# Full.net
KiCad netlist of a schematic drawn in EAGLE
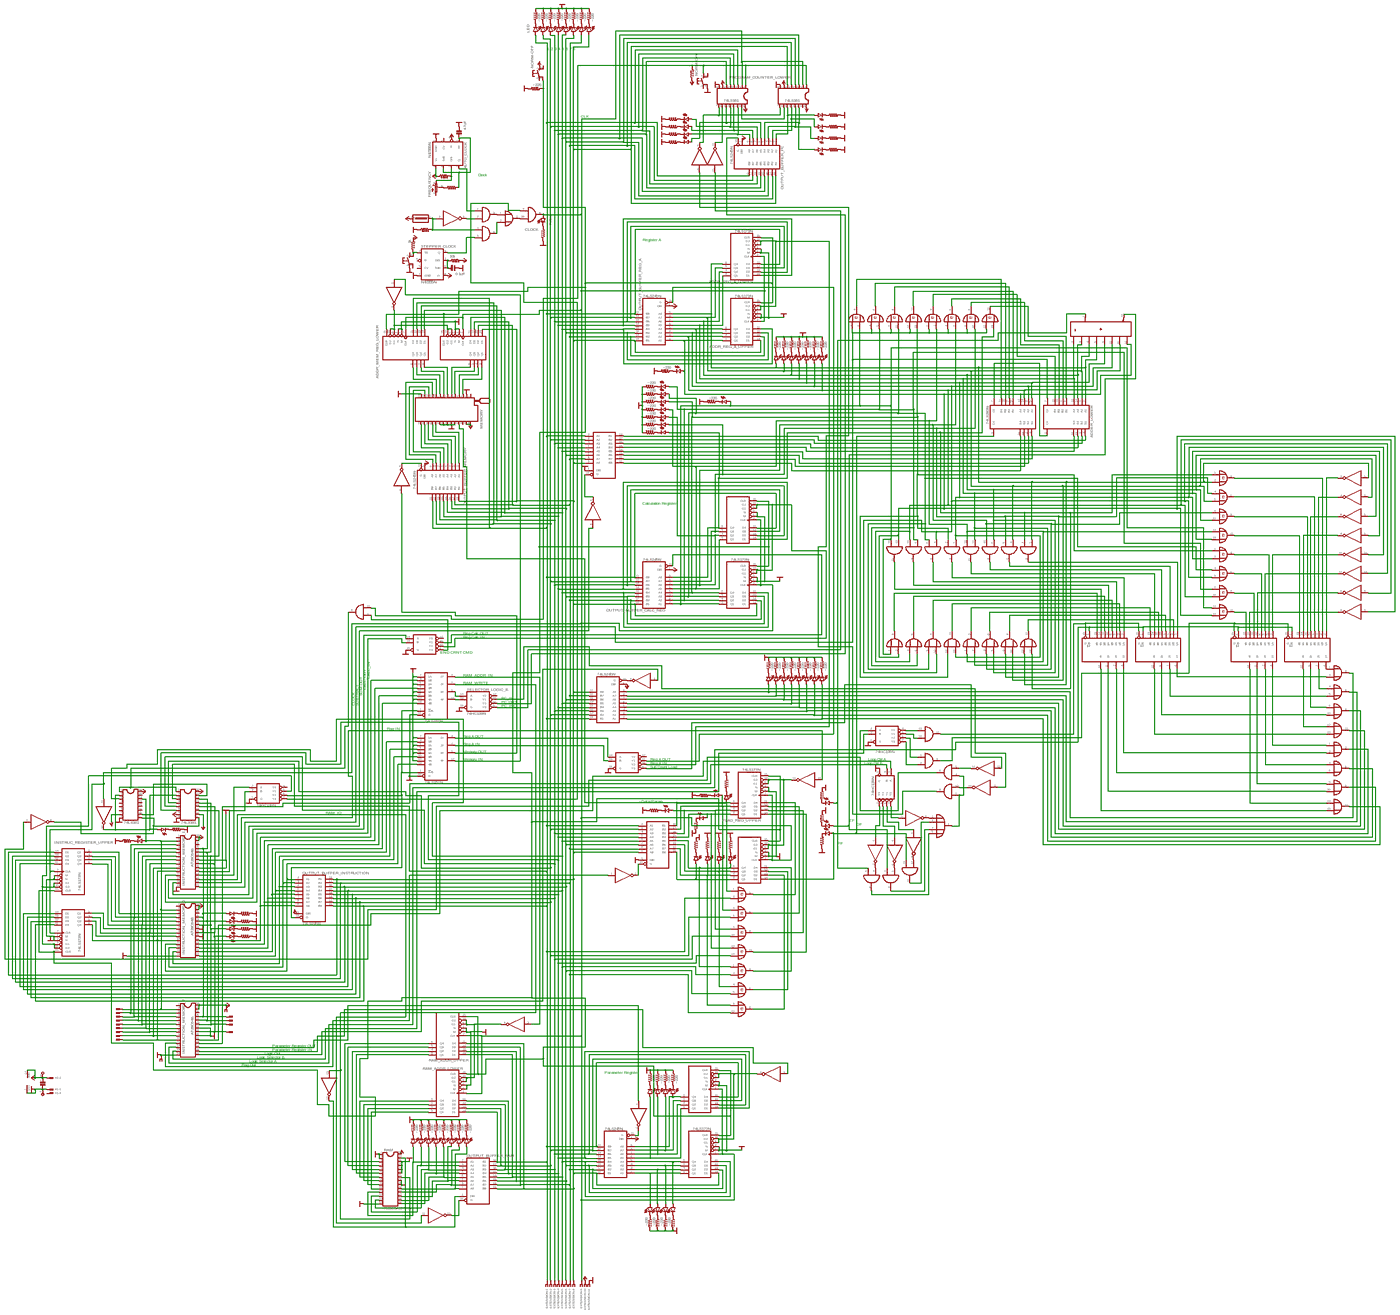
[diagram p0: schematic, sheet 1, overview]
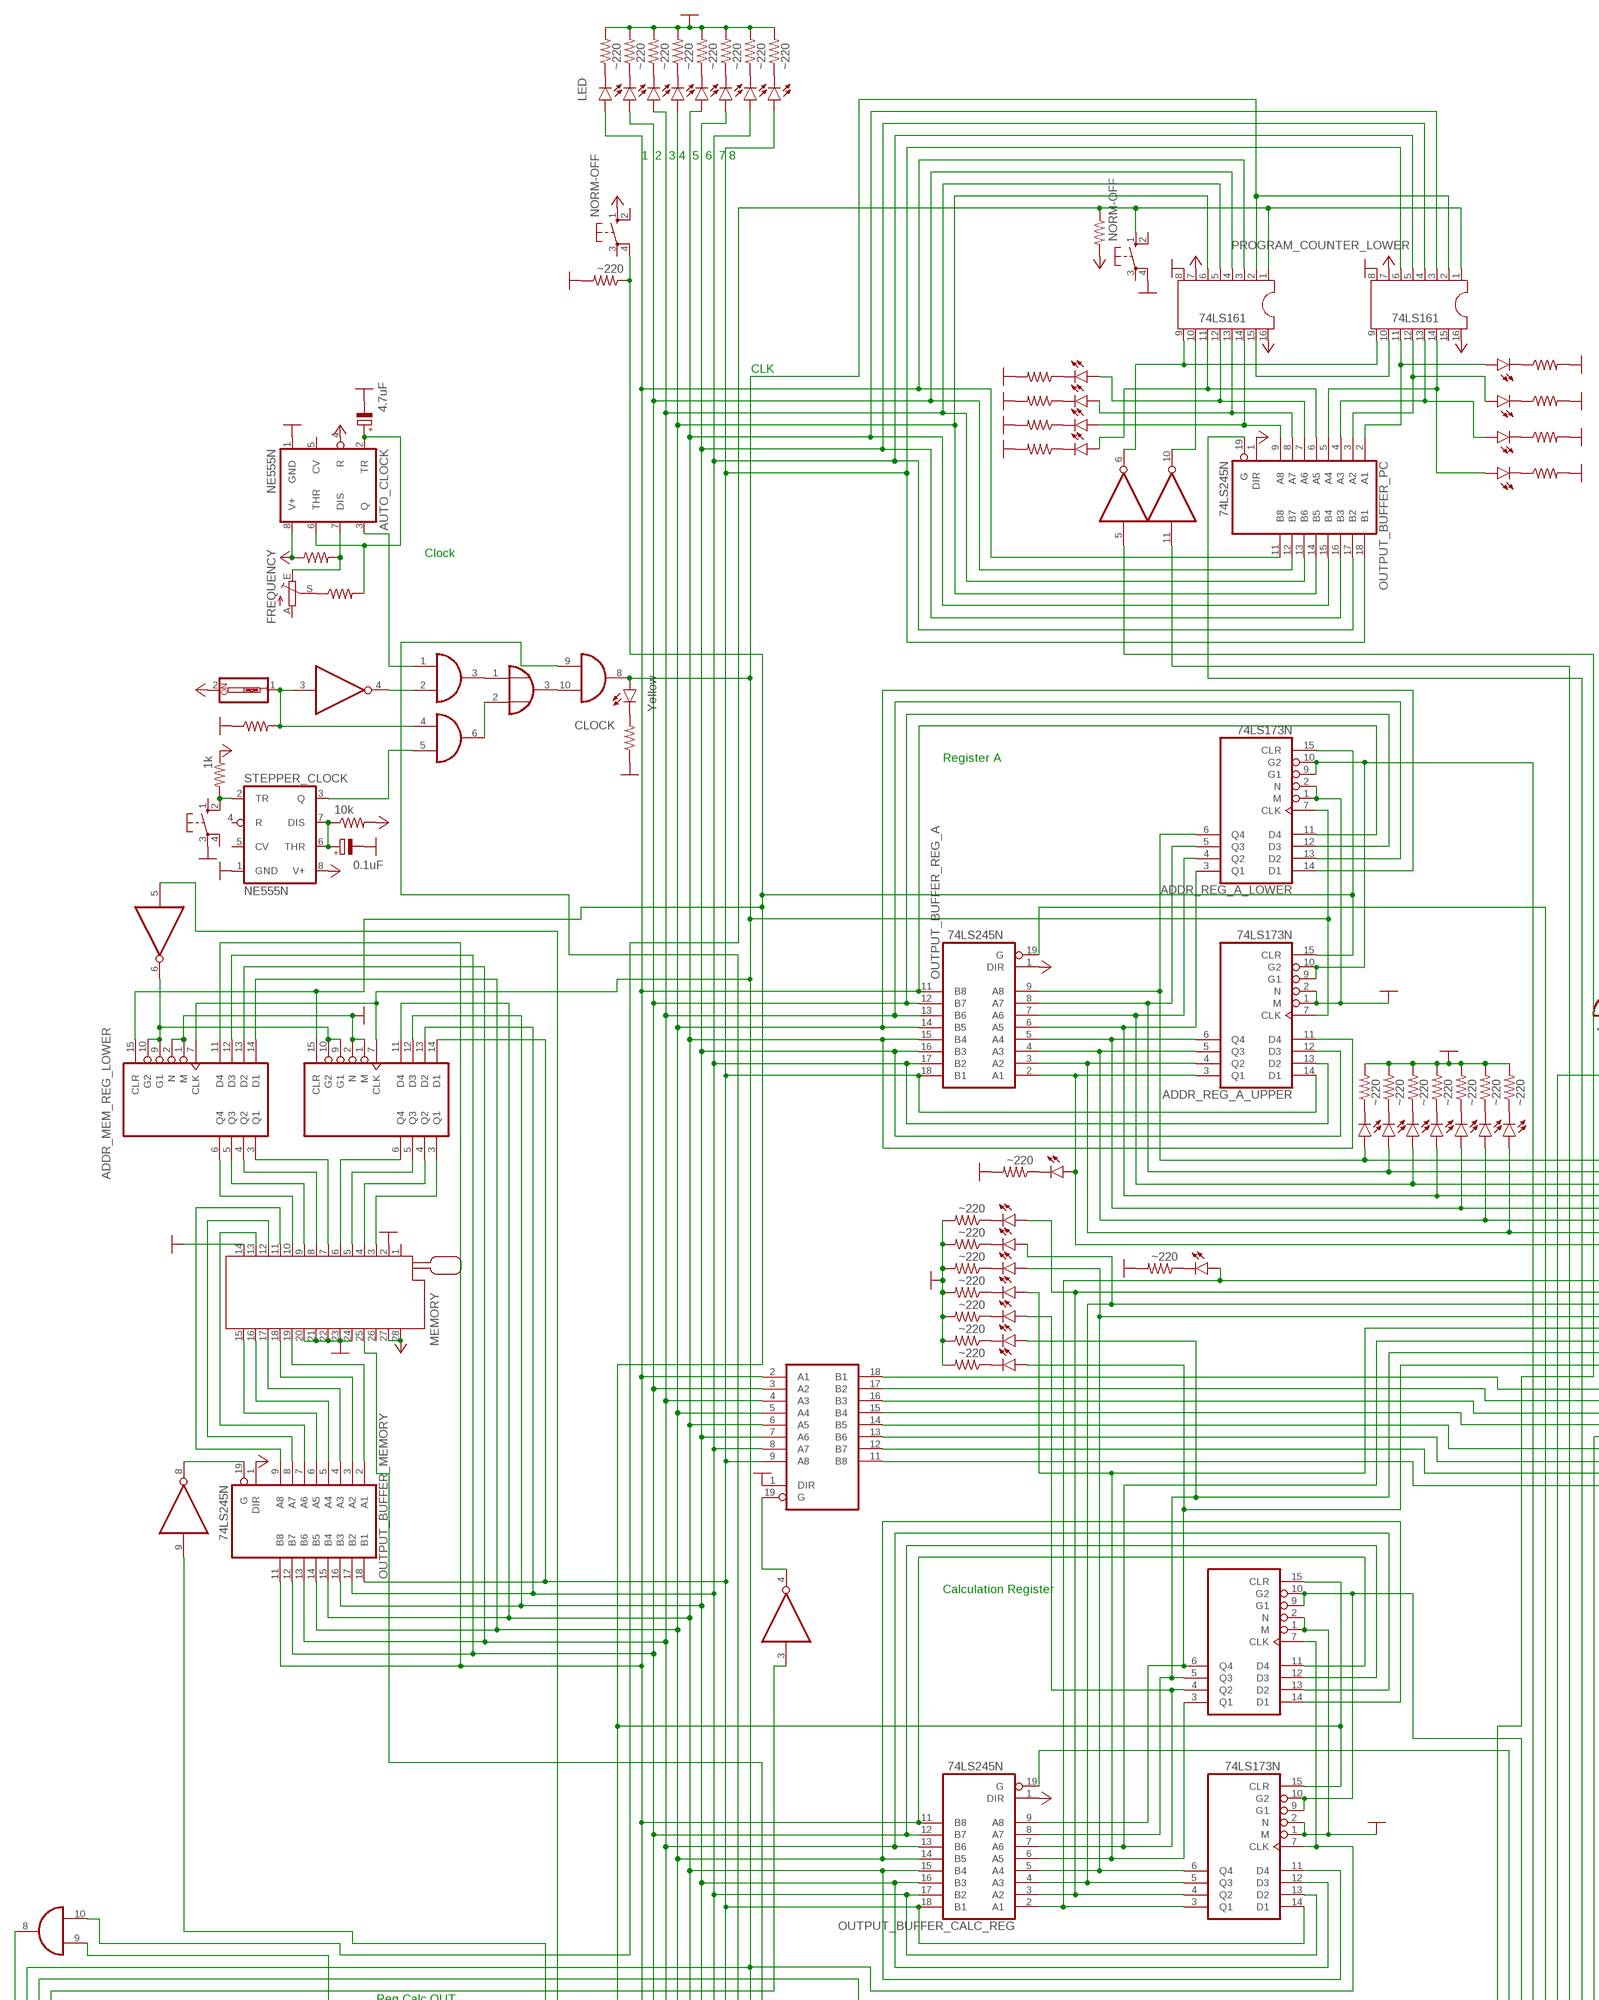
[diagram p1: schematic, sheet 1, part 1 of 4]
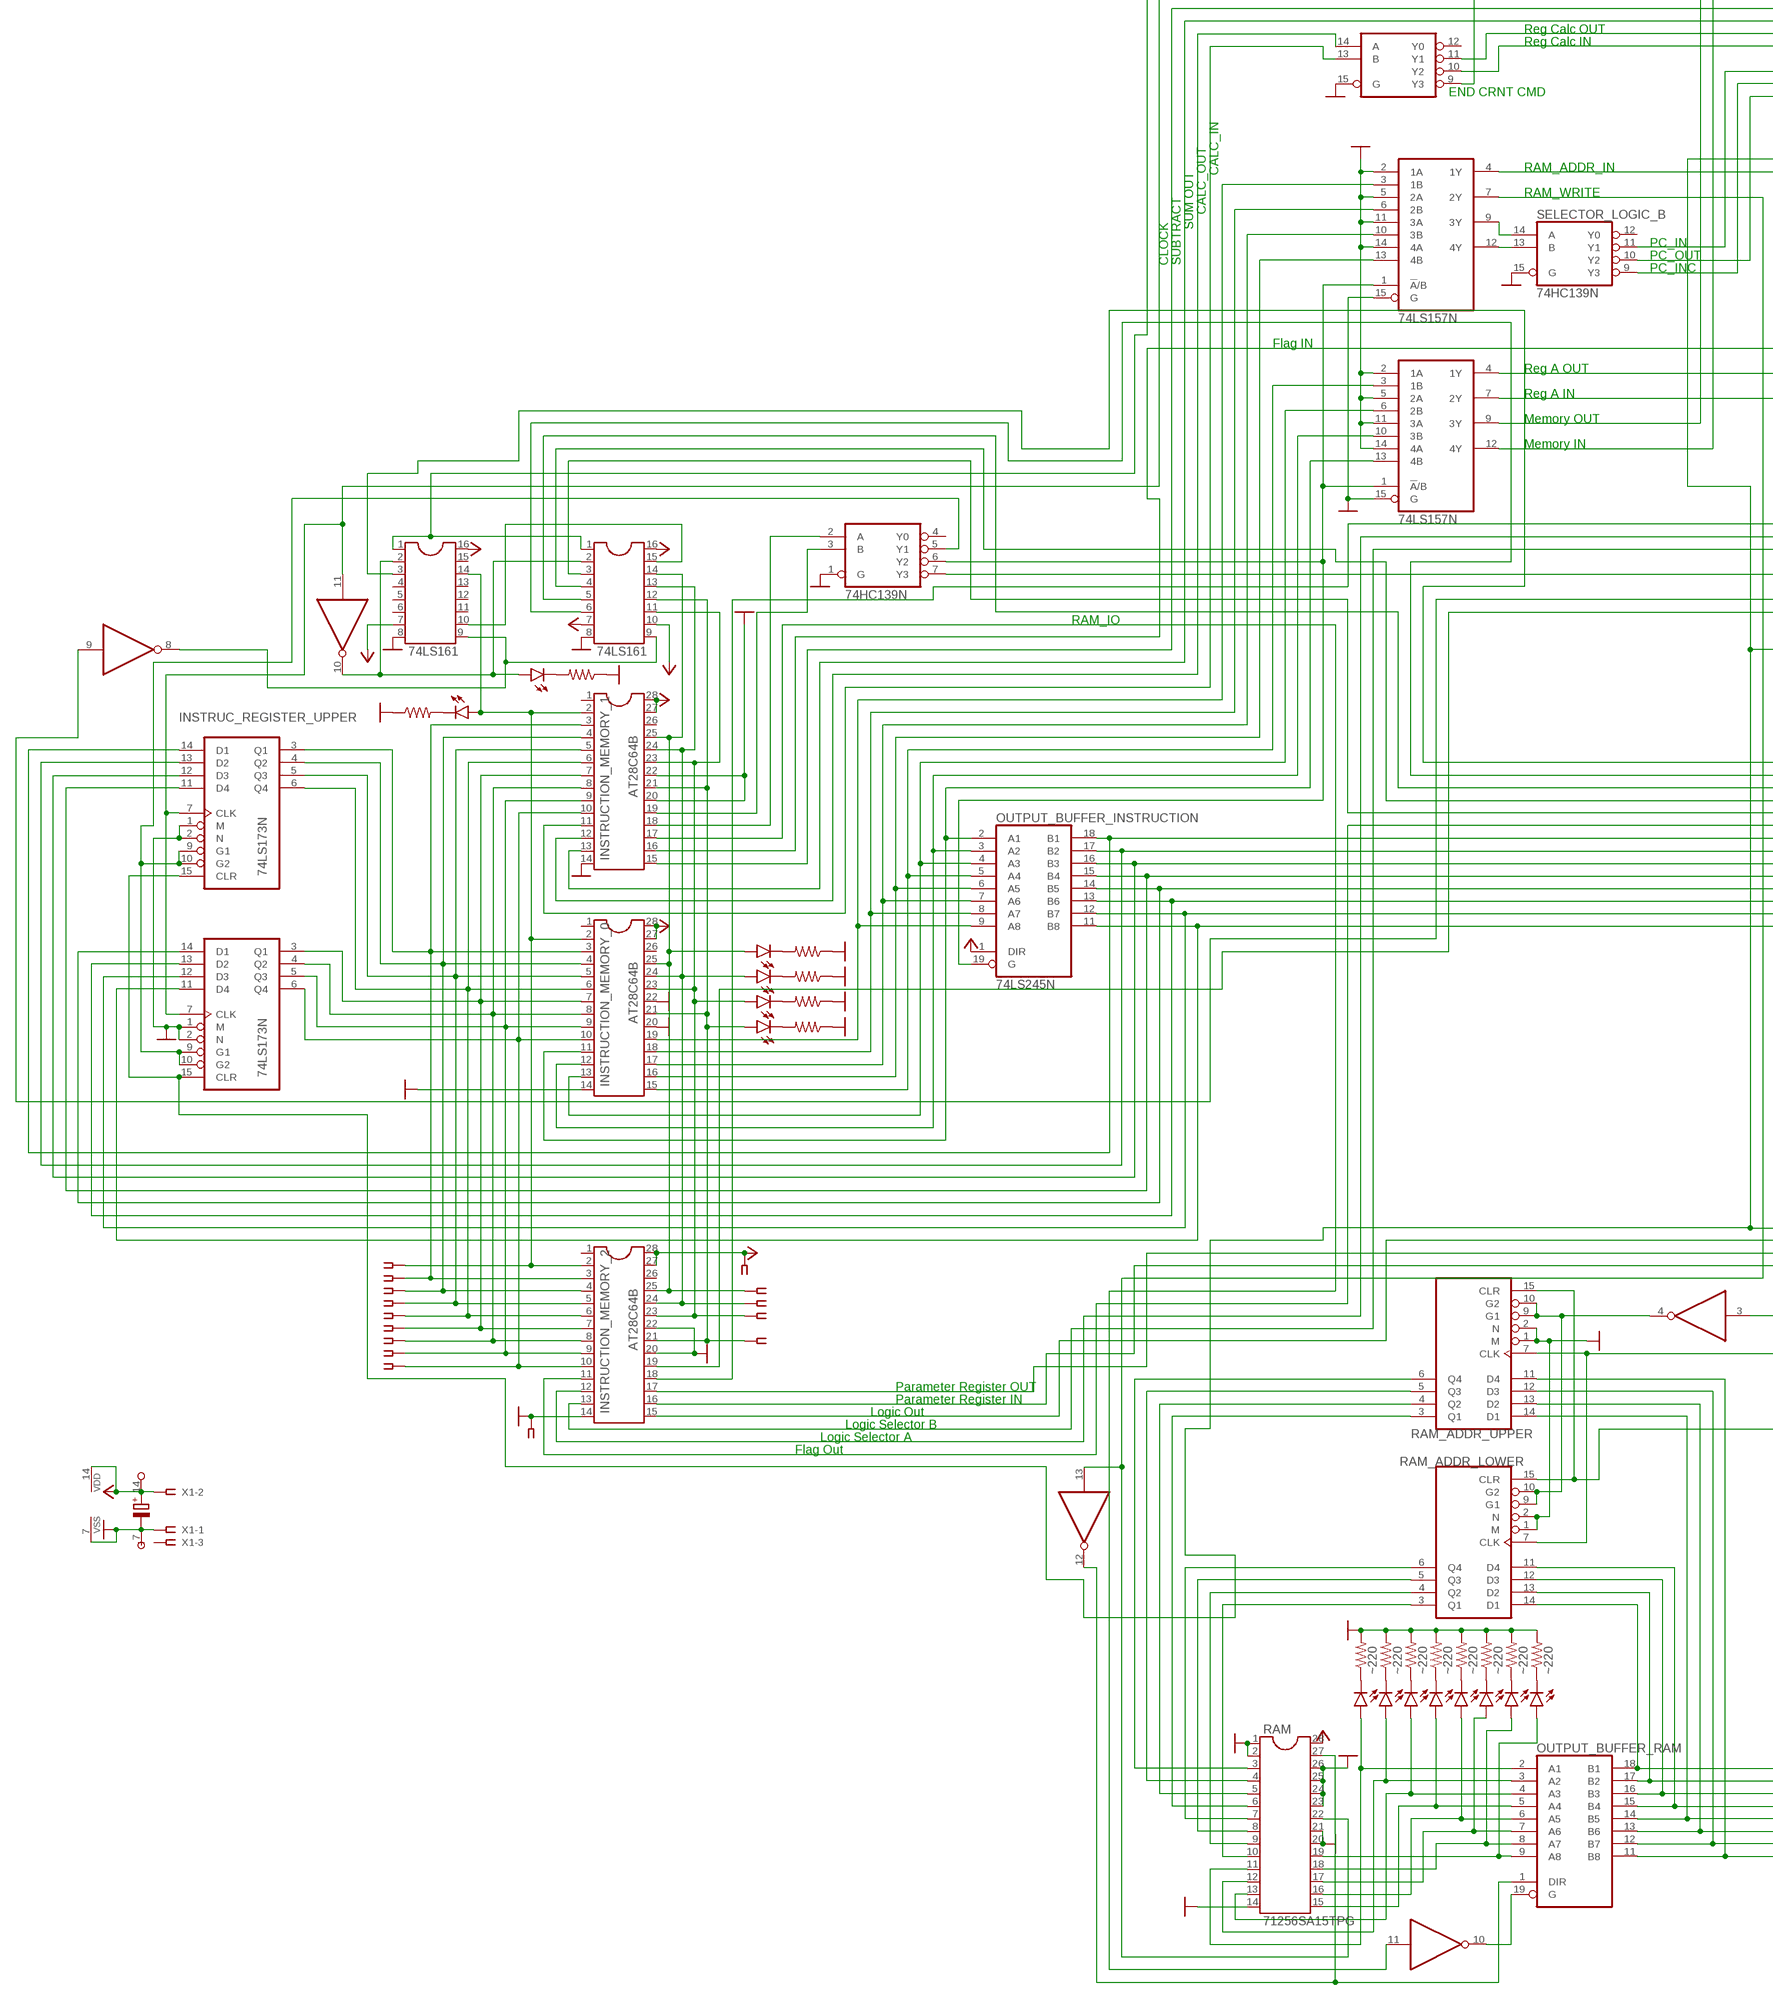
[diagram p2: schematic, sheet 1, part 2 of 4]
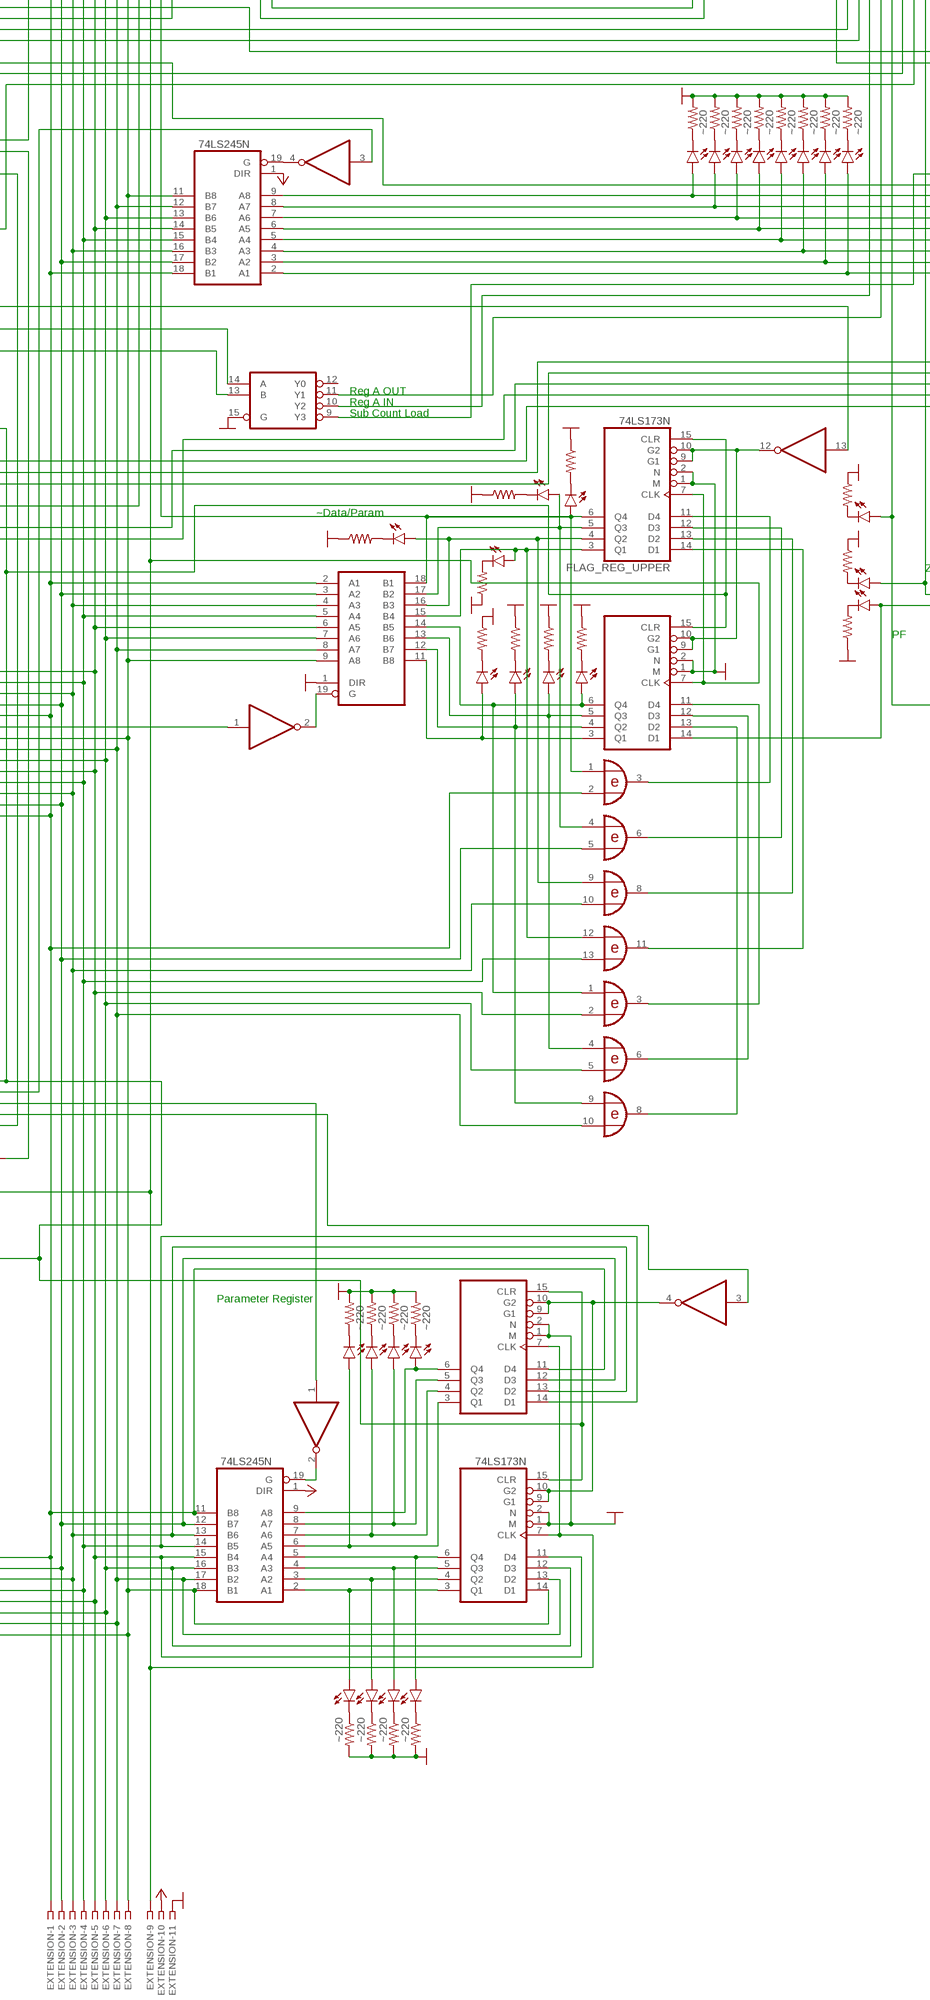
[diagram p3: schematic, sheet 1, part 3 of 4]
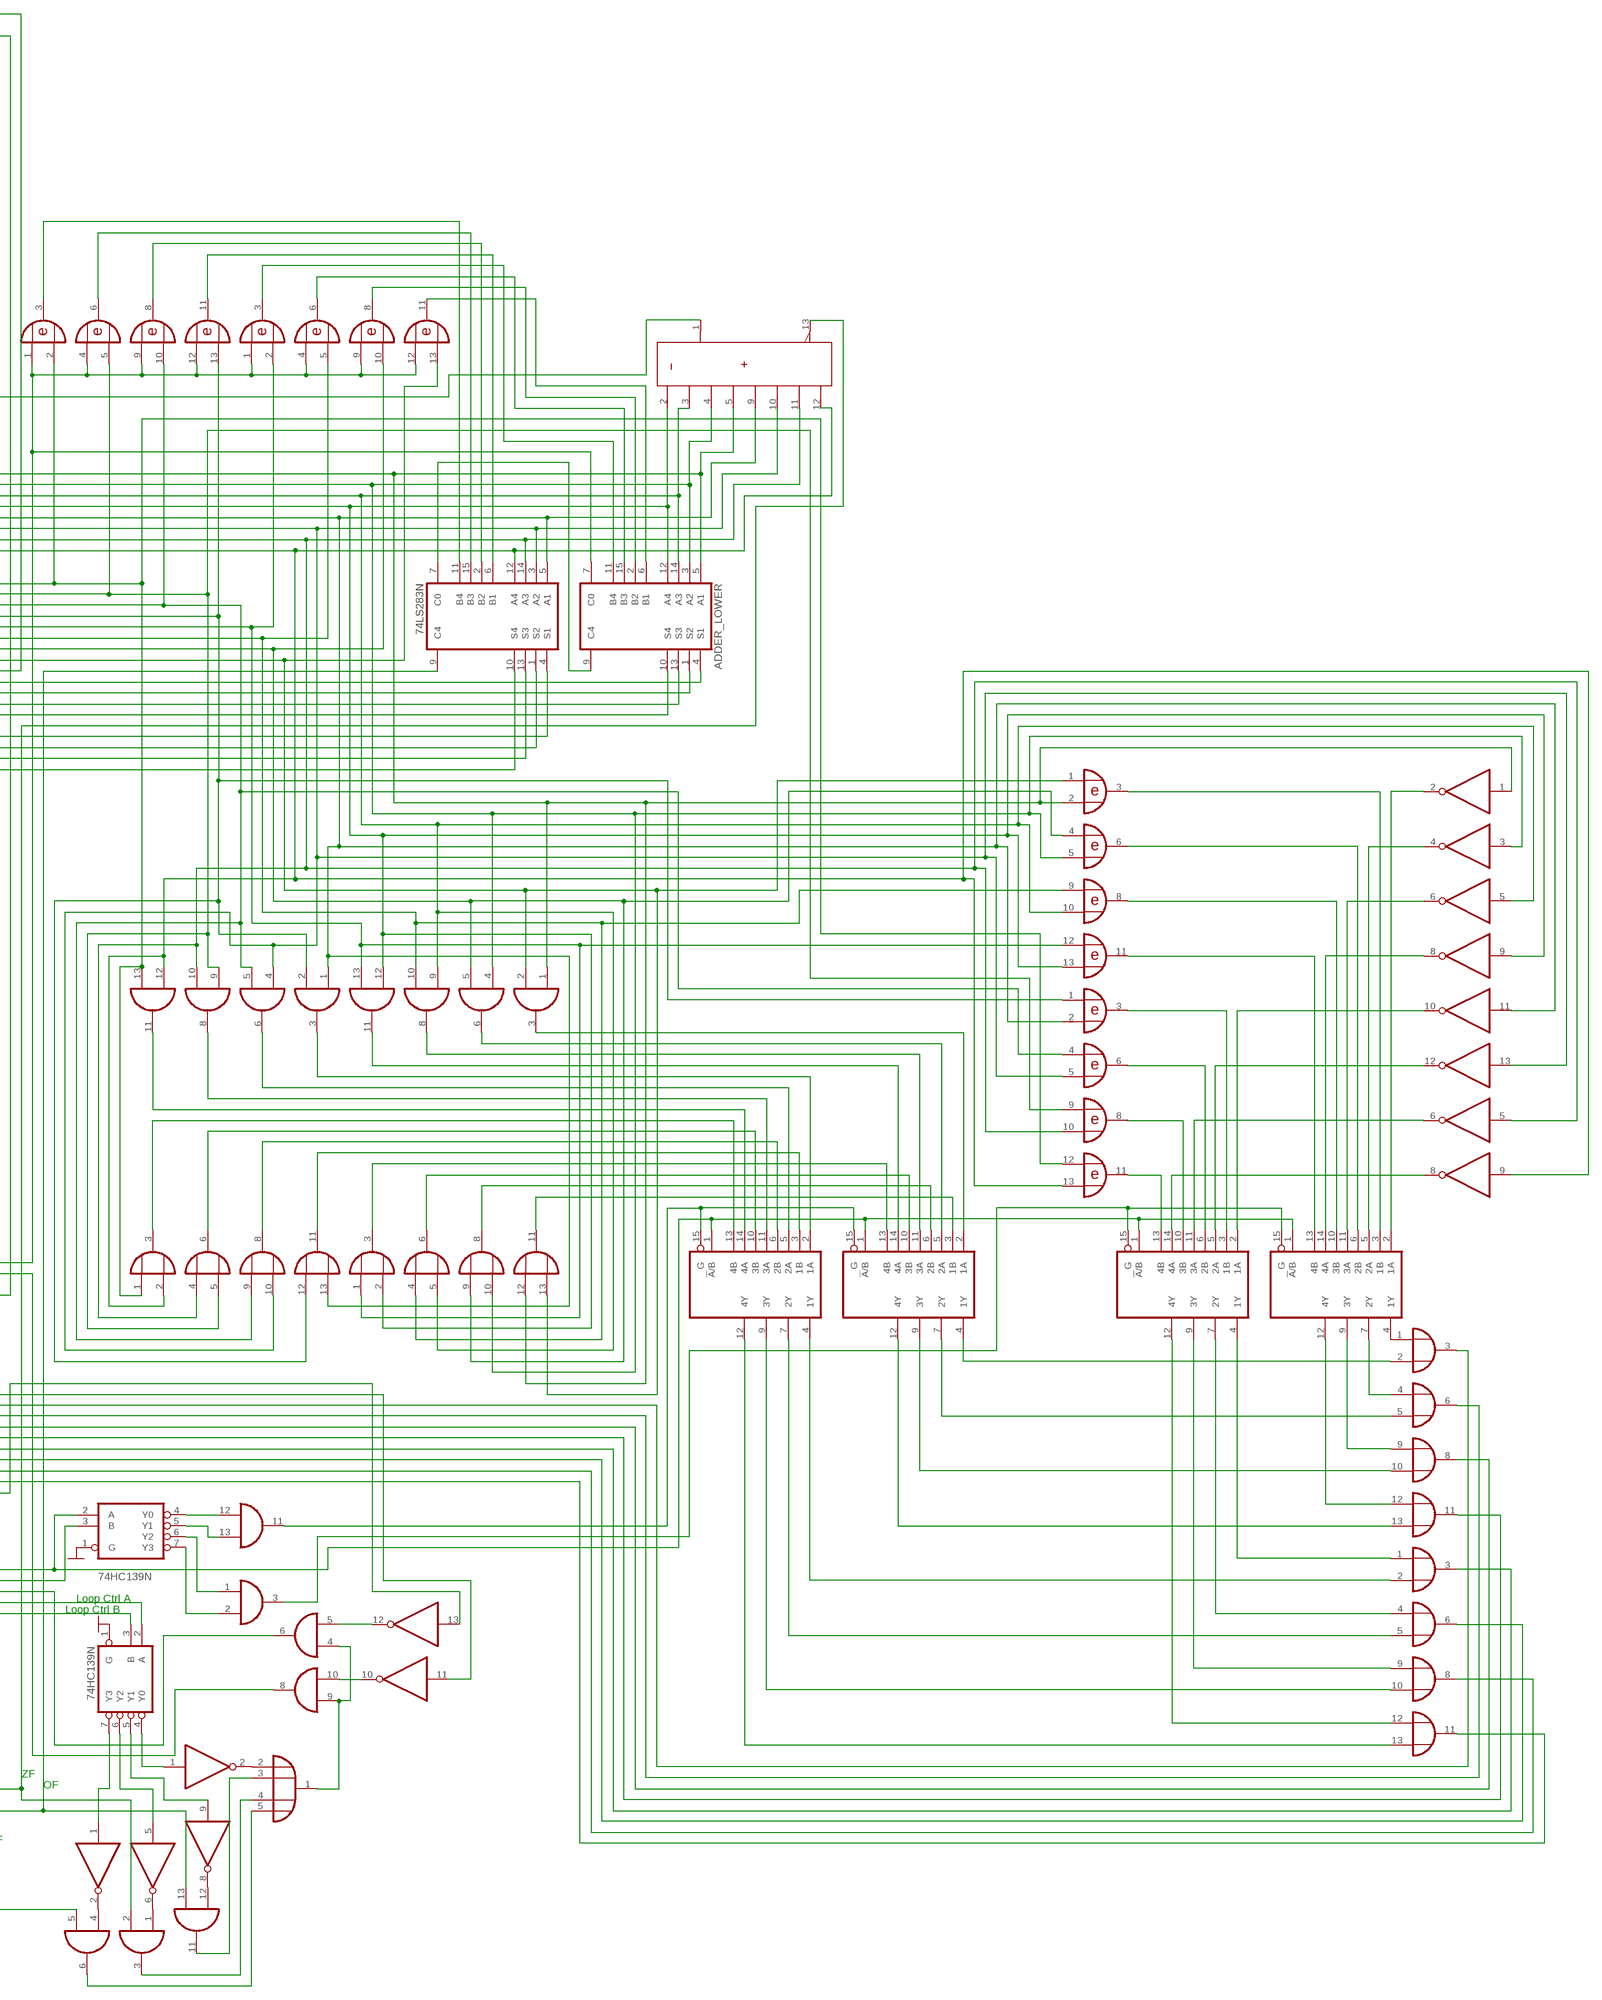
[diagram p4: schematic, sheet 1, part 4 of 4]

(export (version "E")
  (design (tool "Eeschema 10.0.6"))
  (components
    (comp (ref "4_INP_OR_GATE")
      (value "4072N")
      (footprint "eagle-import:DIL14")
      (libsource (lib "eagle-import") (part "4072N"))
    )
    (comp (ref "ADDER_LOWER")
      (value "74LS283N")
      (footprint "eagle-import:DIL16")
      (libsource (lib "eagle-import") (part "74283NLS"))
    )
    (comp (ref "ADDER_UPPER")
      (value "74LS283N")
      (footprint "eagle-import:DIL16")
      (libsource (lib "eagle-import") (part "74283NLS"))
    )
    (comp (ref "ADDR_MEM_REG_LOWER")
      (value "74LS173N")
      (footprint "eagle-import:DIL16")
      (libsource (lib "eagle-import") (part "74173NLS"))
    )
    (comp (ref "ADDR_MEM_REG_UPPER")
      (value "74LS173N")
      (footprint "eagle-import:DIL16")
      (libsource (lib "eagle-import") (part "74173NLS"))
    )
    (comp (ref "ADDR_REG_A_LOWER")
      (value "74LS173N")
      (footprint "eagle-import:DIL16")
      (libsource (lib "eagle-import") (part "74173NLS"))
    )
    (comp (ref "ADDR_REG_A_UPPER")
      (value "74LS173N")
      (footprint "eagle-import:DIL16")
      (libsource (lib "eagle-import") (part "74173NLS"))
    )
    (comp (ref "ADDR_REG_CALC_LOWER")
      (value "74LS173N")
      (footprint "eagle-import:DIL16")
      (libsource (lib "eagle-import") (part "74173NLS"))
    )
    (comp (ref "ADDR_REG_CALC_UPPER")
      (value "74LS173N")
      (footprint "eagle-import:DIL16")
      (libsource (lib "eagle-import") (part "74173NLS"))
    )
    (comp (ref "ADDR_REG_PARAM_LOWER")
      (value "74LS173N")
      (footprint "eagle-import:DIL16")
      (libsource (lib "eagle-import") (part "74173NLS"))
    )
    (comp (ref "ADDR_REG_PARAM_UPPER")
      (value "74LS173N")
      (footprint "eagle-import:DIL16")
      (libsource (lib "eagle-import") (part "74173NLS"))
    )
    (comp (ref "AND_GATE1_")
      (value "74LS08N")
      (footprint "eagle-import:DIL14")
      (libsource (lib "eagle-import") (part "7408NLS"))
    )
    (comp (ref "AND_GATE2_")
      (value "74LS08N")
      (footprint "eagle-import:DIL14")
      (libsource (lib "eagle-import") (part "7408NLS"))
    )
    (comp (ref "AND_GATE3_")
      (value "74LS08N")
      (footprint "eagle-import:DIL14")
      (libsource (lib "eagle-import") (part "7408NLS"))
    )
    (comp (ref "AND_GATE4_")
      (value "74LS08N")
      (footprint "eagle-import:DIL14")
      (libsource (lib "eagle-import") (part "7408NLS"))
    )
    (comp (ref "AND_GATE_")
      (value "74LS08N")
      (footprint "eagle-import:DIL14")
      (libsource (lib "eagle-import") (part "7408NLS"))
    )
    (comp (ref "AUTO_CLOCK")
      (value "NE555N")
      (footprint "eagle-import:DIL08")
      (libsource (lib "eagle-import") (part "555NNE"))
    )
    (comp (ref "BRANCH_SELECTOR")
      (value "74HC139N")
      (footprint "eagle-import:DIL16")
      (libsource (lib "eagle-import") (part "74139NHC"))
    )
    (comp (ref "C1")
      (value "4.7uF")
      (footprint "eagle-import:E2-5")
      (libsource (lib "eagle-import") (part "CPOL-EUE2-5"))
    )
    (comp (ref "C2")
      (value "0.1uF")
      (footprint "eagle-import:E2-5")
      (libsource (lib "eagle-import") (part "CPOL-EUE2-5"))
    )
    (comp (ref "C3")
      (value "0.1uF")
      (footprint "eagle-import:E2-5")
      (libsource (lib "eagle-import") (part "CPOL-EUE2-5"))
    )
    (comp (ref "CLK_MODE")
      (value "SW_DIP-1")
      (footprint "eagle-import:EDG-01")
      (libsource (lib "eagle-import") (part "SW_DIP-1"))
    )
    (comp (ref "CLK_TRIGGER")
      (value "10-XX")
      (footprint "eagle-import:B3F-10XX")
      (fields (field (name "MPN") "B3F-1000"))
      (libsource (lib "eagle-import") (part "10-XX"))
    )
    (comp (ref "CLOCK")
      (value "Yellow")
      (footprint "eagle-import:LED5MM")
      (libsource (lib "eagle-import") (part "LED5MM"))
    )
    (comp (ref "DATABUS_1")
      (value "LED")
      (footprint "eagle-import:LED5MM")
      (libsource (lib "eagle-import") (part "LED5MM"))
    )
    (comp (ref "DATABUS_2")
      (value "LED5MM")
      (footprint "eagle-import:LED5MM")
      (libsource (lib "eagle-import") (part "LED5MM"))
    )
    (comp (ref "DATABUS_3")
      (value "LED5MM")
      (footprint "eagle-import:LED5MM")
      (libsource (lib "eagle-import") (part "LED5MM"))
    )
    (comp (ref "DATABUS_4")
      (value "LED5MM")
      (footprint "eagle-import:LED5MM")
      (libsource (lib "eagle-import") (part "LED5MM"))
    )
    (comp (ref "DATABUS_5")
      (value "LED5MM")
      (footprint "eagle-import:LED5MM")
      (libsource (lib "eagle-import") (part "LED5MM"))
    )
    (comp (ref "DATABUS_6")
      (value "LED5MM")
      (footprint "eagle-import:LED5MM")
      (libsource (lib "eagle-import") (part "LED5MM"))
    )
    (comp (ref "DATABUS_7")
      (value "LED5MM")
      (footprint "eagle-import:LED5MM")
      (libsource (lib "eagle-import") (part "LED5MM"))
    )
    (comp (ref "DATABUS_8")
      (value "LED5MM")
      (footprint "eagle-import:LED5MM")
      (libsource (lib "eagle-import") (part "LED5MM"))
    )
    (comp (ref "EXTENSION")
      (value "SSW-111-02-G-S")
      (footprint "eagle-import:SSW-111-02-G-S")
      (fields (field (name "MF") "Samtec Inc."))
      (libsource (lib "eagle-import") (part "SSW-111-02-G-S"))
    )
    (comp (ref "FLAG_1")
      (value "LED5MM")
      (footprint "eagle-import:LED5MM")
      (libsource (lib "eagle-import") (part "LED5MM"))
    )
    (comp (ref "FLAG_2")
      (value "LED5MM")
      (footprint "eagle-import:LED5MM")
      (libsource (lib "eagle-import") (part "LED5MM"))
    )
    (comp (ref "FLAG_3")
      (value "LED5MM")
      (footprint "eagle-import:LED5MM")
      (libsource (lib "eagle-import") (part "LED5MM"))
    )
    (comp (ref "FLAG_4")
      (value "LED5MM")
      (footprint "eagle-import:LED5MM")
      (libsource (lib "eagle-import") (part "LED5MM"))
    )
    (comp (ref "FLAG_5")
      (value "LED5MM")
      (footprint "eagle-import:LED5MM")
      (libsource (lib "eagle-import") (part "LED5MM"))
    )
    (comp (ref "FLAG_6")
      (value "LED5MM")
      (footprint "eagle-import:LED5MM")
      (libsource (lib "eagle-import") (part "LED5MM"))
    )
    (comp (ref "FLAG_7")
      (value "LED5MM")
      (footprint "eagle-import:LED5MM")
      (libsource (lib "eagle-import") (part "LED5MM"))
    )
    (comp (ref "FLAG_8")
      (value "LED5MM")
      (footprint "eagle-import:LED5MM")
      (libsource (lib "eagle-import") (part "LED5MM"))
    )
    (comp (ref "FLAG_REG_LOWER")
      (value "74LS173N")
      (footprint "eagle-import:DIL16")
      (libsource (lib "eagle-import") (part "74173NLS"))
    )
    (comp (ref "FLAG_REG_UPPER")
      (value "74LS173N")
      (footprint "eagle-import:DIL16")
      (libsource (lib "eagle-import") (part "74173NLS"))
    )
    (comp (ref "FREQUENCY")
      (value "100k")
      (footprint "eagle-import:RJ9W")
      (libsource (lib "eagle-import") (part "TRIM_EU-RJ9W"))
    )
    (comp (ref "INSRUCTION_REGISTER_SELECTOR_LOWER")
      (value "74LS157N")
      (footprint "eagle-import:DIL16")
      (libsource (lib "eagle-import") (part "74157NLS"))
    )
    (comp (ref "INSRUCTION_REGISTER_SELECTOR_UPPER")
      (value "74LS157N")
      (footprint "eagle-import:DIL16")
      (libsource (lib "eagle-import") (part "74157NLS"))
    )
    (comp (ref "INSTRUCTIONS_EXTENSION")
      (value "SSW-115-02-G-S")
      (footprint "eagle-import:SSW-115-02-G-S")
      (fields (field (name "MF") "Samtec Inc."))
      (libsource (lib "eagle-import") (part "SSW-115-02-G-S"))
    )
    (comp (ref "INSTRUCTION_MEMORY_0")
      (value "AT28C64B")
      (footprint "eagle-import:DIL28-6")
      (libsource (lib "eagle-import") (part "DIL28"))
    )
    (comp (ref "INSTRUCTION_MEMORY_1")
      (value "AT28C64B")
      (footprint "eagle-import:DIL28-6")
      (libsource (lib "eagle-import") (part "DIL28"))
    )
    (comp (ref "INSTRUCTION_MEMORY_2")
      (value "AT28C64B")
      (footprint "eagle-import:DIL28-6")
      (libsource (lib "eagle-import") (part "DIL28"))
    )
    (comp (ref "INSTRUC_REGISTER_LOWER")
      (value "74LS173N")
      (footprint "eagle-import:DIL16")
      (libsource (lib "eagle-import") (part "74173NLS"))
    )
    (comp (ref "INSTRUC_REGISTER_UPPER")
      (value "74LS173N")
      (footprint "eagle-import:DIL16")
      (libsource (lib "eagle-import") (part "74173NLS"))
    )
    (comp (ref "INVERTED_CLK_LED")
      (value "White")
      (footprint "eagle-import:LED5MM")
      (libsource (lib "eagle-import") (part "LED5MM"))
    )
    (comp (ref "LED_A_REG_1")
      (value "LED5MM")
      (footprint "eagle-import:LED5MM")
      (libsource (lib "eagle-import") (part "LED5MM"))
    )
    (comp (ref "LED_A_REG_2")
      (value "LED5MM")
      (footprint "eagle-import:LED5MM")
      (libsource (lib "eagle-import") (part "LED5MM"))
    )
    (comp (ref "LED_A_REG_3")
      (value "LED5MM")
      (footprint "eagle-import:LED5MM")
      (libsource (lib "eagle-import") (part "LED5MM"))
    )
    (comp (ref "LED_A_REG_4")
      (value "LED5MM")
      (footprint "eagle-import:LED5MM")
      (libsource (lib "eagle-import") (part "LED5MM"))
    )
    (comp (ref "LED_A_REG_5")
      (value "LED5MM")
      (footprint "eagle-import:LED5MM")
      (libsource (lib "eagle-import") (part "LED5MM"))
    )
    (comp (ref "LED_A_REG_6")
      (value "LED5MM")
      (footprint "eagle-import:LED5MM")
      (libsource (lib "eagle-import") (part "LED5MM"))
    )
    (comp (ref "LED_A_REG_7")
      (value "LED5MM")
      (footprint "eagle-import:LED5MM")
      (libsource (lib "eagle-import") (part "LED5MM"))
    )
    (comp (ref "LED_A_REG_8")
      (value "LED5MM")
      (footprint "eagle-import:LED5MM")
      (libsource (lib "eagle-import") (part "LED5MM"))
    )
    (comp (ref "LED_B_REG_1")
      (value "LED5MM")
      (footprint "eagle-import:LED5MM")
      (libsource (lib "eagle-import") (part "LED5MM"))
    )
    (comp (ref "LED_B_REG_2")
      (value "LED5MM")
      (footprint "eagle-import:LED5MM")
      (libsource (lib "eagle-import") (part "LED5MM"))
    )
    (comp (ref "LED_B_REG_3")
      (value "LED5MM")
      (footprint "eagle-import:LED5MM")
      (libsource (lib "eagle-import") (part "LED5MM"))
    )
    (comp (ref "LED_B_REG_4")
      (value "LED5MM")
      (footprint "eagle-import:LED5MM")
      (libsource (lib "eagle-import") (part "LED5MM"))
    )
    (comp (ref "LED_B_REG_5")
      (value "LED5MM")
      (footprint "eagle-import:LED5MM")
      (libsource (lib "eagle-import") (part "LED5MM"))
    )
    (comp (ref "LED_B_REG_6")
      (value "LED5MM")
      (footprint "eagle-import:LED5MM")
      (libsource (lib "eagle-import") (part "LED5MM"))
    )
    (comp (ref "LED_B_REG_7")
      (value "LED5MM")
      (footprint "eagle-import:LED5MM")
      (libsource (lib "eagle-import") (part "LED5MM"))
    )
    (comp (ref "LED_B_REG_8")
      (value "LED5MM")
      (footprint "eagle-import:LED5MM")
      (libsource (lib "eagle-import") (part "LED5MM"))
    )
    (comp (ref "LOGIC_LED_1")
      (value "LED3MM")
      (footprint "eagle-import:LED3MM")
      (libsource (lib "eagle-import") (part "LED3MM"))
    )
    (comp (ref "LOGIC_LED_2")
      (value "LED3MM")
      (footprint "eagle-import:LED3MM")
      (libsource (lib "eagle-import") (part "LED3MM"))
    )
    (comp (ref "LOGIC_LED_3")
      (value "LED3MM")
      (footprint "eagle-import:LED3MM")
      (libsource (lib "eagle-import") (part "LED3MM"))
    )
    (comp (ref "LOGIC_LED_4")
      (value "LED3MM")
      (footprint "eagle-import:LED3MM")
      (libsource (lib "eagle-import") (part "LED3MM"))
    )
    (comp (ref "LOGIC_LED_5")
      (value "LED3MM")
      (footprint "eagle-import:LED3MM")
      (libsource (lib "eagle-import") (part "LED3MM"))
    )
    (comp (ref "LOGIC_LED_6")
      (value "LED3MM")
      (footprint "eagle-import:LED3MM")
      (libsource (lib "eagle-import") (part "LED3MM"))
    )
    (comp (ref "LOGIC_LED_7")
      (value "LED3MM")
      (footprint "eagle-import:LED3MM")
      (libsource (lib "eagle-import") (part "LED3MM"))
    )
    (comp (ref "LOGIC_LED_8")
      (value "LED3MM")
      (footprint "eagle-import:LED3MM")
      (libsource (lib "eagle-import") (part "LED3MM"))
    )
    (comp (ref "LOGIC_SELECTOR-AND/OR_LOWER")
      (value "74LS157N")
      (footprint "eagle-import:DIL16")
      (libsource (lib "eagle-import") (part "74157NLS"))
    )
    (comp (ref "LOGIC_SELECTOR-AND/OR_UPPER")
      (value "74LS157N")
      (footprint "eagle-import:DIL16")
      (libsource (lib "eagle-import") (part "74157NLS"))
    )
    (comp (ref "LOGIC_SELECTOR-XOR/NOT_LOWER")
      (value "74LS157N")
      (footprint "eagle-import:DIL16")
      (libsource (lib "eagle-import") (part "74157NLS"))
    )
    (comp (ref "LOGIC_SELECTOR-XOR/NOT_UPPER")
      (value "74LS157N")
      (footprint "eagle-import:DIL16")
      (libsource (lib "eagle-import") (part "74157NLS"))
    )
    (comp (ref "MEMORY")
      (value "228-1277-00-0602J")
      (footprint "eagle-import:228-1277-00-0602J")
      (fields (field (name "MF") "3M"))
      (libsource (lib "eagle-import") (part "228-?00-0602J1277-"))
    )
    (comp (ref "MICRO_COUNTER_LOWER")
      (value "74LS161")
      (footprint "eagle-import:DIL16")
      (libsource (lib "eagle-import") (part "DIL16"))
    )
    (comp (ref "MICRO_COUNTER_UPPER")
      (value "74LS161")
      (footprint "eagle-import:DIL16")
      (libsource (lib "eagle-import") (part "DIL16"))
    )
    (comp (ref "NOT_GATE1")
      (value "74LS04N")
      (footprint "eagle-import:DIL14")
      (libsource (lib "eagle-import") (part "7404NLS"))
    )
    (comp (ref "NOT_GATE2_")
      (value "74LS04N")
      (footprint "eagle-import:DIL14")
      (libsource (lib "eagle-import") (part "7404NLS"))
    )
    (comp (ref "NOT_GATE3_")
      (value "74LS04N")
      (footprint "eagle-import:DIL14")
      (libsource (lib "eagle-import") (part "7404NLS"))
    )
    (comp (ref "NOT_GATE4_")
      (value "74LS04N")
      (footprint "eagle-import:DIL14")
      (fields (field (name "SPICEPREFIX") "B"))
      (libsource (lib "eagle-import") (part "7404NLS"))
    )
    (comp (ref "NOT_GATE5_")
      (value "74LS04N")
      (footprint "eagle-import:DIL14")
      (libsource (lib "eagle-import") (part "7404NLS"))
    )
    (comp (ref "NOT_GATE_")
      (value "74LS04N")
      (footprint "eagle-import:DIL14")
      (libsource (lib "eagle-import") (part "7404NLS"))
    )
    (comp (ref "OR_GATE1_")
      (value "74LS32N")
      (footprint "eagle-import:DIL14")
      (libsource (lib "eagle-import") (part "7432NLS"))
    )
    (comp (ref "OR_GATE2_")
      (value "74LS32N")
      (footprint "eagle-import:DIL14")
      (libsource (lib "eagle-import") (part "7432NLS"))
    )
    (comp (ref "OR_GATE3_")
      (value "74LS32N")
      (footprint "eagle-import:DIL14")
      (libsource (lib "eagle-import") (part "7432NLS"))
    )
    (comp (ref "OR_GATE4_")
      (value "74LS32N")
      (footprint "eagle-import:DIL14")
      (libsource (lib "eagle-import") (part "7432NLS"))
    )
    (comp (ref "OR_GATE_")
      (value "74LS32N")
      (footprint "eagle-import:DIL14")
      (libsource (lib "eagle-import") (part "7432NLS"))
    )
    (comp (ref "OUTPUT_BUFFER_ALU")
      (value "74LS245N")
      (footprint "eagle-import:DIL20")
      (libsource (lib "eagle-import") (part "74245NLS"))
    )
    (comp (ref "OUTPUT_BUFFER_CALC_REG")
      (value "74LS245N")
      (footprint "eagle-import:DIL20")
      (libsource (lib "eagle-import") (part "74245NLS"))
    )
    (comp (ref "OUTPUT_BUFFER_FLAGS")
      (value "74HC245N")
      (footprint "eagle-import:DIL20")
      (libsource (lib "eagle-import") (part "74245NHC"))
    )
    (comp (ref "OUTPUT_BUFFER_INSTRUCTION")
      (value "74LS245N")
      (footprint "eagle-import:DIL20")
      (libsource (lib "eagle-import") (part "74xx-us_88_74245NLS"))
    )
    (comp (ref "OUTPUT_BUFFER_LOGIC")
      (value "74LS245N")
      (footprint "eagle-import:DIL20")
      (libsource (lib "eagle-import") (part "74245NLS"))
    )
    (comp (ref "OUTPUT_BUFFER_MEMORY")
      (value "74LS245N")
      (footprint "eagle-import:DIL20")
      (libsource (lib "eagle-import") (part "74245NLS"))
    )
    (comp (ref "OUTPUT_BUFFER_PARAM_REG")
      (value "74LS245N")
      (footprint "eagle-import:DIL20")
      (libsource (lib "eagle-import") (part "74245NLS"))
    )
    (comp (ref "OUTPUT_BUFFER_PC")
      (value "74LS245N")
      (footprint "eagle-import:DIL20")
      (libsource (lib "eagle-import") (part "74245NLS"))
    )
    (comp (ref "OUTPUT_BUFFER_RAM")
      (value "74HC245N")
      (footprint "eagle-import:DIL20")
      (libsource (lib "eagle-import") (part "74245NHC"))
    )
    (comp (ref "OUTPUT_BUFFER_REG_A")
      (value "74LS245N")
      (footprint "eagle-import:DIL20")
      (libsource (lib "eagle-import") (part "74245NLS"))
    )
    (comp (ref "OVERFLOW_FLAG")
      (value "LED5MM")
      (footprint "eagle-import:LED5MM")
      (libsource (lib "eagle-import") (part "LED5MM"))
    )
    (comp (ref "PARAM_LED_1")
      (value "LED3MM")
      (footprint "eagle-import:LED3MM")
      (libsource (lib "eagle-import") (part "LED3MM"))
    )
    (comp (ref "PARAM_LED_2")
      (value "LED3MM")
      (footprint "eagle-import:LED3MM")
      (libsource (lib "eagle-import") (part "LED3MM"))
    )
    (comp (ref "PARAM_LED_3")
      (value "LED3MM")
      (footprint "eagle-import:LED3MM")
      (libsource (lib "eagle-import") (part "LED3MM"))
    )
    (comp (ref "PARAM_LED_4")
      (value "LED3MM")
      (footprint "eagle-import:LED3MM")
      (libsource (lib "eagle-import") (part "LED3MM"))
    )
    (comp (ref "PARAM_LED_5")
      (value "LED3MM")
      (footprint "eagle-import:LED3MM")
      (libsource (lib "eagle-import") (part "LED3MM"))
    )
    (comp (ref "PARAM_LED_6")
      (value "LED3MM")
      (footprint "eagle-import:LED3MM")
      (libsource (lib "eagle-import") (part "LED3MM"))
    )
    (comp (ref "PARAM_LED_7")
      (value "LED3MM")
      (footprint "eagle-import:LED3MM")
      (libsource (lib "eagle-import") (part "LED3MM"))
    )
    (comp (ref "PARAM_LED_8")
      (value "LED3MM")
      (footprint "eagle-import:LED3MM")
      (libsource (lib "eagle-import") (part "LED3MM"))
    )
    (comp (ref "PC_1")
      (value "LED5MM")
      (footprint "eagle-import:LED5MM")
      (libsource (lib "eagle-import") (part "LED5MM"))
    )
    (comp (ref "PC_2")
      (value "LED5MM")
      (footprint "eagle-import:LED5MM")
      (libsource (lib "eagle-import") (part "LED5MM"))
    )
    (comp (ref "PC_3")
      (value "LED5MM")
      (footprint "eagle-import:LED5MM")
      (libsource (lib "eagle-import") (part "LED5MM"))
    )
    (comp (ref "PC_4")
      (value "LED5MM")
      (footprint "eagle-import:LED5MM")
      (libsource (lib "eagle-import") (part "LED5MM"))
    )
    (comp (ref "PC_5")
      (value "LED5MM")
      (footprint "eagle-import:LED5MM")
      (libsource (lib "eagle-import") (part "LED5MM"))
    )
    (comp (ref "PC_6")
      (value "LED5MM")
      (footprint "eagle-import:LED5MM")
      (libsource (lib "eagle-import") (part "LED5MM"))
    )
    (comp (ref "PC_7")
      (value "LED5MM")
      (footprint "eagle-import:LED5MM")
      (libsource (lib "eagle-import") (part "LED5MM"))
    )
    (comp (ref "PC_8")
      (value "LED5MM")
      (footprint "eagle-import:LED5MM")
      (libsource (lib "eagle-import") (part "LED5MM"))
    )
    (comp (ref "POSITIVE_FLAG")
      (value "LED5MM")
      (footprint "eagle-import:LED5MM")
      (libsource (lib "eagle-import") (part "LED5MM"))
    )
    (comp (ref "PROGRAM_COUNTER_LOWER")
      (value "74LS161")
      (footprint "eagle-import:DIL16")
      (libsource (lib "eagle-import") (part "DIL16"))
    )
    (comp (ref "PROGRAM_COUNTER_UPPER")
      (value "74LS161")
      (footprint "eagle-import:DIL16")
      (libsource (lib "eagle-import") (part "DIL16"))
    )
    (comp (ref "R1")
      (value "1k")
      (footprint "eagle-import:0204_7")
      (libsource (lib "eagle-import") (part "R-US_0204/7"))
    )
    (comp (ref "R2")
      (value "1k")
      (footprint "eagle-import:0204_7")
      (libsource (lib "eagle-import") (part "R-US_0204/7"))
    )
    (comp (ref "R3")
      (value "10k")
      (footprint "eagle-import:0204_7")
      (libsource (lib "eagle-import") (part "R-US_0204/7"))
    )
    (comp (ref "R4")
      (value "220")
      (footprint "eagle-import:0204_7")
      (libsource (lib "eagle-import") (part "R-US_0204/7"))
    )
    (comp (ref "R5")
      (value "~220")
      (footprint "eagle-import:0204_7")
      (libsource (lib "eagle-import") (part "R-US_0204/7"))
    )
    (comp (ref "R6")
      (value "~220")
      (footprint "eagle-import:0204_7")
      (libsource (lib "eagle-import") (part "R-US_0204/7"))
    )
    (comp (ref "R7")
      (value "220")
      (footprint "eagle-import:0204_7")
      (libsource (lib "eagle-import") (part "R-US_0204/7"))
    )
    (comp (ref "R8")
      (value "~220")
      (footprint "eagle-import:0204_7")
      (libsource (lib "eagle-import") (part "R-US_0204/7"))
    )
    (comp (ref "R9")
      (value "~220")
      (footprint "eagle-import:0204_7")
      (libsource (lib "eagle-import") (part "R-US_0204/7"))
    )
    (comp (ref "R10")
      (value "~220")
      (footprint "eagle-import:0204_7")
      (libsource (lib "eagle-import") (part "R-US_0204/7"))
    )
    (comp (ref "R11")
      (value "~220")
      (footprint "eagle-import:0204_7")
      (libsource (lib "eagle-import") (part "R-US_0204/7"))
    )
    (comp (ref "R12")
      (value "~220")
      (footprint "eagle-import:0204_7")
      (libsource (lib "eagle-import") (part "R-US_0204/7"))
    )
    (comp (ref "R13")
      (value "~220")
      (footprint "eagle-import:0204_7")
      (libsource (lib "eagle-import") (part "R-US_0204/7"))
    )
    (comp (ref "R14")
      (value "~220")
      (footprint "eagle-import:0204_7")
      (libsource (lib "eagle-import") (part "R-US_0204/7"))
    )
    (comp (ref "R15")
      (value "~220")
      (footprint "eagle-import:0204_7")
      (libsource (lib "eagle-import") (part "R-US_0204/7"))
    )
    (comp (ref "R16")
      (value "~220")
      (footprint "eagle-import:0204_7")
      (libsource (lib "eagle-import") (part "R-US_0204/7"))
    )
    (comp (ref "R17")
      (value "~220")
      (footprint "eagle-import:0204_7")
      (libsource (lib "eagle-import") (part "R-US_0204/7"))
    )
    (comp (ref "R18")
      (value "~220")
      (footprint "eagle-import:0204_7")
      (libsource (lib "eagle-import") (part "R-US_0204/7"))
    )
    (comp (ref "R19")
      (value "~220")
      (footprint "eagle-import:0204_7")
      (libsource (lib "eagle-import") (part "R-US_0204/7"))
    )
    (comp (ref "R20")
      (value "~220")
      (footprint "eagle-import:0204_7")
      (libsource (lib "eagle-import") (part "R-US_0204/7"))
    )
    (comp (ref "R21")
      (value "~220")
      (footprint "eagle-import:0204_7")
      (libsource (lib "eagle-import") (part "R-US_0204/7"))
    )
    (comp (ref "R22")
      (value "~220")
      (footprint "eagle-import:0204_7")
      (libsource (lib "eagle-import") (part "R-US_0204/7"))
    )
    (comp (ref "R23")
      (value "~220")
      (footprint "eagle-import:0204_7")
      (libsource (lib "eagle-import") (part "R-US_0204/7"))
    )
    (comp (ref "R24")
      (value "~220")
      (footprint "eagle-import:0204_7")
      (libsource (lib "eagle-import") (part "R-US_0204/7"))
    )
    (comp (ref "R25")
      (value "~220")
      (footprint "eagle-import:0204_7")
      (libsource (lib "eagle-import") (part "R-US_0204/7"))
    )
    (comp (ref "R26")
      (value "~220")
      (footprint "eagle-import:0204_7")
      (libsource (lib "eagle-import") (part "R-US_0204/7"))
    )
    (comp (ref "R27")
      (value "~220")
      (footprint "eagle-import:0204_7")
      (libsource (lib "eagle-import") (part "R-US_0204/7"))
    )
    (comp (ref "R28")
      (value "~220")
      (footprint "eagle-import:0204_7")
      (libsource (lib "eagle-import") (part "R-US_0204/7"))
    )
    (comp (ref "R29")
      (value "~220")
      (footprint "eagle-import:0204_7")
      (libsource (lib "eagle-import") (part "R-US_0204/7"))
    )
    (comp (ref "R30")
      (value "~220")
      (footprint "eagle-import:0204_7")
      (libsource (lib "eagle-import") (part "R-US_0204/7"))
    )
    (comp (ref "R31")
      (value "~220")
      (footprint "eagle-import:0204_7")
      (libsource (lib "eagle-import") (part "R-US_0204/7"))
    )
    (comp (ref "R32")
      (value "~220")
      (footprint "eagle-import:0204_7")
      (libsource (lib "eagle-import") (part "R-US_0204/7"))
    )
    (comp (ref "R33")
      (value "~220")
      (footprint "eagle-import:0204_7")
      (libsource (lib "eagle-import") (part "R-US_0204/7"))
    )
    (comp (ref "R34")
      (value "~220")
      (footprint "eagle-import:0204_7")
      (libsource (lib "eagle-import") (part "R-US_0204/7"))
    )
    (comp (ref "R35")
      (value "~220")
      (footprint "eagle-import:0204_7")
      (libsource (lib "eagle-import") (part "R-US_0204/7"))
    )
    (comp (ref "R36")
      (value "~220")
      (footprint "eagle-import:0204_7")
      (libsource (lib "eagle-import") (part "R-US_0204/7"))
    )
    (comp (ref "R37")
      (value "~220")
      (footprint "eagle-import:0204_7")
      (libsource (lib "eagle-import") (part "R-US_0204/7"))
    )
    (comp (ref "R38")
      (value "~220")
      (footprint "eagle-import:0204_7")
      (libsource (lib "eagle-import") (part "R-US_0204/7"))
    )
    (comp (ref "R39")
      (value "~220")
      (footprint "eagle-import:0204_7")
      (libsource (lib "eagle-import") (part "R-US_0204/7"))
    )
    (comp (ref "R40")
      (value "~220")
      (footprint "eagle-import:0204_7")
      (libsource (lib "eagle-import") (part "R-US_0204/7"))
    )
    (comp (ref "R41")
      (value "~220")
      (footprint "eagle-import:0204_7")
      (libsource (lib "eagle-import") (part "R-US_0204/7"))
    )
    (comp (ref "R42")
      (value "~220")
      (footprint "eagle-import:0204_7")
      (libsource (lib "eagle-import") (part "R-US_0204/7"))
    )
    (comp (ref "R43")
      (value "~220")
      (footprint "eagle-import:0204_7")
      (libsource (lib "eagle-import") (part "R-US_0204/7"))
    )
    (comp (ref "R44")
      (value "~220")
      (footprint "eagle-import:0204_7")
      (libsource (lib "eagle-import") (part "R-US_0204/7"))
    )
    (comp (ref "R45")
      (value "~220")
      (footprint "eagle-import:0204_7")
      (libsource (lib "eagle-import") (part "R-US_0204/7"))
    )
    (comp (ref "R46")
      (value "~220")
      (footprint "eagle-import:0204_7")
      (libsource (lib "eagle-import") (part "R-US_0204/7"))
    )
    (comp (ref "R47")
      (value "~220")
      (footprint "eagle-import:0204_7")
      (libsource (lib "eagle-import") (part "R-US_0204/7"))
    )
    (comp (ref "R48")
      (value "~220")
      (footprint "eagle-import:0204_7")
      (libsource (lib "eagle-import") (part "R-US_0204/7"))
    )
    (comp (ref "R49")
      (value "~220")
      (footprint "eagle-import:0204_7")
      (libsource (lib "eagle-import") (part "R-US_0204/7"))
    )
    (comp (ref "R50")
      (value "~220")
      (footprint "eagle-import:0204_7")
      (libsource (lib "eagle-import") (part "R-US_0204/7"))
    )
    (comp (ref "R51")
      (value "~220")
      (footprint "eagle-import:0204_7")
      (libsource (lib "eagle-import") (part "R-US_0204/7"))
    )
    (comp (ref "R52")
      (value "~220")
      (footprint "eagle-import:0204_7")
      (libsource (lib "eagle-import") (part "R-US_0204/7"))
    )
    (comp (ref "R53")
      (value "~220")
      (footprint "eagle-import:0204_7")
      (libsource (lib "eagle-import") (part "R-US_0204/7"))
    )
    (comp (ref "R54")
      (value "~220")
      (footprint "eagle-import:0204_7")
      (libsource (lib "eagle-import") (part "R-US_0204/7"))
    )
    (comp (ref "R55")
      (value "~220")
      (footprint "eagle-import:0204_7")
      (libsource (lib "eagle-import") (part "R-US_0204/7"))
    )
    (comp (ref "R56")
      (value "~220")
      (footprint "eagle-import:0204_7")
      (libsource (lib "eagle-import") (part "R-US_0204/7"))
    )
    (comp (ref "R57")
      (value "~220")
      (footprint "eagle-import:0204_7")
      (libsource (lib "eagle-import") (part "R-US_0204/7"))
    )
    (comp (ref "R58")
      (value "~220")
      (footprint "eagle-import:0204_7")
      (libsource (lib "eagle-import") (part "R-US_0204/7"))
    )
    (comp (ref "R59")
      (value "~220")
      (footprint "eagle-import:0204_7")
      (libsource (lib "eagle-import") (part "R-US_0204/7"))
    )
    (comp (ref "R60")
      (value "~220")
      (footprint "eagle-import:0204_7")
      (libsource (lib "eagle-import") (part "R-US_0204/7"))
    )
    (comp (ref "R61")
      (value "~220")
      (footprint "eagle-import:0204_7")
      (libsource (lib "eagle-import") (part "R-US_0204/7"))
    )
    (comp (ref "R62")
      (value "~220")
      (footprint "eagle-import:0204_7")
      (libsource (lib "eagle-import") (part "R-US_0204/7"))
    )
    (comp (ref "R63")
      (value "~220")
      (footprint "eagle-import:0204_7")
      (libsource (lib "eagle-import") (part "R-US_0204/7"))
    )
    (comp (ref "R64")
      (value "~220")
      (footprint "eagle-import:0204_7")
      (libsource (lib "eagle-import") (part "R-US_0204/7"))
    )
    (comp (ref "R65")
      (value "~220")
      (footprint "eagle-import:0204_7")
      (libsource (lib "eagle-import") (part "R-US_0204/7"))
    )
    (comp (ref "R66")
      (value "~220")
      (footprint "eagle-import:0204_7")
      (libsource (lib "eagle-import") (part "R-US_0204/7"))
    )
    (comp (ref "R67")
      (value "~220")
      (footprint "eagle-import:0204_7")
      (libsource (lib "eagle-import") (part "R-US_0204/7"))
    )
    (comp (ref "R68")
      (value "~220")
      (footprint "eagle-import:0204_7")
      (libsource (lib "eagle-import") (part "R-US_0204/7"))
    )
    (comp (ref "R69")
      (value "~220")
      (footprint "eagle-import:0204_7")
      (libsource (lib "eagle-import") (part "R-US_0204/7"))
    )
    (comp (ref "R70")
      (value "~220")
      (footprint "eagle-import:0204_7")
      (libsource (lib "eagle-import") (part "R-US_0204/7"))
    )
    (comp (ref "R71")
      (value "~220")
      (footprint "eagle-import:0204_7")
      (libsource (lib "eagle-import") (part "R-US_0204/7"))
    )
    (comp (ref "R72")
      (value "~220")
      (footprint "eagle-import:0204_7")
      (libsource (lib "eagle-import") (part "R-US_0204/7"))
    )
    (comp (ref "R73")
      (value "~220")
      (footprint "eagle-import:0204_7")
      (libsource (lib "eagle-import") (part "R-US_0204/7"))
    )
    (comp (ref "R74")
      (value "~220")
      (footprint "eagle-import:0204_7")
      (libsource (lib "eagle-import") (part "R-US_0204/7"))
    )
    (comp (ref "R75")
      (value "~220")
      (footprint "eagle-import:0204_7")
      (libsource (lib "eagle-import") (part "R-US_0204/7"))
    )
    (comp (ref "R76")
      (value "~220")
      (footprint "eagle-import:0204_7")
      (libsource (lib "eagle-import") (part "R-US_0204/7"))
    )
    (comp (ref "R77")
      (value "~220")
      (footprint "eagle-import:0204_7")
      (libsource (lib "eagle-import") (part "R-US_0204/7"))
    )
    (comp (ref "R78")
      (value "~220")
      (footprint "eagle-import:0204_7")
      (libsource (lib "eagle-import") (part "R-US_0204/7"))
    )
    (comp (ref "R79")
      (value "~220")
      (footprint "eagle-import:0204_7")
      (libsource (lib "eagle-import") (part "R-US_0204/7"))
    )
    (comp (ref "R80")
      (value "~220")
      (footprint "eagle-import:0204_7")
      (libsource (lib "eagle-import") (part "R-US_0204/7"))
    )
    (comp (ref "R81")
      (value "~220")
      (footprint "eagle-import:0204_7")
      (libsource (lib "eagle-import") (part "R-US_0204/7"))
    )
    (comp (ref "RAM")
      (value "71256SA15TPG")
      (footprint "eagle-import:DIL28-3")
      (libsource (lib "eagle-import") (part "DIL28-3"))
    )
    (comp (ref "RAM_ADDR_LOWER")
      (value "74LS173N")
      (footprint "eagle-import:DIL16")
      (libsource (lib "eagle-import") (part "74173NLS"))
    )
    (comp (ref "RAM_ADDR_UPPER")
      (value "74LS173N")
      (footprint "eagle-import:DIL16")
      (libsource (lib "eagle-import") (part "74173NLS"))
    )
    (comp (ref "RAM_LED_1")
      (value "LED3MM")
      (footprint "eagle-import:LED3MM")
      (libsource (lib "eagle-import") (part "LED3MM"))
    )
    (comp (ref "RAM_LED_2")
      (value "LED3MM")
      (footprint "eagle-import:LED3MM")
      (libsource (lib "eagle-import") (part "LED3MM"))
    )
    (comp (ref "RAM_LED_3")
      (value "LED3MM")
      (footprint "eagle-import:LED3MM")
      (libsource (lib "eagle-import") (part "LED3MM"))
    )
    (comp (ref "RAM_LED_4")
      (value "LED3MM")
      (footprint "eagle-import:LED3MM")
      (libsource (lib "eagle-import") (part "LED3MM"))
    )
    (comp (ref "RAM_LED_5")
      (value "LED3MM")
      (footprint "eagle-import:LED3MM")
      (libsource (lib "eagle-import") (part "LED3MM"))
    )
    (comp (ref "RAM_LED_6")
      (value "LED3MM")
      (footprint "eagle-import:LED3MM")
      (libsource (lib "eagle-import") (part "LED3MM"))
    )
    (comp (ref "RAM_LED_7")
      (value "LED3MM")
      (footprint "eagle-import:LED3MM")
      (libsource (lib "eagle-import") (part "LED3MM"))
    )
    (comp (ref "RAM_LED_8")
      (value "LED3MM")
      (footprint "eagle-import:LED3MM")
      (libsource (lib "eagle-import") (part "LED3MM"))
    )
    (comp (ref "RESET_PC")
      (value "NORM-OFF")
      (footprint "eagle-import:B3F-10XX")
      (fields (field (name "MPN") "B3F-1000"))
      (libsource (lib "eagle-import") (part "10-XX"))
    )
    (comp (ref "RESET_REGS")
      (value "NORM-OFF")
      (footprint "eagle-import:B3F-10XX")
      (fields (field (name "MPN") "B3F-1000"))
      (libsource (lib "eagle-import") (part "10-XX"))
    )
    (comp (ref "SELECTOR_LOGIC2_")
      (value "74HC139N")
      (footprint "eagle-import:DIL16")
      (libsource (lib "eagle-import") (part "74139NHC"))
    )
    (comp (ref "SELECTOR_LOGIC_")
      (value "74HC139N")
      (footprint "eagle-import:DIL16")
      (libsource (lib "eagle-import") (part "74139NHC"))
    )
    (comp (ref "STEPPER_CLOCK")
      (value "NE555N")
      (footprint "eagle-import:DIL08")
      (libsource (lib "eagle-import") (part "555NNE"))
    )
    (comp (ref "SUBTRACT_INVRTR_LOWER_")
      (value "74LS86N")
      (footprint "eagle-import:DIL14")
      (libsource (lib "eagle-import") (part "7486NLS"))
    )
    (comp (ref "SUBTRACT_INVRTR_UPPER_")
      (value "74LS86N")
      (footprint "eagle-import:DIL14")
      (libsource (lib "eagle-import") (part "7486NLS"))
    )
    (comp (ref "USTEP_1")
      (value "LED5MM")
      (footprint "eagle-import:LED5MM")
      (libsource (lib "eagle-import") (part "LED5MM"))
    )
    (comp (ref "USTEP_2")
      (value "LED5MM")
      (footprint "eagle-import:LED5MM")
      (libsource (lib "eagle-import") (part "LED5MM"))
    )
    (comp (ref "USTEP_3")
      (value "LED5MM")
      (footprint "eagle-import:LED5MM")
      (libsource (lib "eagle-import") (part "LED5MM"))
    )
    (comp (ref "USTEP_4")
      (value "LED5MM")
      (footprint "eagle-import:LED5MM")
      (libsource (lib "eagle-import") (part "LED5MM"))
    )
    (comp (ref "USTEP_5")
      (value "LED5MM")
      (footprint "eagle-import:LED5MM")
      (libsource (lib "eagle-import") (part "LED5MM"))
    )
    (comp (ref "X1")
      (value "SSW-103-02-G-S")
      (footprint "eagle-import:SSW-103-02-G-S")
      (fields (field (name "MF") "Samtec Inc."))
      (libsource (lib "eagle-import") (part "SSW-103-02-G-S"))
    )
    (comp (ref "XOR_GATE_1")
      (value "74LS86N")
      (footprint "eagle-import:DIL14")
      (libsource (lib "eagle-import") (part "7486NLS"))
    )
    (comp (ref "XOR_GATE_2")
      (value "74LS86N")
      (footprint "eagle-import:DIL14")
      (libsource (lib "eagle-import") (part "7486NLS"))
    )
    (comp (ref "XOR_LOGIC_LOWER")
      (value "74LS86N")
      (footprint "eagle-import:DIL14")
      (libsource (lib "eagle-import") (part "7486NLS"))
    )
    (comp (ref "XOR_LOGIC_UPPER")
      (value "74LS86N")
      (footprint "eagle-import:DIL14")
      (libsource (lib "eagle-import") (part "7486NLS"))
    )
    (comp (ref "ZERO_FLAG")
      (value "LED5MM")
      (footprint "eagle-import:LED5MM")
      (libsource (lib "eagle-import") (part "LED5MM"))
    )
    (comp (ref "ZERO_POS_FLAG_IDENTIFIER")
      (value "744078N")
      (footprint "eagle-import:DIL14")
      (libsource (lib "eagle-import") (part "744078N"))
    )
  )
  (nets
    (net (code "1") (name "GND") (class "Default")
      (node (ref "4_INP_OR_GATE") (pin "7") (pinfunction "VSS_7") (pintype "power_in"))
      (node (ref "ADDR_MEM_REG_LOWER") (pin "1") (pinfunction "M_1") (pintype "input"))
      (node (ref "ADDR_MEM_REG_LOWER") (pin "2") (pinfunction "N_2") (pintype "input"))
      (node (ref "ADDR_MEM_REG_UPPER") (pin "1") (pinfunction "M_1") (pintype "input"))
      (node (ref "ADDR_MEM_REG_UPPER") (pin "2") (pinfunction "N_2") (pintype "input"))
      (node (ref "ADDR_REG_A_LOWER") (pin "1") (pinfunction "M_1") (pintype "input"))
      (node (ref "ADDR_REG_A_LOWER") (pin "2") (pinfunction "N_2") (pintype "input"))
      (node (ref "ADDR_REG_A_UPPER") (pin "1") (pinfunction "M_1") (pintype "input"))
      (node (ref "ADDR_REG_A_UPPER") (pin "2") (pinfunction "N_2") (pintype "input"))
      (node (ref "ADDR_REG_CALC_LOWER") (pin "1") (pinfunction "M_1") (pintype "input"))
      (node (ref "ADDR_REG_CALC_LOWER") (pin "2") (pinfunction "N_2") (pintype "input"))
      (node (ref "ADDR_REG_CALC_UPPER") (pin "1") (pinfunction "M_1") (pintype "input"))
      (node (ref "ADDR_REG_CALC_UPPER") (pin "2") (pinfunction "N_2") (pintype "input"))
      (node (ref "ADDR_REG_PARAM_LOWER") (pin "1") (pinfunction "M_1") (pintype "input"))
      (node (ref "ADDR_REG_PARAM_LOWER") (pin "2") (pinfunction "N_2") (pintype "input"))
      (node (ref "ADDR_REG_PARAM_UPPER") (pin "1") (pinfunction "M_1") (pintype "input"))
      (node (ref "ADDR_REG_PARAM_UPPER") (pin "2") (pinfunction "N_2") (pintype "input"))
      (node (ref "AUTO_CLOCK") (pin "1") (pinfunction "GND_1") (pintype "power_in"))
      (node (ref "BRANCH_SELECTOR") (pin "1") (pinfunction "G_1") (pintype "input"))
      (node (ref "BRANCH_SELECTOR") (pin "15") (pinfunction "G_15") (pintype "input"))
      (node (ref "C1") (pin "-") (pinfunction "-_-") (pintype "passive"))
      (node (ref "C2") (pin "-") (pinfunction "-_-") (pintype "passive"))
      (node (ref "C3") (pin "-") (pinfunction "-_-") (pintype "passive"))
      (node (ref "CLK_TRIGGER") (pin "3") (pinfunction "P_3") (pintype "passive"))
      (node (ref "EXTENSION") (pin "11") (pinfunction "1_11") (pintype "passive"))
      (node (ref "FLAG_REG_LOWER") (pin "1") (pinfunction "M_1") (pintype "input"))
      (node (ref "FLAG_REG_LOWER") (pin "2") (pinfunction "N_2") (pintype "input"))
      (node (ref "FLAG_REG_UPPER") (pin "1") (pinfunction "M_1") (pintype "input"))
      (node (ref "FLAG_REG_UPPER") (pin "2") (pinfunction "N_2") (pintype "input"))
      (node (ref "INSRUCTION_REGISTER_SELECTOR_LOWER") (pin "11") (pinfunction "3A_11") (pintype "input"))
      (node (ref "INSRUCTION_REGISTER_SELECTOR_LOWER") (pin "14") (pinfunction "4A_14") (pintype "input"))
      (node (ref "INSRUCTION_REGISTER_SELECTOR_LOWER") (pin "15") (pinfunction "G_15") (pintype "input"))
      (node (ref "INSRUCTION_REGISTER_SELECTOR_LOWER") (pin "2") (pinfunction "1A_2") (pintype "input"))
      (node (ref "INSRUCTION_REGISTER_SELECTOR_LOWER") (pin "5") (pinfunction "2A_5") (pintype "input"))
      (node (ref "INSRUCTION_REGISTER_SELECTOR_UPPER") (pin "11") (pinfunction "3A_11") (pintype "input"))
      (node (ref "INSRUCTION_REGISTER_SELECTOR_UPPER") (pin "14") (pinfunction "4A_14") (pintype "input"))
      (node (ref "INSRUCTION_REGISTER_SELECTOR_UPPER") (pin "15") (pinfunction "G_15") (pintype "input"))
      (node (ref "INSRUCTION_REGISTER_SELECTOR_UPPER") (pin "2") (pinfunction "1A_2") (pintype "input"))
      (node (ref "INSRUCTION_REGISTER_SELECTOR_UPPER") (pin "5") (pinfunction "2A_5") (pintype "input"))
      (node (ref "INSTRUCTIONS_EXTENSION") (pin "15") (pinfunction "1_15") (pintype "passive"))
      (node (ref "INSTRUCTION_MEMORY_0") (pin "14") (pinfunction "14_14") (pintype "passive"))
      (node (ref "INSTRUCTION_MEMORY_0") (pin "20") (pinfunction "20_20") (pintype "passive"))
      (node (ref "INSTRUCTION_MEMORY_0") (pin "22") (pinfunction "22_22") (pintype "passive"))
      (node (ref "INSTRUCTION_MEMORY_1") (pin "14") (pinfunction "14_14") (pintype "passive"))
      (node (ref "INSTRUCTION_MEMORY_1") (pin "20") (pinfunction "20_20") (pintype "passive"))
      (node (ref "INSTRUCTION_MEMORY_1") (pin "22") (pinfunction "22_22") (pintype "passive"))
      (node (ref "INSTRUCTION_MEMORY_2") (pin "14") (pinfunction "14_14") (pintype "passive"))
      (node (ref "INSTRUCTION_MEMORY_2") (pin "20") (pinfunction "20_20") (pintype "passive"))
      (node (ref "INSTRUCTION_MEMORY_2") (pin "22") (pinfunction "22_22") (pintype "passive"))
      (node (ref "INSTRUC_REGISTER_LOWER") (pin "1") (pinfunction "M_1") (pintype "input"))
      (node (ref "INSTRUC_REGISTER_LOWER") (pin "2") (pinfunction "N_2") (pintype "input"))
      (node (ref "INSTRUC_REGISTER_UPPER") (pin "1") (pinfunction "M_1") (pintype "input"))
      (node (ref "INSTRUC_REGISTER_UPPER") (pin "2") (pinfunction "N_2") (pintype "input"))
      (node (ref "MEMORY") (pin "14") (pinfunction "14_14") (pintype "passive"))
      (node (ref "MEMORY") (pin "2") (pinfunction "2_2") (pintype "passive"))
      (node (ref "MEMORY") (pin "20") (pinfunction "20_20") (pintype "passive"))
      (node (ref "MEMORY") (pin "21") (pinfunction "21_21") (pintype "passive"))
      (node (ref "MEMORY") (pin "22") (pinfunction "22_22") (pintype "passive"))
      (node (ref "MEMORY") (pin "23") (pinfunction "23_23") (pintype "passive"))
      (node (ref "MEMORY") (pin "24") (pinfunction "24_24") (pintype "passive"))
      (node (ref "MICRO_COUNTER_LOWER") (pin "8") (pinfunction "8_8") (pintype "passive"))
      (node (ref "MICRO_COUNTER_UPPER") (pin "8") (pinfunction "8_8") (pintype "passive"))
      (node (ref "OUTPUT_BUFFER_ALU") (pin "1") (pinfunction "DIR_1") (pintype "input"))
      (node (ref "OUTPUT_BUFFER_FLAGS") (pin "1") (pinfunction "DIR_1") (pintype "input"))
      (node (ref "PROGRAM_COUNTER_LOWER") (pin "8") (pinfunction "8_8") (pintype "passive"))
      (node (ref "PROGRAM_COUNTER_UPPER") (pin "8") (pinfunction "8_8") (pintype "passive"))
      (node (ref "R10") (pin "1") (pinfunction "1_1") (pintype "passive"))
      (node (ref "R11") (pin "1") (pinfunction "1_1") (pintype "passive"))
      (node (ref "R12") (pin "1") (pinfunction "1_1") (pintype "passive"))
      (node (ref "R13") (pin "1") (pinfunction "1_1") (pintype "passive"))
      (node (ref "R14") (pin "1") (pinfunction "1_1") (pintype "passive"))
      (node (ref "R15") (pin "1") (pinfunction "1_1") (pintype "passive"))
      (node (ref "R16") (pin "2") (pinfunction "2_2") (pintype "passive"))
      (node (ref "R17") (pin "2") (pinfunction "2_2") (pintype "passive"))
      (node (ref "R18") (pin "2") (pinfunction "2_2") (pintype "passive"))
      (node (ref "R19") (pin "2") (pinfunction "2_2") (pintype "passive"))
      (node (ref "R20") (pin "2") (pinfunction "2_2") (pintype "passive"))
      (node (ref "R21") (pin "2") (pinfunction "2_2") (pintype "passive"))
      (node (ref "R22") (pin "2") (pinfunction "2_2") (pintype "passive"))
      (node (ref "R23") (pin "2") (pinfunction "2_2") (pintype "passive"))
      (node (ref "R24") (pin "2") (pinfunction "2_2") (pintype "passive"))
      (node (ref "R25") (pin "2") (pinfunction "2_2") (pintype "passive"))
      (node (ref "R26") (pin "2") (pinfunction "2_2") (pintype "passive"))
      (node (ref "R27") (pin "2") (pinfunction "2_2") (pintype "passive"))
      (node (ref "R28") (pin "2") (pinfunction "2_2") (pintype "passive"))
      (node (ref "R29") (pin "2") (pinfunction "2_2") (pintype "passive"))
      (node (ref "R30") (pin "2") (pinfunction "2_2") (pintype "passive"))
      (node (ref "R31") (pin "2") (pinfunction "2_2") (pintype "passive"))
      (node (ref "R32") (pin "2") (pinfunction "2_2") (pintype "passive"))
      (node (ref "R33") (pin "2") (pinfunction "2_2") (pintype "passive"))
      (node (ref "R34") (pin "2") (pinfunction "2_2") (pintype "passive"))
      (node (ref "R35") (pin "2") (pinfunction "2_2") (pintype "passive"))
      (node (ref "R36") (pin "2") (pinfunction "2_2") (pintype "passive"))
      (node (ref "R37") (pin "2") (pinfunction "2_2") (pintype "passive"))
      (node (ref "R38") (pin "2") (pinfunction "2_2") (pintype "passive"))
      (node (ref "R39") (pin "2") (pinfunction "2_2") (pintype "passive"))
      (node (ref "R4") (pin "1") (pinfunction "1_1") (pintype "passive"))
      (node (ref "R40") (pin "1") (pinfunction "1_1") (pintype "passive"))
      (node (ref "R41") (pin "1") (pinfunction "1_1") (pintype "passive"))
      (node (ref "R42") (pin "1") (pinfunction "1_1") (pintype "passive"))
      (node (ref "R43") (pin "1") (pinfunction "1_1") (pintype "passive"))
      (node (ref "R44") (pin "1") (pinfunction "1_1") (pintype "passive"))
      (node (ref "R45") (pin "1") (pinfunction "1_1") (pintype "passive"))
      (node (ref "R46") (pin "2") (pinfunction "2_2") (pintype "passive"))
      (node (ref "R47") (pin "2") (pinfunction "2_2") (pintype "passive"))
      (node (ref "R48") (pin "2") (pinfunction "2_2") (pintype "passive"))
      (node (ref "R49") (pin "2") (pinfunction "2_2") (pintype "passive"))
      (node (ref "R5") (pin "1") (pinfunction "1_1") (pintype "passive"))
      (node (ref "R50") (pin "2") (pinfunction "2_2") (pintype "passive"))
      (node (ref "R51") (pin "2") (pinfunction "2_2") (pintype "passive"))
      (node (ref "R52") (pin "2") (pinfunction "2_2") (pintype "passive"))
      (node (ref "R53") (pin "2") (pinfunction "2_2") (pintype "passive"))
      (node (ref "R54") (pin "2") (pinfunction "2_2") (pintype "passive"))
      (node (ref "R55") (pin "2") (pinfunction "2_2") (pintype "passive"))
      (node (ref "R56") (pin "2") (pinfunction "2_2") (pintype "passive"))
      (node (ref "R57") (pin "2") (pinfunction "2_2") (pintype "passive"))
      (node (ref "R58") (pin "2") (pinfunction "2_2") (pintype "passive"))
      (node (ref "R59") (pin "2") (pinfunction "2_2") (pintype "passive"))
      (node (ref "R6") (pin "2") (pinfunction "2_2") (pintype "passive"))
      (node (ref "R60") (pin "2") (pinfunction "2_2") (pintype "passive"))
      (node (ref "R61") (pin "2") (pinfunction "2_2") (pintype "passive"))
      (node (ref "R62") (pin "2") (pinfunction "2_2") (pintype "passive"))
      (node (ref "R63") (pin "2") (pinfunction "2_2") (pintype "passive"))
      (node (ref "R64") (pin "2") (pinfunction "2_2") (pintype "passive"))
      (node (ref "R65") (pin "2") (pinfunction "2_2") (pintype "passive"))
      (node (ref "R66") (pin "2") (pinfunction "2_2") (pintype "passive"))
      (node (ref "R67") (pin "2") (pinfunction "2_2") (pintype "passive"))
      (node (ref "R68") (pin "2") (pinfunction "2_2") (pintype "passive"))
      (node (ref "R69") (pin "2") (pinfunction "2_2") (pintype "passive"))
      (node (ref "R70") (pin "2") (pinfunction "2_2") (pintype "passive"))
      (node (ref "R71") (pin "2") (pinfunction "2_2") (pintype "passive"))
      (node (ref "R72") (pin "2") (pinfunction "2_2") (pintype "passive"))
      (node (ref "R73") (pin "2") (pinfunction "2_2") (pintype "passive"))
      (node (ref "R74") (pin "2") (pinfunction "2_2") (pintype "passive"))
      (node (ref "R75") (pin "2") (pinfunction "2_2") (pintype "passive"))
      (node (ref "R76") (pin "2") (pinfunction "2_2") (pintype "passive"))
      (node (ref "R77") (pin "1") (pinfunction "1_1") (pintype "passive"))
      (node (ref "R78") (pin "1") (pinfunction "1_1") (pintype "passive"))
      (node (ref "R79") (pin "1") (pinfunction "1_1") (pintype "passive"))
      (node (ref "R8") (pin "1") (pinfunction "1_1") (pintype "passive"))
      (node (ref "R81") (pin "2") (pinfunction "2_2") (pintype "passive"))
      (node (ref "R9") (pin "1") (pinfunction "1_1") (pintype "passive"))
      (node (ref "RAM") (pin "1") (pinfunction "1_1") (pintype "passive"))
      (node (ref "RAM") (pin "14") (pinfunction "14_14") (pintype "passive"))
      (node (ref "RAM") (pin "2") (pinfunction "2_2") (pintype "passive"))
      (node (ref "RAM") (pin "20") (pinfunction "20_20") (pintype "passive"))
      (node (ref "RAM") (pin "21") (pinfunction "21_21") (pintype "passive"))
      (node (ref "RAM") (pin "23") (pinfunction "23_23") (pintype "passive"))
      (node (ref "RAM") (pin "24") (pinfunction "24_24") (pintype "passive"))
      (node (ref "RAM") (pin "25") (pinfunction "25_25") (pintype "passive"))
      (node (ref "RAM") (pin "26") (pinfunction "26_26") (pintype "passive"))
      (node (ref "RAM_ADDR_LOWER") (pin "1") (pinfunction "M_1") (pintype "input"))
      (node (ref "RAM_ADDR_LOWER") (pin "2") (pinfunction "N_2") (pintype "input"))
      (node (ref "RAM_ADDR_UPPER") (pin "1") (pinfunction "M_1") (pintype "input"))
      (node (ref "RAM_ADDR_UPPER") (pin "2") (pinfunction "N_2") (pintype "input"))
      (node (ref "RESET_PC") (pin "4") (pinfunction "P1_4") (pintype "passive"))
      (node (ref "SELECTOR_LOGIC2_") (pin "1") (pinfunction "G_1") (pintype "input"))
      (node (ref "SELECTOR_LOGIC2_") (pin "15") (pinfunction "G_15") (pintype "input"))
      (node (ref "SELECTOR_LOGIC_") (pin "1") (pinfunction "G_1") (pintype "input"))
      (node (ref "SELECTOR_LOGIC_") (pin "15") (pinfunction "G_15") (pintype "input"))
      (node (ref "STEPPER_CLOCK") (pin "1") (pinfunction "GND_1") (pintype "power_in"))
      (node (ref "X1") (pin "1") (pinfunction "1_1") (pintype "passive"))
      (node (ref "ZERO_POS_FLAG_IDENTIFIER") (pin "7") (pinfunction "-UB_7") (pintype "power_in"))
    )
    (net (code "2") (name "Net-(4_INP_OR_GATEA-I0)") (class "Default")
      (node (ref "4_INP_OR_GATE") (pin "2") (pinfunction "I0_2") (pintype "input"))
      (node (ref "NOT_GATE4_") (pin "2") (pinfunction "O_2") (pintype "output"))
    )
    (net (code "3") (name "Net-(4_INP_OR_GATEA-I1)") (class "Default")
      (node (ref "4_INP_OR_GATE") (pin "3") (pinfunction "I1_3") (pintype "input"))
      (node (ref "AND_GATE3_") (pin "11") (pinfunction "O_11") (pintype "output"))
    )
    (net (code "4") (name "Net-(4_INP_OR_GATEA-I2)") (class "Default")
      (node (ref "4_INP_OR_GATE") (pin "4") (pinfunction "I2_4") (pintype "input"))
      (node (ref "AND_GATE4_") (pin "3") (pinfunction "O_3") (pintype "output"))
    )
    (net (code "5") (name "Net-(4_INP_OR_GATEA-I3)") (class "Default")
      (node (ref "4_INP_OR_GATE") (pin "5") (pinfunction "I3_5") (pintype "input"))
      (node (ref "AND_GATE4_") (pin "6") (pinfunction "O_6") (pintype "output"))
    )
    (net (code "6") (name "Net-(4_INP_OR_GATEA-O)") (class "Default")
      (node (ref "4_INP_OR_GATE") (pin "1") (pinfunction "O_1") (pintype "output"))
      (node (ref "AND_GATE3_") (pin "4") (pinfunction "I0_4") (pintype "input"))
      (node (ref "AND_GATE3_") (pin "9") (pinfunction "I0_9") (pintype "input"))
    )
    (net (code "7") (name "Net-(ADDER_LOWERA-A1)") (class "Default")
      (node (ref "ADDER_LOWER") (pin "5") (pinfunction "A1_5") (pintype "input"))
      (node (ref "ADDR_REG_A_LOWER") (pin "6") (pinfunction "Q4_6") (pintype "tri_state"))
      (node (ref "AND_GATE1_") (pin "1") (pinfunction "I0_1") (pintype "input"))
      (node (ref "LED_A_REG_1") (pin "A") (pinfunction "A_A") (pintype "passive"))
      (node (ref "NOT_GATE5_") (pin "1") (pinfunction "I_1") (pintype "input"))
      (node (ref "OR_GATE2_") (pin "12") (pinfunction "I0_12") (pintype "input"))
      (node (ref "OUTPUT_BUFFER_REG_A") (pin "9") (pinfunction "A8_9") (pintype "bidirectional"))
      (node (ref "XOR_LOGIC_LOWER") (pin "2") (pinfunction "I1_2") (pintype "input"))
      (node (ref "ZERO_POS_FLAG_IDENTIFIER") (pin "5") (pinfunction "D_5") (pintype "input"))
    )
    (net (code "8") (name "Net-(ADDER_LOWERA-A2)") (class "Default")
      (node (ref "ADDER_LOWER") (pin "3") (pinfunction "A2_3") (pintype "input"))
      (node (ref "ADDR_REG_A_LOWER") (pin "5") (pinfunction "Q3_5") (pintype "tri_state"))
      (node (ref "AND_GATE1_") (pin "4") (pinfunction "I0_4") (pintype "input"))
      (node (ref "LED_A_REG_2") (pin "A") (pinfunction "A_A") (pintype "passive"))
      (node (ref "NOT_GATE5_") (pin "3") (pinfunction "I_3") (pintype "input"))
      (node (ref "OR_GATE2_") (pin "10") (pinfunction "I1_10") (pintype "input"))
      (node (ref "OUTPUT_BUFFER_REG_A") (pin "8") (pinfunction "A7_8") (pintype "bidirectional"))
      (node (ref "XOR_LOGIC_LOWER") (pin "5") (pinfunction "I1_5") (pintype "input"))
      (node (ref "ZERO_POS_FLAG_IDENTIFIER") (pin "4") (pinfunction "C_4") (pintype "input"))
    )
    (net (code "9") (name "Net-(ADDER_LOWERA-A3)") (class "Default")
      (node (ref "ADDER_LOWER") (pin "14") (pinfunction "A3_14") (pintype "input"))
      (node (ref "ADDR_REG_A_LOWER") (pin "4") (pinfunction "Q2_4") (pintype "tri_state"))
      (node (ref "AND_GATE1_") (pin "9") (pinfunction "I0_9") (pintype "input"))
      (node (ref "LED_A_REG_3") (pin "A") (pinfunction "A_A") (pintype "passive"))
      (node (ref "NOT_GATE5_") (pin "5") (pinfunction "I_5") (pintype "input"))
      (node (ref "OR_GATE2_") (pin "5") (pinfunction "I1_5") (pintype "input"))
      (node (ref "OUTPUT_BUFFER_REG_A") (pin "7") (pinfunction "A6_7") (pintype "bidirectional"))
      (node (ref "XOR_LOGIC_LOWER") (pin "10") (pinfunction "I1_10") (pintype "input"))
      (node (ref "ZERO_POS_FLAG_IDENTIFIER") (pin "3") (pinfunction "B_3") (pintype "input"))
    )
    (net (code "10") (name "Net-(ADDER_LOWERA-A4)") (class "Default")
      (node (ref "ADDER_LOWER") (pin "12") (pinfunction "A4_12") (pintype "input"))
      (node (ref "ADDR_REG_A_LOWER") (pin "3") (pinfunction "Q1_3") (pintype "tri_state"))
      (node (ref "AND_GATE4_") (pin "12") (pinfunction "I0_12") (pintype "input"))
      (node (ref "LED_A_REG_4") (pin "A") (pinfunction "A_A") (pintype "passive"))
      (node (ref "NOT_GATE5_") (pin "9") (pinfunction "I_9") (pintype "input"))
      (node (ref "OR_GATE2_") (pin "2") (pinfunction "I1_2") (pintype "input"))
      (node (ref "OUTPUT_BUFFER_REG_A") (pin "6") (pinfunction "A5_6") (pintype "bidirectional"))
      (node (ref "XOR_LOGIC_LOWER") (pin "13") (pinfunction "I1_13") (pintype "input"))
      (node (ref "ZERO_POS_FLAG_IDENTIFIER") (pin "2") (pinfunction "A_2") (pintype "input"))
    )
    (net (code "11") (name "Net-(ADDER_LOWERA-B1)") (class "Default")
      (node (ref "ADDER_LOWER") (pin "6") (pinfunction "B1_6") (pintype "input"))
      (node (ref "SUBTRACT_INVRTR_LOWER_") (pin "11") (pinfunction "O_11") (pintype "output"))
    )
    (net (code "12") (name "Net-(ADDER_LOWERA-B2)") (class "Default")
      (node (ref "ADDER_LOWER") (pin "2") (pinfunction "B2_2") (pintype "input"))
      (node (ref "SUBTRACT_INVRTR_LOWER_") (pin "8") (pinfunction "O_8") (pintype "output"))
    )
    (net (code "13") (name "Net-(ADDER_LOWERA-B3)") (class "Default")
      (node (ref "ADDER_LOWER") (pin "15") (pinfunction "B3_15") (pintype "input"))
      (node (ref "SUBTRACT_INVRTR_LOWER_") (pin "6") (pinfunction "O_6") (pintype "output"))
    )
    (net (code "14") (name "Net-(ADDER_LOWERA-B4)") (class "Default")
      (node (ref "ADDER_LOWER") (pin "11") (pinfunction "B4_11") (pintype "input"))
      (node (ref "SUBTRACT_INVRTR_LOWER_") (pin "3") (pinfunction "O_3") (pintype "output"))
    )
    (net (code "15") (name "Net-(ADDER_LOWERA-C0)") (class "Default")
      (node (ref "ADDER_LOWER") (pin "7") (pinfunction "C0_7") (pintype "input"))
      (node (ref "INSTRUCTION_MEMORY_1") (pin "15") (pinfunction "15_15") (pintype "passive"))
      (node (ref "SUBTRACT_INVRTR_LOWER_") (pin "1") (pinfunction "I0_1") (pintype "input"))
      (node (ref "SUBTRACT_INVRTR_LOWER_") (pin "12") (pinfunction "I0_12") (pintype "input"))
      (node (ref "SUBTRACT_INVRTR_LOWER_") (pin "4") (pinfunction "I0_4") (pintype "input"))
      (node (ref "SUBTRACT_INVRTR_LOWER_") (pin "9") (pinfunction "I0_9") (pintype "input"))
      (node (ref "SUBTRACT_INVRTR_UPPER_") (pin "1") (pinfunction "I0_1") (pintype "input"))
      (node (ref "SUBTRACT_INVRTR_UPPER_") (pin "12") (pinfunction "I0_12") (pintype "input"))
      (node (ref "SUBTRACT_INVRTR_UPPER_") (pin "4") (pinfunction "I0_4") (pintype "input"))
      (node (ref "SUBTRACT_INVRTR_UPPER_") (pin "9") (pinfunction "I0_9") (pintype "input"))
    )
    (net (code "16") (name "Net-(ADDER_LOWERA-C4)") (class "Default")
      (node (ref "ADDER_LOWER") (pin "9") (pinfunction "C4_9") (pintype "output"))
      (node (ref "ADDER_UPPER") (pin "7") (pinfunction "C0_7") (pintype "input"))
    )
    (net (code "17") (name "Net-(ADDER_LOWERA-S1)") (class "Default")
      (node (ref "ADDER_LOWER") (pin "4") (pinfunction "S1_4") (pintype "output"))
      (node (ref "OUTPUT_BUFFER_ALU") (pin "18") (pinfunction "B1_18") (pintype "bidirectional"))
    )
    (net (code "18") (name "Net-(ADDER_LOWERA-S2)") (class "Default")
      (node (ref "ADDER_LOWER") (pin "1") (pinfunction "S2_1") (pintype "output"))
      (node (ref "OUTPUT_BUFFER_ALU") (pin "17") (pinfunction "B2_17") (pintype "bidirectional"))
    )
    (net (code "19") (name "Net-(ADDER_LOWERA-S3)") (class "Default")
      (node (ref "ADDER_LOWER") (pin "13") (pinfunction "S3_13") (pintype "output"))
      (node (ref "OUTPUT_BUFFER_ALU") (pin "16") (pinfunction "B3_16") (pintype "bidirectional"))
    )
    (net (code "20") (name "Net-(ADDER_LOWERA-S4)") (class "Default")
      (node (ref "ADDER_LOWER") (pin "10") (pinfunction "S4_10") (pintype "output"))
      (node (ref "OUTPUT_BUFFER_ALU") (pin "15") (pinfunction "B4_15") (pintype "bidirectional"))
    )
    (net (code "21") (name "Net-(ADDER_UPPERA-A1)") (class "Default")
      (node (ref "ADDER_UPPER") (pin "5") (pinfunction "A1_5") (pintype "input"))
      (node (ref "ADDR_REG_A_UPPER") (pin "6") (pinfunction "Q4_6") (pintype "tri_state"))
      (node (ref "AND_GATE2_") (pin "1") (pinfunction "I0_1") (pintype "input"))
      (node (ref "LED_A_REG_5") (pin "A") (pinfunction "A_A") (pintype "passive"))
      (node (ref "NOT_GATE5_") (pin "11") (pinfunction "I_11") (pintype "input"))
      (node (ref "OR_GATE1_") (pin "13") (pinfunction "I1_13") (pintype "input"))
      (node (ref "OUTPUT_BUFFER_REG_A") (pin "5") (pinfunction "A4_5") (pintype "bidirectional"))
      (node (ref "XOR_LOGIC_UPPER") (pin "2") (pinfunction "I1_2") (pintype "input"))
      (node (ref "ZERO_POS_FLAG_IDENTIFIER") (pin "9") (pinfunction "E_9") (pintype "input"))
    )
    (net (code "22") (name "Net-(ADDER_UPPERA-A2)") (class "Default")
      (node (ref "ADDER_UPPER") (pin "3") (pinfunction "A2_3") (pintype "input"))
      (node (ref "ADDR_REG_A_UPPER") (pin "5") (pinfunction "Q3_5") (pintype "tri_state"))
      (node (ref "AND_GATE2_") (pin "4") (pinfunction "I0_4") (pintype "input"))
      (node (ref "LED_A_REG_6") (pin "A") (pinfunction "A_A") (pintype "passive"))
      (node (ref "NOT_GATE5_") (pin "13") (pinfunction "I_13") (pintype "input"))
      (node (ref "OR_GATE1_") (pin "10") (pinfunction "I1_10") (pintype "input"))
      (node (ref "OUTPUT_BUFFER_REG_A") (pin "4") (pinfunction "A3_4") (pintype "bidirectional"))
      (node (ref "XOR_LOGIC_UPPER") (pin "5") (pinfunction "I1_5") (pintype "input"))
      (node (ref "ZERO_POS_FLAG_IDENTIFIER") (pin "10") (pinfunction "F_10") (pintype "input"))
    )
    (net (code "23") (name "Net-(ADDER_UPPERA-A3)") (class "Default")
      (node (ref "ADDER_UPPER") (pin "14") (pinfunction "A3_14") (pintype "input"))
      (node (ref "ADDR_REG_A_UPPER") (pin "4") (pinfunction "Q2_4") (pintype "tri_state"))
      (node (ref "AND_GATE2_") (pin "10") (pinfunction "I1_10") (pintype "input"))
      (node (ref "LED_A_REG_7") (pin "A") (pinfunction "A_A") (pintype "passive"))
      (node (ref "NOT_GATE3_") (pin "5") (pinfunction "I_5") (pintype "input"))
      (node (ref "OR_GATE1_") (pin "4") (pinfunction "I0_4") (pintype "input"))
      (node (ref "OUTPUT_BUFFER_REG_A") (pin "3") (pinfunction "A2_3") (pintype "bidirectional"))
      (node (ref "XOR_LOGIC_UPPER") (pin "10") (pinfunction "I1_10") (pintype "input"))
      (node (ref "ZERO_POS_FLAG_IDENTIFIER") (pin "11") (pinfunction "G_11") (pintype "input"))
    )
    (net (code "24") (name "Net-(ADDER_UPPERA-A4)") (class "Default")
      (node (ref "ADDER_UPPER") (pin "12") (pinfunction "A4_12") (pintype "input"))
      (node (ref "ADDR_REG_A_UPPER") (pin "3") (pinfunction "Q1_3") (pintype "tri_state"))
      (node (ref "AND_GATE2_") (pin "12") (pinfunction "I0_12") (pintype "input"))
      (node (ref "LED_A_REG_8") (pin "A") (pinfunction "A_A") (pintype "passive"))
      (node (ref "NOT_GATE3_") (pin "9") (pinfunction "I_9") (pintype "input"))
      (node (ref "OR_GATE1_") (pin "2") (pinfunction "I1_2") (pintype "input"))
      (node (ref "OUTPUT_BUFFER_REG_A") (pin "2") (pinfunction "A1_2") (pintype "bidirectional"))
      (node (ref "XOR_LOGIC_UPPER") (pin "13") (pinfunction "I1_13") (pintype "input"))
      (node (ref "ZERO_POS_FLAG_IDENTIFIER") (pin "12") (pinfunction "H_12") (pintype "input"))
    )
    (net (code "25") (name "Net-(ADDER_UPPERA-B1)") (class "Default")
      (node (ref "ADDER_UPPER") (pin "6") (pinfunction "B1_6") (pintype "input"))
      (node (ref "SUBTRACT_INVRTR_UPPER_") (pin "11") (pinfunction "O_11") (pintype "output"))
    )
    (net (code "26") (name "Net-(ADDER_UPPERA-B2)") (class "Default")
      (node (ref "ADDER_UPPER") (pin "2") (pinfunction "B2_2") (pintype "input"))
      (node (ref "SUBTRACT_INVRTR_UPPER_") (pin "8") (pinfunction "O_8") (pintype "output"))
    )
    (net (code "27") (name "Net-(ADDER_UPPERA-B3)") (class "Default")
      (node (ref "ADDER_UPPER") (pin "15") (pinfunction "B3_15") (pintype "input"))
      (node (ref "SUBTRACT_INVRTR_UPPER_") (pin "6") (pinfunction "O_6") (pintype "output"))
    )
    (net (code "28") (name "Net-(ADDER_UPPERA-B4)") (class "Default")
      (node (ref "ADDER_UPPER") (pin "11") (pinfunction "B4_11") (pintype "input"))
      (node (ref "SUBTRACT_INVRTR_UPPER_") (pin "3") (pinfunction "O_3") (pintype "output"))
    )
    (net (code "29") (name "Net-(ADDER_UPPERA-C4)") (class "Default")
      (node (ref "ADDER_UPPER") (pin "9") (pinfunction "C4_9") (pintype "output"))
      (node (ref "AND_GATE3_") (pin "13") (pinfunction "I1_13") (pintype "input"))
      (node (ref "FLAG_REG_LOWER") (pin "14") (pinfunction "D1_14") (pintype "input"))
      (node (ref "OVERFLOW_FLAG") (pin "A") (pinfunction "A_A") (pintype "passive"))
    )
    (net (code "30") (name "Net-(ADDER_UPPERA-S1)") (class "Default")
      (node (ref "ADDER_UPPER") (pin "4") (pinfunction "S1_4") (pintype "output"))
      (node (ref "OUTPUT_BUFFER_ALU") (pin "14") (pinfunction "B5_14") (pintype "bidirectional"))
    )
    (net (code "31") (name "Net-(ADDER_UPPERA-S2)") (class "Default")
      (node (ref "ADDER_UPPER") (pin "1") (pinfunction "S2_1") (pintype "output"))
      (node (ref "OUTPUT_BUFFER_ALU") (pin "13") (pinfunction "B6_13") (pintype "bidirectional"))
    )
    (net (code "32") (name "Net-(ADDER_UPPERA-S3)") (class "Default")
      (node (ref "ADDER_UPPER") (pin "13") (pinfunction "S3_13") (pintype "output"))
      (node (ref "OUTPUT_BUFFER_ALU") (pin "12") (pinfunction "B7_12") (pintype "bidirectional"))
    )
    (net (code "33") (name "Net-(ADDER_UPPERA-S4)") (class "Default")
      (node (ref "ADDER_UPPER") (pin "10") (pinfunction "S4_10") (pintype "output"))
      (node (ref "OUTPUT_BUFFER_ALU") (pin "11") (pinfunction "B8_11") (pintype "bidirectional"))
    )
    (net (code "34") (name "Net-(ADDR_MEM_REG_LOWERA-CLK)") (class "Default")
      (node (ref "ADDR_MEM_REG_LOWER") (pin "7") (pinfunction "CLK_7") (pintype "input"))
      (node (ref "ADDR_MEM_REG_UPPER") (pin "7") (pinfunction "CLK_7") (pintype "input"))
      (node (ref "ADDR_REG_A_LOWER") (pin "7") (pinfunction "CLK_7") (pintype "input"))
      (node (ref "ADDR_REG_A_UPPER") (pin "7") (pinfunction "CLK_7") (pintype "input"))
      (node (ref "ADDR_REG_CALC_LOWER") (pin "7") (pinfunction "CLK_7") (pintype "input"))
      (node (ref "ADDR_REG_CALC_UPPER") (pin "7") (pinfunction "CLK_7") (pintype "input"))
      (node (ref "ADDR_REG_PARAM_LOWER") (pin "7") (pinfunction "CLK_7") (pintype "input"))
      (node (ref "ADDR_REG_PARAM_UPPER") (pin "7") (pinfunction "CLK_7") (pintype "input"))
      (node (ref "AND_GATE_") (pin "8") (pinfunction "O_8") (pintype "output"))
      (node (ref "CLOCK") (pin "A") (pinfunction "A_A") (pintype "passive"))
      (node (ref "EXTENSION") (pin "9") (pinfunction "1_9") (pintype "passive"))
      (node (ref "FLAG_REG_LOWER") (pin "7") (pinfunction "CLK_7") (pintype "input"))
      (node (ref "FLAG_REG_UPPER") (pin "7") (pinfunction "CLK_7") (pintype "input"))
      (node (ref "INSTRUC_REGISTER_LOWER") (pin "7") (pinfunction "CLK_7") (pintype "input"))
      (node (ref "INSTRUC_REGISTER_UPPER") (pin "7") (pinfunction "CLK_7") (pintype "input"))
      (node (ref "NOT_GATE1") (pin "11") (pinfunction "I_11") (pintype "input"))
      (node (ref "PROGRAM_COUNTER_LOWER") (pin "2") (pinfunction "2_2") (pintype "passive"))
      (node (ref "PROGRAM_COUNTER_UPPER") (pin "2") (pinfunction "2_2") (pintype "passive"))
      (node (ref "RAM_ADDR_LOWER") (pin "7") (pinfunction "CLK_7") (pintype "input"))
      (node (ref "RAM_ADDR_UPPER") (pin "7") (pinfunction "CLK_7") (pintype "input"))
    )
    (net (code "35") (name "Net-(ADDR_MEM_REG_LOWERA-CLR)") (class "Default")
      (node (ref "ADDR_MEM_REG_LOWER") (pin "15") (pinfunction "CLR_15") (pintype "input"))
      (node (ref "ADDR_MEM_REG_UPPER") (pin "15") (pinfunction "CLR_15") (pintype "input"))
      (node (ref "ADDR_REG_A_LOWER") (pin "15") (pinfunction "CLR_15") (pintype "input"))
      (node (ref "ADDR_REG_A_UPPER") (pin "15") (pinfunction "CLR_15") (pintype "input"))
      (node (ref "ADDR_REG_CALC_LOWER") (pin "15") (pinfunction "CLR_15") (pintype "input"))
      (node (ref "ADDR_REG_CALC_UPPER") (pin "15") (pinfunction "CLR_15") (pintype "input"))
      (node (ref "ADDR_REG_PARAM_LOWER") (pin "15") (pinfunction "CLR_15") (pintype "input"))
      (node (ref "ADDR_REG_PARAM_UPPER") (pin "15") (pinfunction "CLR_15") (pintype "input"))
      (node (ref "FLAG_REG_LOWER") (pin "15") (pinfunction "CLR_15") (pintype "input"))
      (node (ref "FLAG_REG_UPPER") (pin "15") (pinfunction "CLR_15") (pintype "input"))
      (node (ref "INSTRUC_REGISTER_LOWER") (pin "15") (pinfunction "CLR_15") (pintype "input"))
      (node (ref "INSTRUC_REGISTER_UPPER") (pin "15") (pinfunction "CLR_15") (pintype "input"))
      (node (ref "R81") (pin "1") (pinfunction "1_1") (pintype "passive"))
      (node (ref "RAM_ADDR_LOWER") (pin "15") (pinfunction "CLR_15") (pintype "input"))
      (node (ref "RAM_ADDR_UPPER") (pin "15") (pinfunction "CLR_15") (pintype "input"))
      (node (ref "RESET_REGS") (pin "4") (pinfunction "P1_4") (pintype "passive"))
    )
    (net (code "36") (name "Net-(ADDR_MEM_REG_LOWERA-D1)") (class "Default")
      (node (ref "ADDR_MEM_REG_LOWER") (pin "14") (pinfunction "D1_14") (pintype "input"))
      (node (ref "ADDR_REG_A_LOWER") (pin "14") (pinfunction "D1_14") (pintype "input"))
      (node (ref "ADDR_REG_CALC_LOWER") (pin "14") (pinfunction "D1_14") (pintype "input"))
      (node (ref "ADDR_REG_PARAM_LOWER") (pin "14") (pinfunction "D1_14") (pintype "input"))
      (node (ref "DATABUS_4") (pin "A") (pinfunction "A_A") (pintype "passive"))
      (node (ref "EXTENSION") (pin "4") (pinfunction "1_4") (pintype "passive"))
      (node (ref "INSTRUC_REGISTER_LOWER") (pin "14") (pinfunction "D1_14") (pintype "input"))
      (node (ref "MICRO_COUNTER_LOWER") (pin "6") (pinfunction "6_6") (pintype "passive"))
      (node (ref "OUTPUT_BUFFER_ALU") (pin "5") (pinfunction "A4_5") (pintype "bidirectional"))
      (node (ref "OUTPUT_BUFFER_CALC_REG") (pin "14") (pinfunction "B5_14") (pintype "bidirectional"))
      (node (ref "OUTPUT_BUFFER_FLAGS") (pin "5") (pinfunction "A4_5") (pintype "bidirectional"))
      (node (ref "OUTPUT_BUFFER_INSTRUCTION") (pin "14") (pinfunction "B5_14") (pintype "bidirectional"))
      (node (ref "OUTPUT_BUFFER_LOGIC") (pin "15") (pinfunction "B4_15") (pintype "bidirectional"))
      (node (ref "OUTPUT_BUFFER_MEMORY") (pin "14") (pinfunction "B5_14") (pintype "bidirectional"))
      (node (ref "OUTPUT_BUFFER_PARAM_REG") (pin "14") (pinfunction "B5_14") (pintype "bidirectional"))
      (node (ref "OUTPUT_BUFFER_PC") (pin "14") (pinfunction "B5_14") (pintype "bidirectional"))
      (node (ref "OUTPUT_BUFFER_RAM") (pin "15") (pinfunction "B4_15") (pintype "bidirectional"))
      (node (ref "OUTPUT_BUFFER_REG_A") (pin "14") (pinfunction "B5_14") (pintype "bidirectional"))
      (node (ref "PROGRAM_COUNTER_LOWER") (pin "6") (pinfunction "6_6") (pintype "passive"))
      (node (ref "RAM_ADDR_LOWER") (pin "11") (pinfunction "D4_11") (pintype "input"))
      (node (ref "XOR_GATE_1") (pin "13") (pinfunction "I1_13") (pintype "input"))
    )
    (net (code "37") (name "Net-(ADDR_MEM_REG_LOWERA-D2)") (class "Default")
      (node (ref "ADDR_MEM_REG_LOWER") (pin "13") (pinfunction "D2_13") (pintype "input"))
      (node (ref "ADDR_REG_A_LOWER") (pin "13") (pinfunction "D2_13") (pintype "input"))
      (node (ref "ADDR_REG_CALC_LOWER") (pin "13") (pinfunction "D2_13") (pintype "input"))
      (node (ref "ADDR_REG_PARAM_LOWER") (pin "13") (pinfunction "D2_13") (pintype "input"))
      (node (ref "DATABUS_3") (pin "A") (pinfunction "A_A") (pintype "passive"))
      (node (ref "EXTENSION") (pin "3") (pinfunction "1_3") (pintype "passive"))
      (node (ref "INSTRUC_REGISTER_LOWER") (pin "13") (pinfunction "D2_13") (pintype "input"))
      (node (ref "MICRO_COUNTER_LOWER") (pin "5") (pinfunction "5_5") (pintype "passive"))
      (node (ref "OUTPUT_BUFFER_ALU") (pin "4") (pinfunction "A3_4") (pintype "bidirectional"))
      (node (ref "OUTPUT_BUFFER_CALC_REG") (pin "13") (pinfunction "B6_13") (pintype "bidirectional"))
      (node (ref "OUTPUT_BUFFER_FLAGS") (pin "4") (pinfunction "A3_4") (pintype "bidirectional"))
      (node (ref "OUTPUT_BUFFER_INSTRUCTION") (pin "13") (pinfunction "B6_13") (pintype "bidirectional"))
      (node (ref "OUTPUT_BUFFER_LOGIC") (pin "16") (pinfunction "B3_16") (pintype "bidirectional"))
      (node (ref "OUTPUT_BUFFER_MEMORY") (pin "13") (pinfunction "B6_13") (pintype "bidirectional"))
      (node (ref "OUTPUT_BUFFER_PARAM_REG") (pin "13") (pinfunction "B6_13") (pintype "bidirectional"))
      (node (ref "OUTPUT_BUFFER_PC") (pin "13") (pinfunction "B6_13") (pintype "bidirectional"))
      (node (ref "OUTPUT_BUFFER_RAM") (pin "16") (pinfunction "B3_16") (pintype "bidirectional"))
      (node (ref "OUTPUT_BUFFER_REG_A") (pin "13") (pinfunction "B6_13") (pintype "bidirectional"))
      (node (ref "PROGRAM_COUNTER_LOWER") (pin "5") (pinfunction "5_5") (pintype "passive"))
      (node (ref "RAM_ADDR_LOWER") (pin "12") (pinfunction "D3_12") (pintype "input"))
      (node (ref "XOR_GATE_1") (pin "10") (pinfunction "I1_10") (pintype "input"))
    )
    (net (code "38") (name "Net-(ADDR_MEM_REG_LOWERA-D3)") (class "Default")
      (node (ref "ADDR_MEM_REG_LOWER") (pin "12") (pinfunction "D3_12") (pintype "input"))
      (node (ref "ADDR_REG_A_LOWER") (pin "12") (pinfunction "D3_12") (pintype "input"))
      (node (ref "ADDR_REG_CALC_LOWER") (pin "12") (pinfunction "D3_12") (pintype "input"))
      (node (ref "ADDR_REG_PARAM_LOWER") (pin "12") (pinfunction "D3_12") (pintype "input"))
      (node (ref "DATABUS_2") (pin "A") (pinfunction "A_A") (pintype "passive"))
      (node (ref "EXTENSION") (pin "2") (pinfunction "1_2") (pintype "passive"))
      (node (ref "INSTRUC_REGISTER_LOWER") (pin "12") (pinfunction "D3_12") (pintype "input"))
      (node (ref "MICRO_COUNTER_LOWER") (pin "4") (pinfunction "4_4") (pintype "passive"))
      (node (ref "OUTPUT_BUFFER_ALU") (pin "3") (pinfunction "A2_3") (pintype "bidirectional"))
      (node (ref "OUTPUT_BUFFER_CALC_REG") (pin "12") (pinfunction "B7_12") (pintype "bidirectional"))
      (node (ref "OUTPUT_BUFFER_FLAGS") (pin "3") (pinfunction "A2_3") (pintype "bidirectional"))
      (node (ref "OUTPUT_BUFFER_INSTRUCTION") (pin "12") (pinfunction "B7_12") (pintype "bidirectional"))
      (node (ref "OUTPUT_BUFFER_LOGIC") (pin "17") (pinfunction "B2_17") (pintype "bidirectional"))
      (node (ref "OUTPUT_BUFFER_MEMORY") (pin "12") (pinfunction "B7_12") (pintype "bidirectional"))
      (node (ref "OUTPUT_BUFFER_PARAM_REG") (pin "12") (pinfunction "B7_12") (pintype "bidirectional"))
      (node (ref "OUTPUT_BUFFER_PC") (pin "12") (pinfunction "B7_12") (pintype "bidirectional"))
      (node (ref "OUTPUT_BUFFER_RAM") (pin "17") (pinfunction "B2_17") (pintype "bidirectional"))
      (node (ref "OUTPUT_BUFFER_REG_A") (pin "12") (pinfunction "B7_12") (pintype "bidirectional"))
      (node (ref "PROGRAM_COUNTER_LOWER") (pin "4") (pinfunction "4_4") (pintype "passive"))
      (node (ref "RAM_ADDR_LOWER") (pin "13") (pinfunction "D2_13") (pintype "input"))
      (node (ref "XOR_GATE_1") (pin "5") (pinfunction "I1_5") (pintype "input"))
    )
    (net (code "39") (name "Net-(ADDR_MEM_REG_LOWERA-D4)") (class "Default")
      (node (ref "ADDR_MEM_REG_LOWER") (pin "11") (pinfunction "D4_11") (pintype "input"))
      (node (ref "ADDR_REG_A_LOWER") (pin "11") (pinfunction "D4_11") (pintype "input"))
      (node (ref "ADDR_REG_CALC_LOWER") (pin "11") (pinfunction "D4_11") (pintype "input"))
      (node (ref "ADDR_REG_PARAM_LOWER") (pin "11") (pinfunction "D4_11") (pintype "input"))
      (node (ref "DATABUS_1") (pin "A") (pinfunction "A_A") (pintype "passive"))
      (node (ref "EXTENSION") (pin "1") (pinfunction "1_1") (pintype "passive"))
      (node (ref "INSTRUC_REGISTER_LOWER") (pin "11") (pinfunction "D4_11") (pintype "input"))
      (node (ref "MICRO_COUNTER_LOWER") (pin "3") (pinfunction "3_3") (pintype "passive"))
      (node (ref "OUTPUT_BUFFER_ALU") (pin "2") (pinfunction "A1_2") (pintype "bidirectional"))
      (node (ref "OUTPUT_BUFFER_CALC_REG") (pin "11") (pinfunction "B8_11") (pintype "bidirectional"))
      (node (ref "OUTPUT_BUFFER_FLAGS") (pin "2") (pinfunction "A1_2") (pintype "bidirectional"))
      (node (ref "OUTPUT_BUFFER_INSTRUCTION") (pin "11") (pinfunction "B8_11") (pintype "bidirectional"))
      (node (ref "OUTPUT_BUFFER_LOGIC") (pin "18") (pinfunction "B1_18") (pintype "bidirectional"))
      (node (ref "OUTPUT_BUFFER_MEMORY") (pin "11") (pinfunction "B8_11") (pintype "bidirectional"))
      (node (ref "OUTPUT_BUFFER_PARAM_REG") (pin "11") (pinfunction "B8_11") (pintype "bidirectional"))
      (node (ref "OUTPUT_BUFFER_PC") (pin "11") (pinfunction "B8_11") (pintype "bidirectional"))
      (node (ref "OUTPUT_BUFFER_RAM") (pin "18") (pinfunction "B1_18") (pintype "bidirectional"))
      (node (ref "OUTPUT_BUFFER_REG_A") (pin "11") (pinfunction "B8_11") (pintype "bidirectional"))
      (node (ref "PROGRAM_COUNTER_LOWER") (pin "3") (pinfunction "3_3") (pintype "passive"))
      (node (ref "RAM_ADDR_LOWER") (pin "14") (pinfunction "D1_14") (pintype "input"))
      (node (ref "XOR_GATE_1") (pin "2") (pinfunction "I1_2") (pintype "input"))
    )
    (net (code "40") (name "Net-(ADDR_MEM_REG_LOWERA-G1)") (class "Default")
      (node (ref "ADDR_MEM_REG_LOWER") (pin "10") (pinfunction "G2_10") (pintype "input"))
      (node (ref "ADDR_MEM_REG_LOWER") (pin "9") (pinfunction "G1_9") (pintype "input"))
      (node (ref "ADDR_MEM_REG_UPPER") (pin "10") (pinfunction "G2_10") (pintype "input"))
      (node (ref "ADDR_MEM_REG_UPPER") (pin "9") (pinfunction "G1_9") (pintype "input"))
      (node (ref "NOT_GATE1") (pin "6") (pinfunction "O_6") (pintype "output"))
    )
    (net (code "41") (name "Net-(ADDR_MEM_REG_LOWERA-Q1)") (class "Default")
      (node (ref "ADDR_MEM_REG_LOWER") (pin "3") (pinfunction "Q1_3") (pintype "tri_state"))
      (node (ref "MEMORY") (pin "7") (pinfunction "7_7") (pintype "passive"))
    )
    (net (code "42") (name "Net-(ADDR_MEM_REG_LOWERA-Q2)") (class "Default")
      (node (ref "ADDR_MEM_REG_LOWER") (pin "4") (pinfunction "Q2_4") (pintype "tri_state"))
      (node (ref "MEMORY") (pin "8") (pinfunction "8_8") (pintype "passive"))
    )
    (net (code "43") (name "Net-(ADDR_MEM_REG_LOWERA-Q3)") (class "Default")
      (node (ref "ADDR_MEM_REG_LOWER") (pin "5") (pinfunction "Q3_5") (pintype "tri_state"))
      (node (ref "MEMORY") (pin "9") (pinfunction "9_9") (pintype "passive"))
    )
    (net (code "44") (name "Net-(ADDR_MEM_REG_LOWERA-Q4)") (class "Default")
      (node (ref "ADDR_MEM_REG_LOWER") (pin "6") (pinfunction "Q4_6") (pintype "tri_state"))
      (node (ref "MEMORY") (pin "10") (pinfunction "10_10") (pintype "passive"))
    )
    (net (code "45") (name "Net-(ADDR_MEM_REG_UPPERA-D1)") (class "Default")
      (node (ref "ADDR_MEM_REG_UPPER") (pin "14") (pinfunction "D1_14") (pintype "input"))
      (node (ref "ADDR_REG_A_UPPER") (pin "14") (pinfunction "D1_14") (pintype "input"))
      (node (ref "ADDR_REG_CALC_UPPER") (pin "14") (pinfunction "D1_14") (pintype "input"))
      (node (ref "ADDR_REG_PARAM_UPPER") (pin "14") (pinfunction "D1_14") (pintype "input"))
      (node (ref "DATABUS_8") (pin "A") (pinfunction "A_A") (pintype "passive"))
      (node (ref "EXTENSION") (pin "8") (pinfunction "1_8") (pintype "passive"))
      (node (ref "INSTRUC_REGISTER_UPPER") (pin "14") (pinfunction "D1_14") (pintype "input"))
      (node (ref "OUTPUT_BUFFER_ALU") (pin "9") (pinfunction "A8_9") (pintype "bidirectional"))
      (node (ref "OUTPUT_BUFFER_CALC_REG") (pin "18") (pinfunction "B1_18") (pintype "bidirectional"))
      (node (ref "OUTPUT_BUFFER_FLAGS") (pin "9") (pinfunction "A8_9") (pintype "bidirectional"))
      (node (ref "OUTPUT_BUFFER_INSTRUCTION") (pin "18") (pinfunction "B1_18") (pintype "bidirectional"))
      (node (ref "OUTPUT_BUFFER_LOGIC") (pin "11") (pinfunction "B8_11") (pintype "bidirectional"))
      (node (ref "OUTPUT_BUFFER_MEMORY") (pin "18") (pinfunction "B1_18") (pintype "bidirectional"))
      (node (ref "OUTPUT_BUFFER_PARAM_REG") (pin "18") (pinfunction "B1_18") (pintype "bidirectional"))
      (node (ref "OUTPUT_BUFFER_PC") (pin "18") (pinfunction "B1_18") (pintype "bidirectional"))
      (node (ref "OUTPUT_BUFFER_RAM") (pin "11") (pinfunction "B8_11") (pintype "bidirectional"))
      (node (ref "OUTPUT_BUFFER_REG_A") (pin "18") (pinfunction "B1_18") (pintype "bidirectional"))
      (node (ref "PROGRAM_COUNTER_UPPER") (pin "6") (pinfunction "6_6") (pintype "passive"))
      (node (ref "RAM_ADDR_UPPER") (pin "11") (pinfunction "D4_11") (pintype "input"))
    )
    (net (code "46") (name "Net-(ADDR_MEM_REG_UPPERA-D2)") (class "Default")
      (node (ref "ADDR_MEM_REG_UPPER") (pin "13") (pinfunction "D2_13") (pintype "input"))
      (node (ref "ADDR_REG_A_UPPER") (pin "13") (pinfunction "D2_13") (pintype "input"))
      (node (ref "ADDR_REG_CALC_UPPER") (pin "13") (pinfunction "D2_13") (pintype "input"))
      (node (ref "ADDR_REG_PARAM_UPPER") (pin "13") (pinfunction "D2_13") (pintype "input"))
      (node (ref "DATABUS_7") (pin "A") (pinfunction "A_A") (pintype "passive"))
      (node (ref "EXTENSION") (pin "7") (pinfunction "1_7") (pintype "passive"))
      (node (ref "INSTRUC_REGISTER_UPPER") (pin "13") (pinfunction "D2_13") (pintype "input"))
      (node (ref "OUTPUT_BUFFER_ALU") (pin "8") (pinfunction "A7_8") (pintype "bidirectional"))
      (node (ref "OUTPUT_BUFFER_CALC_REG") (pin "17") (pinfunction "B2_17") (pintype "bidirectional"))
      (node (ref "OUTPUT_BUFFER_FLAGS") (pin "8") (pinfunction "A7_8") (pintype "bidirectional"))
      (node (ref "OUTPUT_BUFFER_INSTRUCTION") (pin "17") (pinfunction "B2_17") (pintype "bidirectional"))
      (node (ref "OUTPUT_BUFFER_LOGIC") (pin "12") (pinfunction "B7_12") (pintype "bidirectional"))
      (node (ref "OUTPUT_BUFFER_MEMORY") (pin "17") (pinfunction "B2_17") (pintype "bidirectional"))
      (node (ref "OUTPUT_BUFFER_PARAM_REG") (pin "17") (pinfunction "B2_17") (pintype "bidirectional"))
      (node (ref "OUTPUT_BUFFER_PC") (pin "17") (pinfunction "B2_17") (pintype "bidirectional"))
      (node (ref "OUTPUT_BUFFER_RAM") (pin "12") (pinfunction "B7_12") (pintype "bidirectional"))
      (node (ref "OUTPUT_BUFFER_REG_A") (pin "17") (pinfunction "B2_17") (pintype "bidirectional"))
      (node (ref "PROGRAM_COUNTER_UPPER") (pin "5") (pinfunction "5_5") (pintype "passive"))
      (node (ref "RAM_ADDR_UPPER") (pin "12") (pinfunction "D3_12") (pintype "input"))
      (node (ref "XOR_GATE_2") (pin "10") (pinfunction "I1_10") (pintype "input"))
    )
    (net (code "47") (name "Net-(ADDR_MEM_REG_UPPERA-D3)") (class "Default")
      (node (ref "ADDR_MEM_REG_UPPER") (pin "12") (pinfunction "D3_12") (pintype "input"))
      (node (ref "ADDR_REG_A_UPPER") (pin "12") (pinfunction "D3_12") (pintype "input"))
      (node (ref "ADDR_REG_CALC_UPPER") (pin "12") (pinfunction "D3_12") (pintype "input"))
      (node (ref "ADDR_REG_PARAM_UPPER") (pin "12") (pinfunction "D3_12") (pintype "input"))
      (node (ref "DATABUS_6") (pin "A") (pinfunction "A_A") (pintype "passive"))
      (node (ref "EXTENSION") (pin "6") (pinfunction "1_6") (pintype "passive"))
      (node (ref "INSTRUC_REGISTER_UPPER") (pin "12") (pinfunction "D3_12") (pintype "input"))
      (node (ref "OUTPUT_BUFFER_ALU") (pin "7") (pinfunction "A6_7") (pintype "bidirectional"))
      (node (ref "OUTPUT_BUFFER_CALC_REG") (pin "16") (pinfunction "B3_16") (pintype "bidirectional"))
      (node (ref "OUTPUT_BUFFER_FLAGS") (pin "7") (pinfunction "A6_7") (pintype "bidirectional"))
      (node (ref "OUTPUT_BUFFER_INSTRUCTION") (pin "16") (pinfunction "B3_16") (pintype "bidirectional"))
      (node (ref "OUTPUT_BUFFER_LOGIC") (pin "13") (pinfunction "B6_13") (pintype "bidirectional"))
      (node (ref "OUTPUT_BUFFER_MEMORY") (pin "16") (pinfunction "B3_16") (pintype "bidirectional"))
      (node (ref "OUTPUT_BUFFER_PARAM_REG") (pin "16") (pinfunction "B3_16") (pintype "bidirectional"))
      (node (ref "OUTPUT_BUFFER_PC") (pin "16") (pinfunction "B3_16") (pintype "bidirectional"))
      (node (ref "OUTPUT_BUFFER_RAM") (pin "13") (pinfunction "B6_13") (pintype "bidirectional"))
      (node (ref "OUTPUT_BUFFER_REG_A") (pin "16") (pinfunction "B3_16") (pintype "bidirectional"))
      (node (ref "PROGRAM_COUNTER_UPPER") (pin "4") (pinfunction "4_4") (pintype "passive"))
      (node (ref "RAM_ADDR_UPPER") (pin "13") (pinfunction "D2_13") (pintype "input"))
      (node (ref "XOR_GATE_2") (pin "5") (pinfunction "I1_5") (pintype "input"))
    )
    (net (code "48") (name "Net-(ADDR_MEM_REG_UPPERA-D4)") (class "Default")
      (node (ref "ADDR_MEM_REG_UPPER") (pin "11") (pinfunction "D4_11") (pintype "input"))
      (node (ref "ADDR_REG_A_UPPER") (pin "11") (pinfunction "D4_11") (pintype "input"))
      (node (ref "ADDR_REG_CALC_UPPER") (pin "11") (pinfunction "D4_11") (pintype "input"))
      (node (ref "ADDR_REG_PARAM_UPPER") (pin "11") (pinfunction "D4_11") (pintype "input"))
      (node (ref "DATABUS_5") (pin "A") (pinfunction "A_A") (pintype "passive"))
      (node (ref "EXTENSION") (pin "5") (pinfunction "1_5") (pintype "passive"))
      (node (ref "INSTRUC_REGISTER_UPPER") (pin "11") (pinfunction "D4_11") (pintype "input"))
      (node (ref "MICRO_COUNTER_UPPER") (pin "3") (pinfunction "3_3") (pintype "passive"))
      (node (ref "OUTPUT_BUFFER_ALU") (pin "6") (pinfunction "A5_6") (pintype "bidirectional"))
      (node (ref "OUTPUT_BUFFER_CALC_REG") (pin "15") (pinfunction "B4_15") (pintype "bidirectional"))
      (node (ref "OUTPUT_BUFFER_FLAGS") (pin "6") (pinfunction "A5_6") (pintype "bidirectional"))
      (node (ref "OUTPUT_BUFFER_INSTRUCTION") (pin "15") (pinfunction "B4_15") (pintype "bidirectional"))
      (node (ref "OUTPUT_BUFFER_LOGIC") (pin "14") (pinfunction "B5_14") (pintype "bidirectional"))
      (node (ref "OUTPUT_BUFFER_MEMORY") (pin "15") (pinfunction "B4_15") (pintype "bidirectional"))
      (node (ref "OUTPUT_BUFFER_PARAM_REG") (pin "15") (pinfunction "B4_15") (pintype "bidirectional"))
      (node (ref "OUTPUT_BUFFER_PC") (pin "15") (pinfunction "B4_15") (pintype "bidirectional"))
      (node (ref "OUTPUT_BUFFER_RAM") (pin "14") (pinfunction "B5_14") (pintype "bidirectional"))
      (node (ref "OUTPUT_BUFFER_REG_A") (pin "15") (pinfunction "B4_15") (pintype "bidirectional"))
      (node (ref "PROGRAM_COUNTER_UPPER") (pin "3") (pinfunction "3_3") (pintype "passive"))
      (node (ref "RAM_ADDR_UPPER") (pin "14") (pinfunction "D1_14") (pintype "input"))
      (node (ref "XOR_GATE_2") (pin "2") (pinfunction "I1_2") (pintype "input"))
    )
    (net (code "49") (name "Net-(ADDR_MEM_REG_UPPERA-Q1)") (class "Default")
      (node (ref "ADDR_MEM_REG_UPPER") (pin "3") (pinfunction "Q1_3") (pintype "tri_state"))
      (node (ref "MEMORY") (pin "3") (pinfunction "3_3") (pintype "passive"))
    )
    (net (code "50") (name "Net-(ADDR_MEM_REG_UPPERA-Q2)") (class "Default")
      (node (ref "ADDR_MEM_REG_UPPER") (pin "4") (pinfunction "Q2_4") (pintype "tri_state"))
      (node (ref "MEMORY") (pin "4") (pinfunction "4_4") (pintype "passive"))
    )
    (net (code "51") (name "Net-(ADDR_MEM_REG_UPPERA-Q3)") (class "Default")
      (node (ref "ADDR_MEM_REG_UPPER") (pin "5") (pinfunction "Q3_5") (pintype "tri_state"))
      (node (ref "MEMORY") (pin "5") (pinfunction "5_5") (pintype "passive"))
    )
    (net (code "52") (name "Net-(ADDR_MEM_REG_UPPERA-Q4)") (class "Default")
      (node (ref "ADDR_MEM_REG_UPPER") (pin "6") (pinfunction "Q4_6") (pintype "tri_state"))
      (node (ref "MEMORY") (pin "6") (pinfunction "6_6") (pintype "passive"))
    )
    (net (code "53") (name "Net-(ADDR_REG_A_LOWERA-G1)") (class "Default")
      (node (ref "ADDR_REG_A_LOWER") (pin "10") (pinfunction "G2_10") (pintype "input"))
      (node (ref "ADDR_REG_A_LOWER") (pin "9") (pinfunction "G1_9") (pintype "input"))
      (node (ref "ADDR_REG_A_UPPER") (pin "10") (pinfunction "G2_10") (pintype "input"))
      (node (ref "ADDR_REG_A_UPPER") (pin "9") (pinfunction "G1_9") (pintype "input"))
      (node (ref "BRANCH_SELECTOR") (pin "10") (pinfunction "Y2_10") (pintype "output"))
    )
    (net (code "54") (name "Net-(ADDR_REG_CALC_LOWERA-G1)") (class "Default")
      (node (ref "ADDR_REG_CALC_LOWER") (pin "10") (pinfunction "G2_10") (pintype "input"))
      (node (ref "ADDR_REG_CALC_LOWER") (pin "9") (pinfunction "G1_9") (pintype "input"))
      (node (ref "ADDR_REG_CALC_UPPER") (pin "10") (pinfunction "G2_10") (pintype "input"))
      (node (ref "ADDR_REG_CALC_UPPER") (pin "9") (pinfunction "G1_9") (pintype "input"))
      (node (ref "SELECTOR_LOGIC2_") (pin "10") (pinfunction "Y2_10") (pintype "output"))
    )
    (net (code "55") (name "Net-(ADDR_REG_CALC_LOWERA-Q1)") (class "Default")
      (node (ref "ADDR_REG_CALC_LOWER") (pin "3") (pinfunction "Q1_3") (pintype "tri_state"))
      (node (ref "AND_GATE4_") (pin "13") (pinfunction "I1_13") (pintype "input"))
      (node (ref "LED_B_REG_4") (pin "A") (pinfunction "A_A") (pintype "passive"))
      (node (ref "OR_GATE2_") (pin "1") (pinfunction "I0_1") (pintype "input"))
      (node (ref "OUTPUT_BUFFER_CALC_REG") (pin "6") (pinfunction "A5_6") (pintype "bidirectional"))
      (node (ref "SUBTRACT_INVRTR_LOWER_") (pin "2") (pinfunction "I1_2") (pintype "input"))
      (node (ref "XOR_LOGIC_LOWER") (pin "12") (pinfunction "I0_12") (pintype "input"))
    )
    (net (code "56") (name "Net-(ADDR_REG_CALC_LOWERA-Q2)") (class "Default")
      (node (ref "ADDR_REG_CALC_LOWER") (pin "4") (pinfunction "Q2_4") (pintype "tri_state"))
      (node (ref "AND_GATE1_") (pin "10") (pinfunction "I1_10") (pintype "input"))
      (node (ref "LED_B_REG_3") (pin "A") (pinfunction "A_A") (pintype "passive"))
      (node (ref "OR_GATE2_") (pin "4") (pinfunction "I0_4") (pintype "input"))
      (node (ref "OUTPUT_BUFFER_CALC_REG") (pin "7") (pinfunction "A6_7") (pintype "bidirectional"))
      (node (ref "SUBTRACT_INVRTR_LOWER_") (pin "5") (pinfunction "I1_5") (pintype "input"))
      (node (ref "XOR_LOGIC_LOWER") (pin "9") (pinfunction "I0_9") (pintype "input"))
    )
    (net (code "57") (name "Net-(ADDR_REG_CALC_LOWERA-Q3)") (class "Default")
      (node (ref "ADDR_REG_CALC_LOWER") (pin "5") (pinfunction "Q3_5") (pintype "tri_state"))
      (node (ref "AND_GATE1_") (pin "5") (pinfunction "I1_5") (pintype "input"))
      (node (ref "LED_B_REG_2") (pin "A") (pinfunction "A_A") (pintype "passive"))
      (node (ref "OR_GATE2_") (pin "9") (pinfunction "I0_9") (pintype "input"))
      (node (ref "OUTPUT_BUFFER_CALC_REG") (pin "8") (pinfunction "A7_8") (pintype "bidirectional"))
      (node (ref "SUBTRACT_INVRTR_LOWER_") (pin "10") (pinfunction "I1_10") (pintype "input"))
      (node (ref "XOR_LOGIC_LOWER") (pin "4") (pinfunction "I0_4") (pintype "input"))
    )
    (net (code "58") (name "Net-(ADDR_REG_CALC_LOWERA-Q4)") (class "Default")
      (node (ref "ADDR_REG_CALC_LOWER") (pin "6") (pinfunction "Q4_6") (pintype "tri_state"))
      (node (ref "AND_GATE1_") (pin "2") (pinfunction "I1_2") (pintype "input"))
      (node (ref "LED_B_REG_1") (pin "A") (pinfunction "A_A") (pintype "passive"))
      (node (ref "OR_GATE2_") (pin "13") (pinfunction "I1_13") (pintype "input"))
      (node (ref "OUTPUT_BUFFER_CALC_REG") (pin "9") (pinfunction "A8_9") (pintype "bidirectional"))
      (node (ref "SUBTRACT_INVRTR_LOWER_") (pin "13") (pinfunction "I1_13") (pintype "input"))
      (node (ref "XOR_LOGIC_LOWER") (pin "1") (pinfunction "I0_1") (pintype "input"))
    )
    (net (code "59") (name "Net-(ADDR_REG_CALC_UPPERA-Q1)") (class "Default")
      (node (ref "ADDR_REG_CALC_UPPER") (pin "3") (pinfunction "Q1_3") (pintype "tri_state"))
      (node (ref "AND_GATE2_") (pin "13") (pinfunction "I1_13") (pintype "input"))
      (node (ref "LED_B_REG_8") (pin "A") (pinfunction "A_A") (pintype "passive"))
      (node (ref "OR_GATE1_") (pin "1") (pinfunction "I0_1") (pintype "input"))
      (node (ref "OUTPUT_BUFFER_CALC_REG") (pin "2") (pinfunction "A1_2") (pintype "bidirectional"))
      (node (ref "SUBTRACT_INVRTR_UPPER_") (pin "2") (pinfunction "I1_2") (pintype "input"))
      (node (ref "XOR_LOGIC_UPPER") (pin "12") (pinfunction "I0_12") (pintype "input"))
    )
    (net (code "60") (name "Net-(ADDR_REG_CALC_UPPERA-Q2)") (class "Default")
      (node (ref "ADDR_REG_CALC_UPPER") (pin "4") (pinfunction "Q2_4") (pintype "tri_state"))
      (node (ref "AND_GATE2_") (pin "9") (pinfunction "I0_9") (pintype "input"))
      (node (ref "LED_B_REG_7") (pin "A") (pinfunction "A_A") (pintype "passive"))
      (node (ref "OR_GATE1_") (pin "5") (pinfunction "I1_5") (pintype "input"))
      (node (ref "OUTPUT_BUFFER_CALC_REG") (pin "3") (pinfunction "A2_3") (pintype "bidirectional"))
      (node (ref "SUBTRACT_INVRTR_UPPER_") (pin "5") (pinfunction "I1_5") (pintype "input"))
      (node (ref "XOR_LOGIC_UPPER") (pin "9") (pinfunction "I0_9") (pintype "input"))
    )
    (net (code "61") (name "Net-(ADDR_REG_CALC_UPPERA-Q3)") (class "Default")
      (node (ref "ADDR_REG_CALC_UPPER") (pin "5") (pinfunction "Q3_5") (pintype "tri_state"))
      (node (ref "AND_GATE2_") (pin "5") (pinfunction "I1_5") (pintype "input"))
      (node (ref "LED_B_REG_6") (pin "A") (pinfunction "A_A") (pintype "passive"))
      (node (ref "OR_GATE1_") (pin "9") (pinfunction "I0_9") (pintype "input"))
      (node (ref "OUTPUT_BUFFER_CALC_REG") (pin "4") (pinfunction "A3_4") (pintype "bidirectional"))
      (node (ref "SUBTRACT_INVRTR_UPPER_") (pin "10") (pinfunction "I1_10") (pintype "input"))
      (node (ref "XOR_LOGIC_UPPER") (pin "4") (pinfunction "I0_4") (pintype "input"))
    )
    (net (code "62") (name "Net-(ADDR_REG_CALC_UPPERA-Q4)") (class "Default")
      (node (ref "ADDR_REG_CALC_UPPER") (pin "6") (pinfunction "Q4_6") (pintype "tri_state"))
      (node (ref "AND_GATE2_") (pin "2") (pinfunction "I1_2") (pintype "input"))
      (node (ref "LED_B_REG_5") (pin "A") (pinfunction "A_A") (pintype "passive"))
      (node (ref "OR_GATE1_") (pin "12") (pinfunction "I0_12") (pintype "input"))
      (node (ref "OUTPUT_BUFFER_CALC_REG") (pin "5") (pinfunction "A4_5") (pintype "bidirectional"))
      (node (ref "SUBTRACT_INVRTR_UPPER_") (pin "13") (pinfunction "I1_13") (pintype "input"))
      (node (ref "XOR_LOGIC_UPPER") (pin "1") (pinfunction "I0_1") (pintype "input"))
    )
    (net (code "63") (name "Net-(ADDR_REG_PARAM_LOWERA-G1)") (class "Default")
      (node (ref "ADDR_REG_PARAM_LOWER") (pin "10") (pinfunction "G2_10") (pintype "input"))
      (node (ref "ADDR_REG_PARAM_LOWER") (pin "9") (pinfunction "G1_9") (pintype "input"))
      (node (ref "ADDR_REG_PARAM_UPPER") (pin "10") (pinfunction "G2_10") (pintype "input"))
      (node (ref "ADDR_REG_PARAM_UPPER") (pin "9") (pinfunction "G1_9") (pintype "input"))
      (node (ref "NOT_GATE2_") (pin "4") (pinfunction "O_4") (pintype "output"))
    )
    (net (code "64") (name "Net-(ADDR_REG_PARAM_LOWERA-Q1)") (class "Default")
      (node (ref "ADDR_REG_PARAM_LOWER") (pin "3") (pinfunction "Q1_3") (pintype "tri_state"))
      (node (ref "OUTPUT_BUFFER_PARAM_REG") (pin "6") (pinfunction "A5_6") (pintype "bidirectional"))
      (node (ref "PARAM_LED_4") (pin "A") (pinfunction "A_A") (pintype "passive"))
    )
    (net (code "65") (name "Net-(ADDR_REG_PARAM_LOWERA-Q2)") (class "Default")
      (node (ref "ADDR_REG_PARAM_LOWER") (pin "4") (pinfunction "Q2_4") (pintype "tri_state"))
      (node (ref "OUTPUT_BUFFER_PARAM_REG") (pin "7") (pinfunction "A6_7") (pintype "bidirectional"))
      (node (ref "PARAM_LED_3") (pin "A") (pinfunction "A_A") (pintype "passive"))
    )
    (net (code "66") (name "Net-(ADDR_REG_PARAM_LOWERA-Q3)") (class "Default")
      (node (ref "ADDR_REG_PARAM_LOWER") (pin "5") (pinfunction "Q3_5") (pintype "tri_state"))
      (node (ref "OUTPUT_BUFFER_PARAM_REG") (pin "8") (pinfunction "A7_8") (pintype "bidirectional"))
      (node (ref "PARAM_LED_2") (pin "A") (pinfunction "A_A") (pintype "passive"))
    )
    (net (code "67") (name "Net-(ADDR_REG_PARAM_LOWERA-Q4)") (class "Default")
      (node (ref "ADDR_REG_PARAM_LOWER") (pin "6") (pinfunction "Q4_6") (pintype "tri_state"))
      (node (ref "OUTPUT_BUFFER_PARAM_REG") (pin "9") (pinfunction "A8_9") (pintype "bidirectional"))
      (node (ref "PARAM_LED_1") (pin "A") (pinfunction "A_A") (pintype "passive"))
    )
    (net (code "68") (name "Net-(ADDR_REG_PARAM_UPPERA-Q1)") (class "Default")
      (node (ref "ADDR_REG_PARAM_UPPER") (pin "3") (pinfunction "Q1_3") (pintype "tri_state"))
      (node (ref "OUTPUT_BUFFER_PARAM_REG") (pin "2") (pinfunction "A1_2") (pintype "bidirectional"))
      (node (ref "PARAM_LED_8") (pin "A") (pinfunction "A_A") (pintype "passive"))
    )
    (net (code "69") (name "Net-(ADDR_REG_PARAM_UPPERA-Q2)") (class "Default")
      (node (ref "ADDR_REG_PARAM_UPPER") (pin "4") (pinfunction "Q2_4") (pintype "tri_state"))
      (node (ref "OUTPUT_BUFFER_PARAM_REG") (pin "3") (pinfunction "A2_3") (pintype "bidirectional"))
      (node (ref "PARAM_LED_7") (pin "A") (pinfunction "A_A") (pintype "passive"))
    )
    (net (code "70") (name "Net-(ADDR_REG_PARAM_UPPERA-Q3)") (class "Default")
      (node (ref "ADDR_REG_PARAM_UPPER") (pin "5") (pinfunction "Q3_5") (pintype "tri_state"))
      (node (ref "OUTPUT_BUFFER_PARAM_REG") (pin "4") (pinfunction "A3_4") (pintype "bidirectional"))
      (node (ref "PARAM_LED_6") (pin "A") (pinfunction "A_A") (pintype "passive"))
    )
    (net (code "71") (name "Net-(ADDR_REG_PARAM_UPPERA-Q4)") (class "Default")
      (node (ref "ADDR_REG_PARAM_UPPER") (pin "6") (pinfunction "Q4_6") (pintype "tri_state"))
      (node (ref "OUTPUT_BUFFER_PARAM_REG") (pin "5") (pinfunction "A4_5") (pintype "bidirectional"))
      (node (ref "PARAM_LED_5") (pin "A") (pinfunction "A_A") (pintype "passive"))
    )
    (net (code "72") (name "Net-(AND_GATE1_A-O)") (class "Default")
      (node (ref "AND_GATE1_") (pin "3") (pinfunction "O_3") (pintype "output"))
      (node (ref "LOGIC_SELECTOR-AND/OR_LOWER") (pin "2") (pinfunction "1A_2") (pintype "input"))
    )
    (net (code "73") (name "Net-(AND_GATE1_B-O)") (class "Default")
      (node (ref "AND_GATE1_") (pin "6") (pinfunction "O_6") (pintype "output"))
      (node (ref "LOGIC_SELECTOR-AND/OR_LOWER") (pin "5") (pinfunction "2A_5") (pintype "input"))
    )
    (net (code "74") (name "Net-(AND_GATE1_C-O)") (class "Default")
      (node (ref "AND_GATE1_") (pin "8") (pinfunction "O_8") (pintype "output"))
      (node (ref "LOGIC_SELECTOR-AND/OR_LOWER") (pin "11") (pinfunction "3A_11") (pintype "input"))
    )
    (net (code "75") (name "Net-(AND_GATE2_A-O)") (class "Default")
      (node (ref "AND_GATE2_") (pin "3") (pinfunction "O_3") (pintype "output"))
      (node (ref "LOGIC_SELECTOR-AND/OR_UPPER") (pin "2") (pinfunction "1A_2") (pintype "input"))
    )
    (net (code "76") (name "Net-(AND_GATE2_B-O)") (class "Default")
      (node (ref "AND_GATE2_") (pin "6") (pinfunction "O_6") (pintype "output"))
      (node (ref "LOGIC_SELECTOR-AND/OR_UPPER") (pin "5") (pinfunction "2A_5") (pintype "input"))
    )
    (net (code "77") (name "Net-(AND_GATE2_C-O)") (class "Default")
      (node (ref "AND_GATE2_") (pin "8") (pinfunction "O_8") (pintype "output"))
      (node (ref "LOGIC_SELECTOR-AND/OR_UPPER") (pin "11") (pinfunction "3A_11") (pintype "input"))
    )
    (net (code "78") (name "Net-(AND_GATE2_D-O)") (class "Default")
      (node (ref "AND_GATE2_") (pin "11") (pinfunction "O_11") (pintype "output"))
      (node (ref "LOGIC_SELECTOR-AND/OR_UPPER") (pin "14") (pinfunction "4A_14") (pintype "input"))
    )
    (net (code "79") (name "Net-(AND_GATE3_A-I0)") (class "Default")
      (node (ref "AND_GATE3_") (pin "1") (pinfunction "I0_1") (pintype "input"))
      (node (ref "SELECTOR_LOGIC_") (pin "6") (pinfunction "Y2_6") (pintype "output"))
    )
    (net (code "80") (name "Net-(AND_GATE3_A-I1)") (class "Default")
      (node (ref "AND_GATE3_") (pin "2") (pinfunction "I1_2") (pintype "input"))
      (node (ref "SELECTOR_LOGIC_") (pin "7") (pinfunction "Y3_7") (pintype "output"))
    )
    (net (code "81") (name "Net-(AND_GATE3_A-O)") (class "Default")
      (node (ref "AND_GATE3_") (pin "3") (pinfunction "O_3") (pintype "output"))
      (node (ref "LOGIC_SELECTOR-XOR/NOT_LOWER") (pin "15") (pinfunction "G_15") (pintype "input"))
      (node (ref "LOGIC_SELECTOR-XOR/NOT_UPPER") (pin "15") (pinfunction "G_15") (pintype "input"))
    )
    (net (code "82") (name "Net-(AND_GATE3_B-I1)") (class "Default")
      (node (ref "AND_GATE3_") (pin "5") (pinfunction "I1_5") (pintype "input"))
      (node (ref "NOT_GATE4_") (pin "12") (pinfunction "O_12") (pintype "output"))
    )
    (net (code "83") (name "Net-(AND_GATE3_B-O)") (class "Default")
      (node (ref "AND_GATE3_") (pin "6") (pinfunction "O_6") (pintype "output"))
      (node (ref "NOT_GATE4_") (pin "9") (pinfunction "I_9") (pintype "input"))
    )
    (net (code "84") (name "Net-(AND_GATE3_C-I1)") (class "Default")
      (node (ref "AND_GATE3_") (pin "10") (pinfunction "I1_10") (pintype "input"))
      (node (ref "NOT_GATE_") (pin "10") (pinfunction "O_10") (pintype "output"))
    )
    (net (code "85") (name "Net-(AND_GATE3_C-O)") (class "Default")
      (node (ref "AND_GATE3_") (pin "8") (pinfunction "O_8") (pintype "output"))
      (node (ref "NOT_GATE4_") (pin "5") (pinfunction "I_5") (pintype "input"))
    )
    (net (code "86") (name "Net-(AND_GATE3_D-I0)") (class "Default")
      (node (ref "AND_GATE3_") (pin "12") (pinfunction "I0_12") (pintype "input"))
      (node (ref "NOT_GATE2_") (pin "8") (pinfunction "O_8") (pintype "output"))
    )
    (net (code "87") (name "Net-(AND_GATE4_A-I0)") (class "Default")
      (node (ref "AND_GATE4_") (pin "1") (pinfunction "I0_1") (pintype "input"))
      (node (ref "NOT_GATE2_") (pin "6") (pinfunction "O_6") (pintype "output"))
    )
    (net (code "88") (name "Net-(AND_GATE4_A-I1)") (class "Default")
      (node (ref "AND_GATE4_") (pin "2") (pinfunction "I1_2") (pintype "input"))
      (node (ref "ZERO_FLAG") (pin "A") (pinfunction "A_A") (pintype "passive"))
      (node (ref "ZERO_POS_FLAG_IDENTIFIER") (pin "13") (pinfunction "W_13") (pintype "output"))
    )
    (net (code "89") (name "Net-(AND_GATE4_B-I0)") (class "Default")
      (node (ref "AND_GATE4_") (pin "4") (pinfunction "I0_4") (pintype "input"))
      (node (ref "NOT_GATE1") (pin "2") (pinfunction "O_2") (pintype "output"))
    )
    (net (code "90") (name "Net-(AND_GATE4_B-I1)") (class "Default")
      (node (ref "AND_GATE4_") (pin "5") (pinfunction "I1_5") (pintype "input"))
      (node (ref "POSITIVE_FLAG") (pin "A") (pinfunction "A_A") (pintype "passive"))
      (node (ref "ZERO_POS_FLAG_IDENTIFIER") (pin "1") (pinfunction "Y_1") (pintype "output"))
    )
    (net (code "91") (name "Net-(AND_GATE4_C-I0)") (class "Default")
      (node (ref "AND_GATE4_") (pin "9") (pinfunction "I0_9") (pintype "input"))
      (node (ref "SELECTOR_LOGIC2_") (pin "9") (pinfunction "Y3_9") (pintype "output"))
    )
    (net (code "92") (name "Net-(AND_GATE4_C-I1)") (class "Default")
      (node (ref "AND_GATE4_") (pin "10") (pinfunction "I1_10") (pintype "input"))
      (node (ref "PROGRAM_COUNTER_LOWER") (pin "1") (pinfunction "1_1") (pintype "passive"))
      (node (ref "PROGRAM_COUNTER_UPPER") (pin "1") (pinfunction "1_1") (pintype "passive"))
      (node (ref "R80") (pin "1") (pinfunction "1_1") (pintype "passive"))
      (node (ref "RESET_PC") (pin "1") (pinfunction "S_1") (pintype "passive"))
    )
    (net (code "93") (name "Net-(AND_GATE4_C-O)") (class "Default")
      (node (ref "AND_GATE4_") (pin "8") (pinfunction "O_8") (pintype "output"))
      (node (ref "MICRO_COUNTER_LOWER") (pin "1") (pinfunction "1_1") (pintype "passive"))
      (node (ref "MICRO_COUNTER_UPPER") (pin "1") (pinfunction "1_1") (pintype "passive"))
    )
    (net (code "94") (name "Net-(AND_GATE4_D-O)") (class "Default")
      (node (ref "AND_GATE4_") (pin "11") (pinfunction "O_11") (pintype "output"))
      (node (ref "LOGIC_SELECTOR-AND/OR_LOWER") (pin "14") (pinfunction "4A_14") (pintype "input"))
    )
    (net (code "95") (name "Net-(AND_GATE_A-I0)") (class "Default")
      (node (ref "AND_GATE_") (pin "1") (pinfunction "I0_1") (pintype "input"))
      (node (ref "AUTO_CLOCK") (pin "3") (pinfunction "Q_3") (pintype "output"))
    )
    (net (code "96") (name "Net-(AND_GATE_A-I1)") (class "Default")
      (node (ref "AND_GATE_") (pin "2") (pinfunction "I1_2") (pintype "input"))
      (node (ref "NOT_GATE1") (pin "4") (pinfunction "O_4") (pintype "output"))
    )
    (net (code "97") (name "Net-(AND_GATE_A-O)") (class "Default")
      (node (ref "AND_GATE_") (pin "3") (pinfunction "O_3") (pintype "output"))
      (node (ref "OR_GATE_") (pin "1") (pinfunction "I0_1") (pintype "input"))
    )
    (net (code "98") (name "Net-(AND_GATE_B-I0)") (class "Default")
      (node (ref "AND_GATE_") (pin "4") (pinfunction "I0_4") (pintype "input"))
      (node (ref "CLK_MODE") (pin "1") (pinfunction "1_1") (pintype "passive"))
      (node (ref "NOT_GATE1") (pin "3") (pinfunction "I_3") (pintype "input"))
      (node (ref "R4") (pin "2") (pinfunction "2_2") (pintype "passive"))
    )
    (net (code "99") (name "Net-(AND_GATE_B-I1)") (class "Default")
      (node (ref "AND_GATE_") (pin "5") (pinfunction "I1_5") (pintype "input"))
      (node (ref "STEPPER_CLOCK") (pin "3") (pinfunction "Q_3") (pintype "output"))
    )
    (net (code "100") (name "Net-(AND_GATE_B-O)") (class "Default")
      (node (ref "AND_GATE_") (pin "6") (pinfunction "O_6") (pintype "output"))
      (node (ref "OR_GATE_") (pin "2") (pinfunction "I1_2") (pintype "input"))
    )
    (net (code "101") (name "Net-(AND_GATE_C-I0)") (class "Default")
      (node (ref "AND_GATE_") (pin "9") (pinfunction "I0_9") (pintype "input"))
      (node (ref "SELECTOR_LOGIC2_") (pin "7") (pinfunction "Y3_7") (pintype "output"))
    )
    (net (code "102") (name "Net-(AND_GATE_C-I1)") (class "Default")
      (node (ref "AND_GATE_") (pin "10") (pinfunction "I1_10") (pintype "input"))
      (node (ref "OR_GATE_") (pin "3") (pinfunction "O_3") (pintype "output"))
    )
    (net (code "103") (name "Net-(AND_GATE_D-I0)") (class "Default")
      (node (ref "AND_GATE_") (pin "12") (pinfunction "I0_12") (pintype "input"))
      (node (ref "SELECTOR_LOGIC_") (pin "4") (pinfunction "Y0_4") (pintype "output"))
    )
    (net (code "104") (name "Net-(AND_GATE_D-I1)") (class "Default")
      (node (ref "AND_GATE_") (pin "13") (pinfunction "I1_13") (pintype "input"))
      (node (ref "SELECTOR_LOGIC_") (pin "5") (pinfunction "Y1_5") (pintype "output"))
    )
    (net (code "105") (name "Net-(AND_GATE_D-O)") (class "Default")
      (node (ref "AND_GATE_") (pin "11") (pinfunction "O_11") (pintype "output"))
      (node (ref "LOGIC_SELECTOR-AND/OR_LOWER") (pin "15") (pinfunction "G_15") (pintype "input"))
      (node (ref "LOGIC_SELECTOR-AND/OR_UPPER") (pin "15") (pinfunction "G_15") (pintype "input"))
    )
    (net (code "106") (name "Net-(AUTO_CLOCK-DIS)") (class "Default")
      (node (ref "AUTO_CLOCK") (pin "7") (pinfunction "DIS_7") (pintype "input"))
      (node (ref "FREQUENCY") (pin "E") (pinfunction "E_E") (pintype "passive"))
      (node (ref "R1") (pin "2") (pinfunction "2_2") (pintype "passive"))
    )
    (net (code "107") (name "Net-(AUTO_CLOCK-THR)") (class "Default")
      (node (ref "AUTO_CLOCK") (pin "2") (pinfunction "TR_2") (pintype "input"))
      (node (ref "AUTO_CLOCK") (pin "6") (pinfunction "THR_6") (pintype "input"))
      (node (ref "C1") (pin "+") (pinfunction "+_+") (pintype "passive"))
      (node (ref "R7") (pin "2") (pinfunction "2_2") (pintype "passive"))
    )
    (net (code "108") (name "Net-(BRANCH_SELECTORA-A)") (class "Default")
      (node (ref "BRANCH_SELECTOR") (pin "2") (pinfunction "A_2") (pintype "input"))
      (node (ref "INSTRUCTION_MEMORY_2") (pin "19") (pinfunction "19_19") (pintype "passive"))
    )
    (net (code "109") (name "Net-(BRANCH_SELECTORA-B)") (class "Default")
      (node (ref "BRANCH_SELECTOR") (pin "3") (pinfunction "B_3") (pintype "input"))
      (node (ref "INSTRUCTION_MEMORY_2") (pin "18") (pinfunction "18_18") (pintype "passive"))
    )
    (net (code "110") (name "Net-(BRANCH_SELECTORA-Y0)") (class "Default")
      (node (ref "BRANCH_SELECTOR") (pin "4") (pinfunction "Y0_4") (pintype "output"))
      (node (ref "NOT_GATE4_") (pin "1") (pinfunction "I_1") (pintype "input"))
    )
    (net (code "111") (name "Net-(BRANCH_SELECTORA-Y1)") (class "Default")
      (node (ref "BRANCH_SELECTOR") (pin "5") (pinfunction "Y1_5") (pintype "output"))
      (node (ref "NOT_GATE2_") (pin "9") (pinfunction "I_9") (pintype "input"))
    )
    (net (code "112") (name "Net-(BRANCH_SELECTORA-Y2)") (class "Default")
      (node (ref "BRANCH_SELECTOR") (pin "6") (pinfunction "Y2_6") (pintype "output"))
      (node (ref "NOT_GATE2_") (pin "5") (pinfunction "I_5") (pintype "input"))
    )
    (net (code "113") (name "Net-(BRANCH_SELECTORA-Y3)") (class "Default")
      (node (ref "BRANCH_SELECTOR") (pin "7") (pinfunction "Y3_7") (pintype "output"))
      (node (ref "NOT_GATE1") (pin "1") (pinfunction "I_1") (pintype "input"))
    )
    (net (code "114") (name "Net-(BRANCH_SELECTORB-A)") (class "Default")
      (node (ref "BRANCH_SELECTOR") (pin "14") (pinfunction "A_14") (pintype "input"))
      (node (ref "INSRUCTION_REGISTER_SELECTOR_LOWER") (pin "4") (pinfunction "1Y_4") (pintype "output"))
    )
    (net (code "115") (name "Net-(BRANCH_SELECTORB-B)") (class "Default")
      (node (ref "BRANCH_SELECTOR") (pin "13") (pinfunction "B_13") (pintype "input"))
      (node (ref "INSRUCTION_REGISTER_SELECTOR_LOWER") (pin "7") (pinfunction "2Y_7") (pintype "output"))
    )
    (net (code "116") (name "Net-(BRANCH_SELECTORB-Y1)") (class "Default")
      (node (ref "BRANCH_SELECTOR") (pin "11") (pinfunction "Y1_11") (pintype "output"))
      (node (ref "OUTPUT_BUFFER_REG_A") (pin "19") (pinfunction "G_19") (pintype "input"))
    )
    (net (code "117") (name "Net-(BRANCH_SELECTORB-Y3)") (class "Default")
      (node (ref "BRANCH_SELECTOR") (pin "9") (pinfunction "Y3_9") (pintype "output"))
      (node (ref "NOT_GATE4_") (pin "13") (pinfunction "I_13") (pintype "input"))
    )
    (net (code "118") (name "Net-(CLK_TRIGGER-S1)") (class "Default")
      (node (ref "CLK_TRIGGER") (pin "2") (pinfunction "S1_2") (pintype "passive"))
      (node (ref "R2") (pin "2") (pinfunction "2_2") (pintype "passive"))
      (node (ref "STEPPER_CLOCK") (pin "2") (pinfunction "TR_2") (pintype "input"))
    )
    (net (code "119") (name "Net-(CLOCK-C)") (class "Default")
      (node (ref "CLOCK") (pin "K") (pinfunction "C_K") (pintype "passive"))
      (node (ref "R5") (pin "2") (pinfunction "2_2") (pintype "passive"))
    )
    (net (code "120") (name "Net-(DATABUS_1-C)") (class "Default")
      (node (ref "DATABUS_1") (pin "K") (pinfunction "C_K") (pintype "passive"))
      (node (ref "R24") (pin "1") (pinfunction "1_1") (pintype "passive"))
    )
    (net (code "121") (name "Net-(DATABUS_2-C)") (class "Default")
      (node (ref "DATABUS_2") (pin "K") (pinfunction "C_K") (pintype "passive"))
      (node (ref "R25") (pin "1") (pinfunction "1_1") (pintype "passive"))
    )
    (net (code "122") (name "Net-(DATABUS_3-C)") (class "Default")
      (node (ref "DATABUS_3") (pin "K") (pinfunction "C_K") (pintype "passive"))
      (node (ref "R26") (pin "1") (pinfunction "1_1") (pintype "passive"))
    )
    (net (code "123") (name "Net-(DATABUS_4-C)") (class "Default")
      (node (ref "DATABUS_4") (pin "K") (pinfunction "C_K") (pintype "passive"))
      (node (ref "R27") (pin "1") (pinfunction "1_1") (pintype "passive"))
    )
    (net (code "124") (name "Net-(DATABUS_5-C)") (class "Default")
      (node (ref "DATABUS_5") (pin "K") (pinfunction "C_K") (pintype "passive"))
      (node (ref "R28") (pin "1") (pinfunction "1_1") (pintype "passive"))
    )
    (net (code "125") (name "Net-(DATABUS_6-C)") (class "Default")
      (node (ref "DATABUS_6") (pin "K") (pinfunction "C_K") (pintype "passive"))
      (node (ref "R29") (pin "1") (pinfunction "1_1") (pintype "passive"))
    )
    (net (code "126") (name "Net-(DATABUS_7-C)") (class "Default")
      (node (ref "DATABUS_7") (pin "K") (pinfunction "C_K") (pintype "passive"))
      (node (ref "R30") (pin "1") (pinfunction "1_1") (pintype "passive"))
    )
    (net (code "127") (name "Net-(DATABUS_8-C)") (class "Default")
      (node (ref "DATABUS_8") (pin "K") (pinfunction "C_K") (pintype "passive"))
      (node (ref "R31") (pin "1") (pinfunction "1_1") (pintype "passive"))
    )
    (net (code "128") (name "Net-(FLAG_1-C)") (class "Default")
      (node (ref "FLAG_1") (pin "K") (pinfunction "C_K") (pintype "passive"))
      (node (ref "R15") (pin "2") (pinfunction "2_2") (pintype "passive"))
    )
    (net (code "129") (name "Net-(FLAG_2-C)") (class "Default")
      (node (ref "FLAG_2") (pin "K") (pinfunction "C_K") (pintype "passive"))
      (node (ref "R77") (pin "2") (pinfunction "2_2") (pintype "passive"))
    )
    (net (code "130") (name "Net-(FLAG_3-C)") (class "Default")
      (node (ref "FLAG_3") (pin "K") (pinfunction "C_K") (pintype "passive"))
      (node (ref "R78") (pin "2") (pinfunction "2_2") (pintype "passive"))
    )
    (net (code "131") (name "Net-(FLAG_4-C)") (class "Default")
      (node (ref "FLAG_4") (pin "K") (pinfunction "C_K") (pintype "passive"))
      (node (ref "R79") (pin "2") (pinfunction "2_2") (pintype "passive"))
    )
    (net (code "132") (name "Net-(FLAG_5-C)") (class "Default")
      (node (ref "FLAG_5") (pin "K") (pinfunction "C_K") (pintype "passive"))
      (node (ref "R11") (pin "2") (pinfunction "2_2") (pintype "passive"))
    )
    (net (code "133") (name "Net-(FLAG_6-C)") (class "Default")
      (node (ref "FLAG_6") (pin "K") (pinfunction "C_K") (pintype "passive"))
      (node (ref "R10") (pin "2") (pinfunction "2_2") (pintype "passive"))
    )
    (net (code "134") (name "Net-(FLAG_7-C)") (class "Default")
      (node (ref "FLAG_7") (pin "K") (pinfunction "C_K") (pintype "passive"))
      (node (ref "R9") (pin "2") (pinfunction "2_2") (pintype "passive"))
    )
    (net (code "135") (name "Net-(FLAG_8-C)") (class "Default")
      (node (ref "FLAG_8") (pin "K") (pinfunction "C_K") (pintype "passive"))
      (node (ref "R8") (pin "2") (pinfunction "2_2") (pintype "passive"))
    )
    (net (code "136") (name "Net-(FLAG_REG_LOWERA-D2)") (class "Default")
      (node (ref "FLAG_REG_LOWER") (pin "13") (pinfunction "D2_13") (pintype "input"))
      (node (ref "XOR_GATE_2") (pin "8") (pinfunction "O_8") (pintype "output"))
    )
    (net (code "137") (name "Net-(FLAG_REG_LOWERA-D3)") (class "Default")
      (node (ref "FLAG_REG_LOWER") (pin "12") (pinfunction "D3_12") (pintype "input"))
      (node (ref "XOR_GATE_2") (pin "6") (pinfunction "O_6") (pintype "output"))
    )
    (net (code "138") (name "Net-(FLAG_REG_LOWERA-D4)") (class "Default")
      (node (ref "FLAG_REG_LOWER") (pin "11") (pinfunction "D4_11") (pintype "input"))
      (node (ref "XOR_GATE_2") (pin "3") (pinfunction "O_3") (pintype "output"))
    )
    (net (code "139") (name "Net-(FLAG_REG_LOWERA-G1)") (class "Default")
      (node (ref "FLAG_REG_LOWER") (pin "10") (pinfunction "G2_10") (pintype "input"))
      (node (ref "FLAG_REG_LOWER") (pin "9") (pinfunction "G1_9") (pintype "input"))
      (node (ref "FLAG_REG_UPPER") (pin "10") (pinfunction "G2_10") (pintype "input"))
      (node (ref "FLAG_REG_UPPER") (pin "9") (pinfunction "G1_9") (pintype "input"))
      (node (ref "NOT_GATE1") (pin "12") (pinfunction "O_12") (pintype "output"))
    )
    (net (code "140") (name "Net-(FLAG_REG_LOWERA-Q1)") (class "Default")
      (node (ref "FLAG_8") (pin "A") (pinfunction "A_A") (pintype "passive"))
      (node (ref "FLAG_REG_LOWER") (pin "3") (pinfunction "Q1_3") (pintype "tri_state"))
      (node (ref "OUTPUT_BUFFER_FLAGS") (pin "11") (pinfunction "B8_11") (pintype "bidirectional"))
    )
    (net (code "141") (name "Net-(FLAG_REG_LOWERA-Q2)") (class "Default")
      (node (ref "FLAG_7") (pin "A") (pinfunction "A_A") (pintype "passive"))
      (node (ref "FLAG_REG_LOWER") (pin "4") (pinfunction "Q2_4") (pintype "tri_state"))
      (node (ref "OUTPUT_BUFFER_FLAGS") (pin "12") (pinfunction "B7_12") (pintype "bidirectional"))
      (node (ref "XOR_GATE_2") (pin "9") (pinfunction "I0_9") (pintype "input"))
    )
    (net (code "142") (name "Net-(FLAG_REG_LOWERA-Q3)") (class "Default")
      (node (ref "FLAG_6") (pin "A") (pinfunction "A_A") (pintype "passive"))
      (node (ref "FLAG_REG_LOWER") (pin "5") (pinfunction "Q3_5") (pintype "tri_state"))
      (node (ref "OUTPUT_BUFFER_FLAGS") (pin "13") (pinfunction "B6_13") (pintype "bidirectional"))
      (node (ref "XOR_GATE_2") (pin "4") (pinfunction "I0_4") (pintype "input"))
    )
    (net (code "143") (name "Net-(FLAG_REG_LOWERA-Q4)") (class "Default")
      (node (ref "FLAG_5") (pin "A") (pinfunction "A_A") (pintype "passive"))
      (node (ref "FLAG_REG_LOWER") (pin "6") (pinfunction "Q4_6") (pintype "tri_state"))
      (node (ref "OUTPUT_BUFFER_FLAGS") (pin "14") (pinfunction "B5_14") (pintype "bidirectional"))
      (node (ref "XOR_GATE_2") (pin "1") (pinfunction "I0_1") (pintype "input"))
    )
    (net (code "144") (name "Net-(FLAG_REG_UPPERA-D1)") (class "Default")
      (node (ref "FLAG_REG_UPPER") (pin "14") (pinfunction "D1_14") (pintype "input"))
      (node (ref "XOR_GATE_1") (pin "11") (pinfunction "O_11") (pintype "output"))
    )
    (net (code "145") (name "Net-(FLAG_REG_UPPERA-D2)") (class "Default")
      (node (ref "FLAG_REG_UPPER") (pin "13") (pinfunction "D2_13") (pintype "input"))
      (node (ref "XOR_GATE_1") (pin "8") (pinfunction "O_8") (pintype "output"))
    )
    (net (code "146") (name "Net-(FLAG_REG_UPPERA-D3)") (class "Default")
      (node (ref "FLAG_REG_UPPER") (pin "12") (pinfunction "D3_12") (pintype "input"))
      (node (ref "XOR_GATE_1") (pin "6") (pinfunction "O_6") (pintype "output"))
    )
    (net (code "147") (name "Net-(FLAG_REG_UPPERA-D4)") (class "Default")
      (node (ref "FLAG_REG_UPPER") (pin "11") (pinfunction "D4_11") (pintype "input"))
      (node (ref "XOR_GATE_1") (pin "3") (pinfunction "O_3") (pintype "output"))
    )
    (net (code "148") (name "Net-(FLAG_REG_UPPERA-Q1)") (class "Default")
      (node (ref "FLAG_4") (pin "A") (pinfunction "A_A") (pintype "passive"))
      (node (ref "FLAG_REG_UPPER") (pin "3") (pinfunction "Q1_3") (pintype "tri_state"))
      (node (ref "OUTPUT_BUFFER_FLAGS") (pin "15") (pinfunction "B4_15") (pintype "bidirectional"))
      (node (ref "XOR_GATE_1") (pin "12") (pinfunction "I0_12") (pintype "input"))
    )
    (net (code "149") (name "Net-(FLAG_REG_UPPERA-Q2)") (class "Default")
      (node (ref "FLAG_3") (pin "A") (pinfunction "A_A") (pintype "passive"))
      (node (ref "FLAG_REG_UPPER") (pin "4") (pinfunction "Q2_4") (pintype "tri_state"))
      (node (ref "OUTPUT_BUFFER_FLAGS") (pin "16") (pinfunction "B3_16") (pintype "bidirectional"))
      (node (ref "XOR_GATE_1") (pin "9") (pinfunction "I0_9") (pintype "input"))
    )
    (net (code "150") (name "Net-(FLAG_REG_UPPERA-Q3)") (class "Default")
      (node (ref "FLAG_2") (pin "A") (pinfunction "A_A") (pintype "passive"))
      (node (ref "FLAG_REG_UPPER") (pin "5") (pinfunction "Q3_5") (pintype "tri_state"))
      (node (ref "OUTPUT_BUFFER_FLAGS") (pin "17") (pinfunction "B2_17") (pintype "bidirectional"))
      (node (ref "XOR_GATE_1") (pin "4") (pinfunction "I0_4") (pintype "input"))
    )
    (net (code "151") (name "Net-(FLAG_REG_UPPERA-Q4)") (class "Default")
      (node (ref "FLAG_1") (pin "A") (pinfunction "A_A") (pintype "passive"))
      (node (ref "FLAG_REG_UPPER") (pin "6") (pinfunction "Q4_6") (pintype "tri_state"))
      (node (ref "MEMORY") (pin "25") (pinfunction "25_25") (pintype "passive"))
      (node (ref "OUTPUT_BUFFER_FLAGS") (pin "18") (pinfunction "B1_18") (pintype "bidirectional"))
      (node (ref "XOR_GATE_1") (pin "1") (pinfunction "I0_1") (pintype "input"))
    )
    (net (code "152") (name "Net-(FREQUENCY-PadS)") (class "Default")
      (node (ref "FREQUENCY") (pin "S") (pinfunction "S_S") (pintype "passive"))
      (node (ref "R7") (pin "1") (pinfunction "1_1") (pintype "passive"))
    )
    (net (code "153") (name "Net-(INSRUCTION_REGISTER_SELECTOR_LOWERA-1B)") (class "Default")
      (node (ref "INSRUCTION_REGISTER_SELECTOR_LOWER") (pin "3") (pinfunction "1B_3") (pintype "input"))
      (node (ref "INSTRUCTION_MEMORY_0") (pin "15") (pinfunction "15_15") (pintype "passive"))
      (node (ref "OUTPUT_BUFFER_INSTRUCTION") (pin "5") (pinfunction "A4_5") (pintype "bidirectional"))
    )
    (net (code "154") (name "Net-(INSRUCTION_REGISTER_SELECTOR_LOWERA-2B)") (class "Default")
      (node (ref "INSRUCTION_REGISTER_SELECTOR_LOWER") (pin "6") (pinfunction "2B_6") (pintype "input"))
      (node (ref "INSTRUCTION_MEMORY_0") (pin "13") (pinfunction "13_13") (pintype "passive"))
      (node (ref "OUTPUT_BUFFER_INSTRUCTION") (pin "4") (pinfunction "A3_4") (pintype "bidirectional"))
    )
    (net (code "155") (name "Net-(INSRUCTION_REGISTER_SELECTOR_LOWERA-3B)") (class "Default")
      (node (ref "INSRUCTION_REGISTER_SELECTOR_LOWER") (pin "10") (pinfunction "3B_10") (pintype "input"))
      (node (ref "INSTRUCTION_MEMORY_0") (pin "12") (pinfunction "12_12") (pintype "passive"))
      (node (ref "OUTPUT_BUFFER_INSTRUCTION") (pin "3") (pinfunction "A2_3") (pintype "bidirectional"))
    )
    (net (code "156") (name "Net-(INSRUCTION_REGISTER_SELECTOR_LOWERA-3Y)") (class "Default")
      (node (ref "INSRUCTION_REGISTER_SELECTOR_LOWER") (pin "9") (pinfunction "3Y_9") (pintype "output"))
      (node (ref "NOT_GATE1") (pin "9") (pinfunction "I_9") (pintype "input"))
    )
    (net (code "157") (name "Net-(INSRUCTION_REGISTER_SELECTOR_LOWERA-4B)") (class "Default")
      (node (ref "INSRUCTION_REGISTER_SELECTOR_LOWER") (pin "13") (pinfunction "4B_13") (pintype "input"))
      (node (ref "INSTRUCTION_MEMORY_0") (pin "11") (pinfunction "11_11") (pintype "passive"))
      (node (ref "OUTPUT_BUFFER_INSTRUCTION") (pin "2") (pinfunction "A1_2") (pintype "bidirectional"))
    )
    (net (code "158") (name "Net-(INSRUCTION_REGISTER_SELECTOR_LOWERA-4Y)") (class "Default")
      (node (ref "INSRUCTION_REGISTER_SELECTOR_LOWER") (pin "12") (pinfunction "4Y_12") (pintype "output"))
      (node (ref "NOT_GATE1") (pin "5") (pinfunction "I_5") (pintype "input"))
    )
    (net (code "159") (name "Net-(INSRUCTION_REGISTER_SELECTOR_LOWERA-~{A}{slash}B)") (class "Default")
      (node (ref "INSRUCTION_REGISTER_SELECTOR_LOWER") (pin "1") (pinfunction "~{A}/B_1") (pintype "input"))
      (node (ref "INSRUCTION_REGISTER_SELECTOR_UPPER") (pin "1") (pinfunction "~{A}/B_1") (pintype "input"))
      (node (ref "OUTPUT_BUFFER_INSTRUCTION") (pin "19") (pinfunction "G_19") (pintype "input"))
      (node (ref "SELECTOR_LOGIC2_") (pin "6") (pinfunction "Y2_6") (pintype "output"))
    )
    (net (code "160") (name "Net-(INSRUCTION_REGISTER_SELECTOR_UPPERA-1B)") (class "Default")
      (node (ref "INSRUCTION_REGISTER_SELECTOR_UPPER") (pin "3") (pinfunction "1B_3") (pintype "input"))
      (node (ref "INSTRUCTION_MEMORY_0") (pin "19") (pinfunction "19_19") (pintype "passive"))
      (node (ref "OUTPUT_BUFFER_INSTRUCTION") (pin "9") (pinfunction "A8_9") (pintype "bidirectional"))
    )
    (net (code "161") (name "Net-(INSRUCTION_REGISTER_SELECTOR_UPPERA-1Y)") (class "Default")
      (node (ref "INSRUCTION_REGISTER_SELECTOR_UPPER") (pin "4") (pinfunction "1Y_4") (pintype "output"))
      (node (ref "NOT_GATE4_") (pin "3") (pinfunction "I_3") (pintype "input"))
    )
    (net (code "162") (name "Net-(INSRUCTION_REGISTER_SELECTOR_UPPERA-2B)") (class "Default")
      (node (ref "INSRUCTION_REGISTER_SELECTOR_UPPER") (pin "6") (pinfunction "2B_6") (pintype "input"))
      (node (ref "INSTRUCTION_MEMORY_0") (pin "18") (pinfunction "18_18") (pintype "passive"))
      (node (ref "OUTPUT_BUFFER_INSTRUCTION") (pin "8") (pinfunction "A7_8") (pintype "bidirectional"))
    )
    (net (code "163") (name "Net-(INSRUCTION_REGISTER_SELECTOR_UPPERA-2Y)") (class "Default")
      (node (ref "INSRUCTION_REGISTER_SELECTOR_UPPER") (pin "7") (pinfunction "2Y_7") (pintype "output"))
      (node (ref "NOT_GATE2_") (pin "13") (pinfunction "I_13") (pintype "input"))
      (node (ref "RAM") (pin "22") (pinfunction "22_22") (pintype "passive"))
    )
    (net (code "164") (name "Net-(INSRUCTION_REGISTER_SELECTOR_UPPERA-3B)") (class "Default")
      (node (ref "INSRUCTION_REGISTER_SELECTOR_UPPER") (pin "10") (pinfunction "3B_10") (pintype "input"))
      (node (ref "INSTRUCTION_MEMORY_0") (pin "17") (pinfunction "17_17") (pintype "passive"))
      (node (ref "OUTPUT_BUFFER_INSTRUCTION") (pin "7") (pinfunction "A6_7") (pintype "bidirectional"))
    )
    (net (code "165") (name "Net-(INSRUCTION_REGISTER_SELECTOR_UPPERA-3Y)") (class "Default")
      (node (ref "INSRUCTION_REGISTER_SELECTOR_UPPER") (pin "9") (pinfunction "3Y_9") (pintype "output"))
      (node (ref "SELECTOR_LOGIC_") (pin "14") (pinfunction "A_14") (pintype "input"))
    )
    (net (code "166") (name "Net-(INSRUCTION_REGISTER_SELECTOR_UPPERA-4B)") (class "Default")
      (node (ref "INSRUCTION_REGISTER_SELECTOR_UPPER") (pin "13") (pinfunction "4B_13") (pintype "input"))
      (node (ref "INSTRUCTION_MEMORY_0") (pin "16") (pinfunction "16_16") (pintype "passive"))
      (node (ref "OUTPUT_BUFFER_INSTRUCTION") (pin "6") (pinfunction "A5_6") (pintype "bidirectional"))
    )
    (net (code "167") (name "Net-(INSRUCTION_REGISTER_SELECTOR_UPPERA-4Y)") (class "Default")
      (node (ref "INSRUCTION_REGISTER_SELECTOR_UPPER") (pin "12") (pinfunction "4Y_12") (pintype "output"))
      (node (ref "SELECTOR_LOGIC_") (pin "13") (pinfunction "B_13") (pintype "input"))
    )
    (net (code "168") (name "Net-(INSTRUCTIONS_EXTENSIONB-1)") (class "Default")
      (node (ref "INSTRUCTIONS_EXTENSION") (pin "10") (pinfunction "1_10") (pintype "passive"))
      (node (ref "INSTRUCTION_MEMORY_0") (pin "24") (pinfunction "24_24") (pintype "passive"))
      (node (ref "INSTRUCTION_MEMORY_1") (pin "24") (pinfunction "24_24") (pintype "passive"))
      (node (ref "INSTRUCTION_MEMORY_2") (pin "24") (pinfunction "24_24") (pintype "passive"))
      (node (ref "MICRO_COUNTER_LOWER") (pin "13") (pinfunction "13_13") (pintype "passive"))
      (node (ref "USTEP_2") (pin "A") (pinfunction "A_A") (pintype "passive"))
    )
    (net (code "169") (name "Net-(INSTRUCTIONS_EXTENSIONC-1)") (class "Default")
      (node (ref "INSTRUCTIONS_EXTENSION") (pin "11") (pinfunction "1_11") (pintype "passive"))
      (node (ref "INSTRUCTION_MEMORY_0") (pin "21") (pinfunction "21_21") (pintype "passive"))
      (node (ref "INSTRUCTION_MEMORY_1") (pin "21") (pinfunction "21_21") (pintype "passive"))
      (node (ref "INSTRUCTION_MEMORY_2") (pin "21") (pinfunction "21_21") (pintype "passive"))
      (node (ref "MICRO_COUNTER_LOWER") (pin "12") (pinfunction "12_12") (pintype "passive"))
      (node (ref "USTEP_4") (pin "A") (pinfunction "A_A") (pintype "passive"))
    )
    (net (code "170") (name "Net-(INSTRUCTIONS_EXTENSIOND-1)") (class "Default")
      (node (ref "INSTRUCTIONS_EXTENSION") (pin "12") (pinfunction "1_12") (pintype "passive"))
      (node (ref "INSTRUCTION_MEMORY_0") (pin "23") (pinfunction "23_23") (pintype "passive"))
      (node (ref "INSTRUCTION_MEMORY_1") (pin "23") (pinfunction "23_23") (pintype "passive"))
      (node (ref "INSTRUCTION_MEMORY_2") (pin "23") (pinfunction "23_23") (pintype "passive"))
      (node (ref "MICRO_COUNTER_LOWER") (pin "11") (pinfunction "11_11") (pintype "passive"))
      (node (ref "USTEP_3") (pin "A") (pinfunction "A_A") (pintype "passive"))
    )
    (net (code "171") (name "Net-(INSTRUCTIONS_EXTENSIONE-1)") (class "Default")
      (node (ref "INSTRUCTIONS_EXTENSION") (pin "13") (pinfunction "1_13") (pintype "passive"))
      (node (ref "INSTRUCTION_MEMORY_0") (pin "2") (pinfunction "2_2") (pintype "passive"))
      (node (ref "INSTRUCTION_MEMORY_1") (pin "2") (pinfunction "2_2") (pintype "passive"))
      (node (ref "INSTRUCTION_MEMORY_2") (pin "2") (pinfunction "2_2") (pintype "passive"))
      (node (ref "MICRO_COUNTER_UPPER") (pin "14") (pinfunction "14_14") (pintype "passive"))
      (node (ref "USTEP_5") (pin "A") (pinfunction "A_A") (pintype "passive"))
    )
    (net (code "172") (name "Net-(INSTRUCTIONS_EXTENSIONH-1)") (class "Default")
      (node (ref "INSTRUCTIONS_EXTENSION") (pin "2") (pinfunction "1_2") (pintype "passive"))
      (node (ref "INSTRUCTION_MEMORY_0") (pin "9") (pinfunction "9_9") (pintype "passive"))
      (node (ref "INSTRUCTION_MEMORY_1") (pin "9") (pinfunction "9_9") (pintype "passive"))
      (node (ref "INSTRUCTION_MEMORY_2") (pin "9") (pinfunction "9_9") (pintype "passive"))
      (node (ref "INSTRUC_REGISTER_LOWER") (pin "5") (pinfunction "Q3_5") (pintype "tri_state"))
    )
    (net (code "173") (name "Net-(INSTRUCTIONS_EXTENSIONI-1)") (class "Default")
      (node (ref "INSTRUCTIONS_EXTENSION") (pin "3") (pinfunction "1_3") (pintype "passive"))
      (node (ref "INSTRUCTION_MEMORY_0") (pin "8") (pinfunction "8_8") (pintype "passive"))
      (node (ref "INSTRUCTION_MEMORY_1") (pin "8") (pinfunction "8_8") (pintype "passive"))
      (node (ref "INSTRUCTION_MEMORY_2") (pin "8") (pinfunction "8_8") (pintype "passive"))
      (node (ref "INSTRUC_REGISTER_LOWER") (pin "4") (pinfunction "Q2_4") (pintype "tri_state"))
    )
    (net (code "174") (name "Net-(INSTRUCTIONS_EXTENSIONJ-1)") (class "Default")
      (node (ref "INSTRUCTIONS_EXTENSION") (pin "4") (pinfunction "1_4") (pintype "passive"))
      (node (ref "INSTRUCTION_MEMORY_0") (pin "7") (pinfunction "7_7") (pintype "passive"))
      (node (ref "INSTRUCTION_MEMORY_1") (pin "7") (pinfunction "7_7") (pintype "passive"))
      (node (ref "INSTRUCTION_MEMORY_2") (pin "7") (pinfunction "7_7") (pintype "passive"))
      (node (ref "INSTRUC_REGISTER_LOWER") (pin "3") (pinfunction "Q1_3") (pintype "tri_state"))
    )
    (net (code "175") (name "Net-(INSTRUCTIONS_EXTENSIONK-1)") (class "Default")
      (node (ref "INSTRUCTIONS_EXTENSION") (pin "5") (pinfunction "1_5") (pintype "passive"))
      (node (ref "INSTRUCTION_MEMORY_0") (pin "6") (pinfunction "6_6") (pintype "passive"))
      (node (ref "INSTRUCTION_MEMORY_1") (pin "6") (pinfunction "6_6") (pintype "passive"))
      (node (ref "INSTRUCTION_MEMORY_2") (pin "6") (pinfunction "6_6") (pintype "passive"))
      (node (ref "INSTRUC_REGISTER_UPPER") (pin "6") (pinfunction "Q4_6") (pintype "tri_state"))
    )
    (net (code "176") (name "Net-(INSTRUCTIONS_EXTENSIONL-1)") (class "Default")
      (node (ref "INSTRUCTIONS_EXTENSION") (pin "6") (pinfunction "1_6") (pintype "passive"))
      (node (ref "INSTRUCTION_MEMORY_0") (pin "5") (pinfunction "5_5") (pintype "passive"))
      (node (ref "INSTRUCTION_MEMORY_1") (pin "5") (pinfunction "5_5") (pintype "passive"))
      (node (ref "INSTRUCTION_MEMORY_2") (pin "5") (pinfunction "5_5") (pintype "passive"))
      (node (ref "INSTRUC_REGISTER_UPPER") (pin "5") (pinfunction "Q3_5") (pintype "tri_state"))
    )
    (net (code "177") (name "Net-(INSTRUCTIONS_EXTENSIONM-1)") (class "Default")
      (node (ref "INSTRUCTIONS_EXTENSION") (pin "7") (pinfunction "1_7") (pintype "passive"))
      (node (ref "INSTRUCTION_MEMORY_0") (pin "4") (pinfunction "4_4") (pintype "passive"))
      (node (ref "INSTRUCTION_MEMORY_1") (pin "4") (pinfunction "4_4") (pintype "passive"))
      (node (ref "INSTRUCTION_MEMORY_2") (pin "4") (pinfunction "4_4") (pintype "passive"))
      (node (ref "INSTRUC_REGISTER_UPPER") (pin "4") (pinfunction "Q2_4") (pintype "tri_state"))
    )
    (net (code "178") (name "Net-(INSTRUCTIONS_EXTENSIONN-1)") (class "Default")
      (node (ref "INSTRUCTIONS_EXTENSION") (pin "8") (pinfunction "1_8") (pintype "passive"))
      (node (ref "INSTRUCTION_MEMORY_0") (pin "3") (pinfunction "3_3") (pintype "passive"))
      (node (ref "INSTRUCTION_MEMORY_1") (pin "3") (pinfunction "3_3") (pintype "passive"))
      (node (ref "INSTRUCTION_MEMORY_2") (pin "3") (pinfunction "3_3") (pintype "passive"))
      (node (ref "INSTRUC_REGISTER_UPPER") (pin "3") (pinfunction "Q1_3") (pintype "tri_state"))
    )
    (net (code "179") (name "Net-(INSTRUCTIONS_EXTENSIONO-1)") (class "Default")
      (node (ref "INSTRUCTIONS_EXTENSION") (pin "9") (pinfunction "1_9") (pintype "passive"))
      (node (ref "INSTRUCTION_MEMORY_0") (pin "25") (pinfunction "25_25") (pintype "passive"))
      (node (ref "INSTRUCTION_MEMORY_1") (pin "25") (pinfunction "25_25") (pintype "passive"))
      (node (ref "INSTRUCTION_MEMORY_2") (pin "25") (pinfunction "25_25") (pintype "passive"))
      (node (ref "MICRO_COUNTER_LOWER") (pin "14") (pinfunction "14_14") (pintype "passive"))
      (node (ref "USTEP_1") (pin "A") (pinfunction "A_A") (pintype "passive"))
    )
    (net (code "180") (name "Net-(INSTRUC_REGISTER_LOWERA-G1)") (class "Default")
      (node (ref "INSTRUC_REGISTER_LOWER") (pin "10") (pinfunction "G2_10") (pintype "input"))
      (node (ref "INSTRUC_REGISTER_LOWER") (pin "9") (pinfunction "G1_9") (pintype "input"))
      (node (ref "INSTRUC_REGISTER_UPPER") (pin "10") (pinfunction "G2_10") (pintype "input"))
      (node (ref "INSTRUC_REGISTER_UPPER") (pin "9") (pinfunction "G1_9") (pintype "input"))
      (node (ref "SELECTOR_LOGIC2_") (pin "5") (pinfunction "Y1_5") (pintype "output"))
    )
    (net (code "181") (name "Net-(INSTRUC_REGISTER_LOWERA-Q4)") (class "Default")
      (node (ref "INSTRUCTIONS_EXTENSION") (pin "1") (pinfunction "1_1") (pintype "passive"))
      (node (ref "INSTRUCTION_MEMORY_0") (pin "10") (pinfunction "10_10") (pintype "passive"))
      (node (ref "INSTRUCTION_MEMORY_1") (pin "10") (pinfunction "10_10") (pintype "passive"))
      (node (ref "INSTRUCTION_MEMORY_2") (pin "10") (pinfunction "10_10") (pintype "passive"))
      (node (ref "INSTRUC_REGISTER_LOWER") (pin "6") (pinfunction "Q4_6") (pintype "tri_state"))
    )
    (net (code "182") (name "Net-(INVERTED_CLK_LED-C)") (class "Default")
      (node (ref "INVERTED_CLK_LED") (pin "K") (pinfunction "C_K") (pintype "passive"))
      (node (ref "R45") (pin "2") (pinfunction "2_2") (pintype "passive"))
    )
    (net (code "183") (name "Net-(LED_A_REG_1-C)") (class "Default")
      (node (ref "LED_A_REG_1") (pin "K") (pinfunction "C_K") (pintype "passive"))
      (node (ref "R53") (pin "1") (pinfunction "1_1") (pintype "passive"))
    )
    (net (code "184") (name "Net-(LED_A_REG_2-C)") (class "Default")
      (node (ref "LED_A_REG_2") (pin "K") (pinfunction "C_K") (pintype "passive"))
      (node (ref "R54") (pin "1") (pinfunction "1_1") (pintype "passive"))
    )
    (net (code "185") (name "Net-(LED_A_REG_3-C)") (class "Default")
      (node (ref "LED_A_REG_3") (pin "K") (pinfunction "C_K") (pintype "passive"))
      (node (ref "R55") (pin "1") (pinfunction "1_1") (pintype "passive"))
    )
    (net (code "186") (name "Net-(LED_A_REG_4-C)") (class "Default")
      (node (ref "LED_A_REG_4") (pin "K") (pinfunction "C_K") (pintype "passive"))
      (node (ref "R56") (pin "1") (pinfunction "1_1") (pintype "passive"))
    )
    (net (code "187") (name "Net-(LED_A_REG_5-C)") (class "Default")
      (node (ref "LED_A_REG_5") (pin "K") (pinfunction "C_K") (pintype "passive"))
      (node (ref "R57") (pin "1") (pinfunction "1_1") (pintype "passive"))
    )
    (net (code "188") (name "Net-(LED_A_REG_6-C)") (class "Default")
      (node (ref "LED_A_REG_6") (pin "K") (pinfunction "C_K") (pintype "passive"))
      (node (ref "R58") (pin "1") (pinfunction "1_1") (pintype "passive"))
    )
    (net (code "189") (name "Net-(LED_A_REG_7-C)") (class "Default")
      (node (ref "LED_A_REG_7") (pin "K") (pinfunction "C_K") (pintype "passive"))
      (node (ref "R59") (pin "1") (pinfunction "1_1") (pintype "passive"))
    )
    (net (code "190") (name "Net-(LED_A_REG_8-C)") (class "Default")
      (node (ref "LED_A_REG_8") (pin "K") (pinfunction "C_K") (pintype "passive"))
      (node (ref "R60") (pin "1") (pinfunction "1_1") (pintype "passive"))
    )
    (net (code "191") (name "Net-(LED_B_REG_1-C)") (class "Default")
      (node (ref "LED_B_REG_1") (pin "K") (pinfunction "C_K") (pintype "passive"))
      (node (ref "R61") (pin "1") (pinfunction "1_1") (pintype "passive"))
    )
    (net (code "192") (name "Net-(LED_B_REG_2-C)") (class "Default")
      (node (ref "LED_B_REG_2") (pin "K") (pinfunction "C_K") (pintype "passive"))
      (node (ref "R62") (pin "1") (pinfunction "1_1") (pintype "passive"))
    )
    (net (code "193") (name "Net-(LED_B_REG_3-C)") (class "Default")
      (node (ref "LED_B_REG_3") (pin "K") (pinfunction "C_K") (pintype "passive"))
      (node (ref "R63") (pin "1") (pinfunction "1_1") (pintype "passive"))
    )
    (net (code "194") (name "Net-(LED_B_REG_4-C)") (class "Default")
      (node (ref "LED_B_REG_4") (pin "K") (pinfunction "C_K") (pintype "passive"))
      (node (ref "R64") (pin "1") (pinfunction "1_1") (pintype "passive"))
    )
    (net (code "195") (name "Net-(LED_B_REG_5-C)") (class "Default")
      (node (ref "LED_B_REG_5") (pin "K") (pinfunction "C_K") (pintype "passive"))
      (node (ref "R65") (pin "1") (pinfunction "1_1") (pintype "passive"))
    )
    (net (code "196") (name "Net-(LED_B_REG_6-C)") (class "Default")
      (node (ref "LED_B_REG_6") (pin "K") (pinfunction "C_K") (pintype "passive"))
      (node (ref "R66") (pin "1") (pinfunction "1_1") (pintype "passive"))
    )
    (net (code "197") (name "Net-(LED_B_REG_7-C)") (class "Default")
      (node (ref "LED_B_REG_7") (pin "K") (pinfunction "C_K") (pintype "passive"))
      (node (ref "R67") (pin "1") (pinfunction "1_1") (pintype "passive"))
    )
    (net (code "198") (name "Net-(LED_B_REG_8-C)") (class "Default")
      (node (ref "LED_B_REG_8") (pin "K") (pinfunction "C_K") (pintype "passive"))
      (node (ref "R68") (pin "1") (pinfunction "1_1") (pintype "passive"))
    )
    (net (code "199") (name "Net-(LOGIC_LED_1-C)") (class "Default")
      (node (ref "LOGIC_LED_1") (pin "K") (pinfunction "C_K") (pintype "passive"))
      (node (ref "R51") (pin "1") (pinfunction "1_1") (pintype "passive"))
    )
    (net (code "200") (name "Net-(LOGIC_LED_2-C)") (class "Default")
      (node (ref "LOGIC_LED_2") (pin "K") (pinfunction "C_K") (pintype "passive"))
      (node (ref "R50") (pin "1") (pinfunction "1_1") (pintype "passive"))
    )
    (net (code "201") (name "Net-(LOGIC_LED_3-C)") (class "Default")
      (node (ref "LOGIC_LED_3") (pin "K") (pinfunction "C_K") (pintype "passive"))
      (node (ref "R49") (pin "1") (pinfunction "1_1") (pintype "passive"))
    )
    (net (code "202") (name "Net-(LOGIC_LED_4-C)") (class "Default")
      (node (ref "LOGIC_LED_4") (pin "K") (pinfunction "C_K") (pintype "passive"))
      (node (ref "R48") (pin "1") (pinfunction "1_1") (pintype "passive"))
    )
    (net (code "203") (name "Net-(LOGIC_LED_5-C)") (class "Default")
      (node (ref "LOGIC_LED_5") (pin "K") (pinfunction "C_K") (pintype "passive"))
      (node (ref "R47") (pin "1") (pinfunction "1_1") (pintype "passive"))
    )
    (net (code "204") (name "Net-(LOGIC_LED_6-C)") (class "Default")
      (node (ref "LOGIC_LED_6") (pin "K") (pinfunction "C_K") (pintype "passive"))
      (node (ref "R46") (pin "1") (pinfunction "1_1") (pintype "passive"))
    )
    (net (code "205") (name "Net-(LOGIC_LED_7-C)") (class "Default")
      (node (ref "LOGIC_LED_7") (pin "K") (pinfunction "C_K") (pintype "passive"))
      (node (ref "R6") (pin "1") (pinfunction "1_1") (pintype "passive"))
    )
    (net (code "206") (name "Net-(LOGIC_LED_8-C)") (class "Default")
      (node (ref "LOGIC_LED_8") (pin "K") (pinfunction "C_K") (pintype "passive"))
      (node (ref "R52") (pin "1") (pinfunction "1_1") (pintype "passive"))
    )
    (net (code "207") (name "Net-(LOGIC_SELECTOR-AND/OR_LOWERA-1B)") (class "Default")
      (node (ref "LOGIC_SELECTOR-AND/OR_LOWER") (pin "3") (pinfunction "1B_3") (pintype "input"))
      (node (ref "OR_GATE2_") (pin "11") (pinfunction "O_11") (pintype "output"))
    )
    (net (code "208") (name "Net-(LOGIC_SELECTOR-AND/OR_LOWERA-1Y)") (class "Default")
      (node (ref "LOGIC_SELECTOR-AND/OR_LOWER") (pin "4") (pinfunction "1Y_4") (pintype "output"))
      (node (ref "OR_GATE3_") (pin "2") (pinfunction "I1_2") (pintype "input"))
    )
    (net (code "209") (name "Net-(LOGIC_SELECTOR-AND/OR_LOWERA-2B)") (class "Default")
      (node (ref "LOGIC_SELECTOR-AND/OR_LOWER") (pin "6") (pinfunction "2B_6") (pintype "input"))
      (node (ref "OR_GATE2_") (pin "8") (pinfunction "O_8") (pintype "output"))
    )
    (net (code "210") (name "Net-(LOGIC_SELECTOR-AND/OR_LOWERA-2Y)") (class "Default")
      (node (ref "LOGIC_SELECTOR-AND/OR_LOWER") (pin "7") (pinfunction "2Y_7") (pintype "output"))
      (node (ref "OR_GATE3_") (pin "5") (pinfunction "I1_5") (pintype "input"))
    )
    (net (code "211") (name "Net-(LOGIC_SELECTOR-AND/OR_LOWERA-3B)") (class "Default")
      (node (ref "LOGIC_SELECTOR-AND/OR_LOWER") (pin "10") (pinfunction "3B_10") (pintype "input"))
      (node (ref "OR_GATE2_") (pin "6") (pinfunction "O_6") (pintype "output"))
    )
    (net (code "212") (name "Net-(LOGIC_SELECTOR-AND/OR_LOWERA-3Y)") (class "Default")
      (node (ref "LOGIC_SELECTOR-AND/OR_LOWER") (pin "9") (pinfunction "3Y_9") (pintype "output"))
      (node (ref "OR_GATE3_") (pin "10") (pinfunction "I1_10") (pintype "input"))
    )
    (net (code "213") (name "Net-(LOGIC_SELECTOR-AND/OR_LOWERA-4B)") (class "Default")
      (node (ref "LOGIC_SELECTOR-AND/OR_LOWER") (pin "13") (pinfunction "4B_13") (pintype "input"))
      (node (ref "OR_GATE2_") (pin "3") (pinfunction "O_3") (pintype "output"))
    )
    (net (code "214") (name "Net-(LOGIC_SELECTOR-AND/OR_LOWERA-4Y)") (class "Default")
      (node (ref "LOGIC_SELECTOR-AND/OR_LOWER") (pin "12") (pinfunction "4Y_12") (pintype "output"))
      (node (ref "OR_GATE3_") (pin "13") (pinfunction "I1_13") (pintype "input"))
    )
    (net (code "215") (name "Net-(LOGIC_SELECTOR-AND/OR_LOWERA-~{A}{slash}B)") (class "Default")
      (node (ref "INSTRUCTION_MEMORY_2") (pin "12") (pinfunction "12_12") (pintype "passive"))
      (node (ref "LOGIC_SELECTOR-AND/OR_LOWER") (pin "1") (pinfunction "~{A}/B_1") (pintype "input"))
      (node (ref "LOGIC_SELECTOR-AND/OR_UPPER") (pin "1") (pinfunction "~{A}/B_1") (pintype "input"))
      (node (ref "LOGIC_SELECTOR-XOR/NOT_LOWER") (pin "1") (pinfunction "~{A}/B_1") (pintype "input"))
      (node (ref "LOGIC_SELECTOR-XOR/NOT_UPPER") (pin "1") (pinfunction "~{A}/B_1") (pintype "input"))
      (node (ref "SELECTOR_LOGIC_") (pin "2") (pinfunction "A_2") (pintype "input"))
    )
    (net (code "216") (name "Net-(LOGIC_SELECTOR-AND/OR_UPPERA-1B)") (class "Default")
      (node (ref "LOGIC_SELECTOR-AND/OR_UPPER") (pin "3") (pinfunction "1B_3") (pintype "input"))
      (node (ref "OR_GATE1_") (pin "11") (pinfunction "O_11") (pintype "output"))
    )
    (net (code "217") (name "Net-(LOGIC_SELECTOR-AND/OR_UPPERA-1Y)") (class "Default")
      (node (ref "LOGIC_SELECTOR-AND/OR_UPPER") (pin "4") (pinfunction "1Y_4") (pintype "output"))
      (node (ref "OR_GATE4_") (pin "2") (pinfunction "I1_2") (pintype "input"))
    )
    (net (code "218") (name "Net-(LOGIC_SELECTOR-AND/OR_UPPERA-2B)") (class "Default")
      (node (ref "LOGIC_SELECTOR-AND/OR_UPPER") (pin "6") (pinfunction "2B_6") (pintype "input"))
      (node (ref "OR_GATE1_") (pin "8") (pinfunction "O_8") (pintype "output"))
    )
    (net (code "219") (name "Net-(LOGIC_SELECTOR-AND/OR_UPPERA-2Y)") (class "Default")
      (node (ref "LOGIC_SELECTOR-AND/OR_UPPER") (pin "7") (pinfunction "2Y_7") (pintype "output"))
      (node (ref "OR_GATE4_") (pin "5") (pinfunction "I1_5") (pintype "input"))
    )
    (net (code "220") (name "Net-(LOGIC_SELECTOR-AND/OR_UPPERA-3B)") (class "Default")
      (node (ref "LOGIC_SELECTOR-AND/OR_UPPER") (pin "10") (pinfunction "3B_10") (pintype "input"))
      (node (ref "OR_GATE1_") (pin "6") (pinfunction "O_6") (pintype "output"))
    )
    (net (code "221") (name "Net-(LOGIC_SELECTOR-AND/OR_UPPERA-3Y)") (class "Default")
      (node (ref "LOGIC_SELECTOR-AND/OR_UPPER") (pin "9") (pinfunction "3Y_9") (pintype "output"))
      (node (ref "OR_GATE4_") (pin "10") (pinfunction "I1_10") (pintype "input"))
    )
    (net (code "222") (name "Net-(LOGIC_SELECTOR-AND/OR_UPPERA-4B)") (class "Default")
      (node (ref "LOGIC_SELECTOR-AND/OR_UPPER") (pin "13") (pinfunction "4B_13") (pintype "input"))
      (node (ref "OR_GATE1_") (pin "3") (pinfunction "O_3") (pintype "output"))
    )
    (net (code "223") (name "Net-(LOGIC_SELECTOR-AND/OR_UPPERA-4Y)") (class "Default")
      (node (ref "LOGIC_SELECTOR-AND/OR_UPPER") (pin "12") (pinfunction "4Y_12") (pintype "output"))
      (node (ref "OR_GATE4_") (pin "13") (pinfunction "I1_13") (pintype "input"))
    )
    (net (code "224") (name "Net-(LOGIC_SELECTOR-XOR/NOT_LOWERA-1A)") (class "Default")
      (node (ref "LOGIC_SELECTOR-XOR/NOT_LOWER") (pin "2") (pinfunction "1A_2") (pintype "input"))
      (node (ref "NOT_GATE5_") (pin "2") (pinfunction "O_2") (pintype "output"))
    )
    (net (code "225") (name "Net-(LOGIC_SELECTOR-XOR/NOT_LOWERA-1B)") (class "Default")
      (node (ref "LOGIC_SELECTOR-XOR/NOT_LOWER") (pin "3") (pinfunction "1B_3") (pintype "input"))
      (node (ref "XOR_LOGIC_LOWER") (pin "3") (pinfunction "O_3") (pintype "output"))
    )
    (net (code "226") (name "Net-(LOGIC_SELECTOR-XOR/NOT_LOWERA-1Y)") (class "Default")
      (node (ref "LOGIC_SELECTOR-XOR/NOT_LOWER") (pin "4") (pinfunction "1Y_4") (pintype "output"))
      (node (ref "OR_GATE3_") (pin "1") (pinfunction "I0_1") (pintype "input"))
    )
    (net (code "227") (name "Net-(LOGIC_SELECTOR-XOR/NOT_LOWERA-2A)") (class "Default")
      (node (ref "LOGIC_SELECTOR-XOR/NOT_LOWER") (pin "5") (pinfunction "2A_5") (pintype "input"))
      (node (ref "NOT_GATE5_") (pin "4") (pinfunction "O_4") (pintype "output"))
    )
    (net (code "228") (name "Net-(LOGIC_SELECTOR-XOR/NOT_LOWERA-2B)") (class "Default")
      (node (ref "LOGIC_SELECTOR-XOR/NOT_LOWER") (pin "6") (pinfunction "2B_6") (pintype "input"))
      (node (ref "XOR_LOGIC_LOWER") (pin "6") (pinfunction "O_6") (pintype "output"))
    )
    (net (code "229") (name "Net-(LOGIC_SELECTOR-XOR/NOT_LOWERA-2Y)") (class "Default")
      (node (ref "LOGIC_SELECTOR-XOR/NOT_LOWER") (pin "7") (pinfunction "2Y_7") (pintype "output"))
      (node (ref "OR_GATE3_") (pin "4") (pinfunction "I0_4") (pintype "input"))
    )
    (net (code "230") (name "Net-(LOGIC_SELECTOR-XOR/NOT_LOWERA-3A)") (class "Default")
      (node (ref "LOGIC_SELECTOR-XOR/NOT_LOWER") (pin "11") (pinfunction "3A_11") (pintype "input"))
      (node (ref "NOT_GATE5_") (pin "6") (pinfunction "O_6") (pintype "output"))
    )
    (net (code "231") (name "Net-(LOGIC_SELECTOR-XOR/NOT_LOWERA-3B)") (class "Default")
      (node (ref "LOGIC_SELECTOR-XOR/NOT_LOWER") (pin "10") (pinfunction "3B_10") (pintype "input"))
      (node (ref "XOR_LOGIC_LOWER") (pin "8") (pinfunction "O_8") (pintype "output"))
    )
    (net (code "232") (name "Net-(LOGIC_SELECTOR-XOR/NOT_LOWERA-3Y)") (class "Default")
      (node (ref "LOGIC_SELECTOR-XOR/NOT_LOWER") (pin "9") (pinfunction "3Y_9") (pintype "output"))
      (node (ref "OR_GATE3_") (pin "9") (pinfunction "I0_9") (pintype "input"))
    )
    (net (code "233") (name "Net-(LOGIC_SELECTOR-XOR/NOT_LOWERA-4A)") (class "Default")
      (node (ref "LOGIC_SELECTOR-XOR/NOT_LOWER") (pin "14") (pinfunction "4A_14") (pintype "input"))
      (node (ref "NOT_GATE5_") (pin "8") (pinfunction "O_8") (pintype "output"))
    )
    (net (code "234") (name "Net-(LOGIC_SELECTOR-XOR/NOT_LOWERA-4B)") (class "Default")
      (node (ref "LOGIC_SELECTOR-XOR/NOT_LOWER") (pin "13") (pinfunction "4B_13") (pintype "input"))
      (node (ref "XOR_LOGIC_LOWER") (pin "11") (pinfunction "O_11") (pintype "output"))
    )
    (net (code "235") (name "Net-(LOGIC_SELECTOR-XOR/NOT_LOWERA-4Y)") (class "Default")
      (node (ref "LOGIC_SELECTOR-XOR/NOT_LOWER") (pin "12") (pinfunction "4Y_12") (pintype "output"))
      (node (ref "OR_GATE3_") (pin "12") (pinfunction "I0_12") (pintype "input"))
    )
    (net (code "236") (name "Net-(LOGIC_SELECTOR-XOR/NOT_UPPERA-1A)") (class "Default")
      (node (ref "LOGIC_SELECTOR-XOR/NOT_UPPER") (pin "2") (pinfunction "1A_2") (pintype "input"))
      (node (ref "NOT_GATE5_") (pin "10") (pinfunction "O_10") (pintype "output"))
    )
    (net (code "237") (name "Net-(LOGIC_SELECTOR-XOR/NOT_UPPERA-1B)") (class "Default")
      (node (ref "LOGIC_SELECTOR-XOR/NOT_UPPER") (pin "3") (pinfunction "1B_3") (pintype "input"))
      (node (ref "XOR_LOGIC_UPPER") (pin "3") (pinfunction "O_3") (pintype "output"))
    )
    (net (code "238") (name "Net-(LOGIC_SELECTOR-XOR/NOT_UPPERA-1Y)") (class "Default")
      (node (ref "LOGIC_SELECTOR-XOR/NOT_UPPER") (pin "4") (pinfunction "1Y_4") (pintype "output"))
      (node (ref "OR_GATE4_") (pin "1") (pinfunction "I0_1") (pintype "input"))
    )
    (net (code "239") (name "Net-(LOGIC_SELECTOR-XOR/NOT_UPPERA-2A)") (class "Default")
      (node (ref "LOGIC_SELECTOR-XOR/NOT_UPPER") (pin "5") (pinfunction "2A_5") (pintype "input"))
      (node (ref "NOT_GATE5_") (pin "12") (pinfunction "O_12") (pintype "output"))
    )
    (net (code "240") (name "Net-(LOGIC_SELECTOR-XOR/NOT_UPPERA-2B)") (class "Default")
      (node (ref "LOGIC_SELECTOR-XOR/NOT_UPPER") (pin "6") (pinfunction "2B_6") (pintype "input"))
      (node (ref "XOR_LOGIC_UPPER") (pin "6") (pinfunction "O_6") (pintype "output"))
    )
    (net (code "241") (name "Net-(LOGIC_SELECTOR-XOR/NOT_UPPERA-2Y)") (class "Default")
      (node (ref "LOGIC_SELECTOR-XOR/NOT_UPPER") (pin "7") (pinfunction "2Y_7") (pintype "output"))
      (node (ref "OR_GATE4_") (pin "4") (pinfunction "I0_4") (pintype "input"))
    )
    (net (code "242") (name "Net-(LOGIC_SELECTOR-XOR/NOT_UPPERA-3A)") (class "Default")
      (node (ref "LOGIC_SELECTOR-XOR/NOT_UPPER") (pin "11") (pinfunction "3A_11") (pintype "input"))
      (node (ref "NOT_GATE3_") (pin "6") (pinfunction "O_6") (pintype "output"))
    )
    (net (code "243") (name "Net-(LOGIC_SELECTOR-XOR/NOT_UPPERA-3B)") (class "Default")
      (node (ref "LOGIC_SELECTOR-XOR/NOT_UPPER") (pin "10") (pinfunction "3B_10") (pintype "input"))
      (node (ref "XOR_LOGIC_UPPER") (pin "8") (pinfunction "O_8") (pintype "output"))
    )
    (net (code "244") (name "Net-(LOGIC_SELECTOR-XOR/NOT_UPPERA-3Y)") (class "Default")
      (node (ref "LOGIC_SELECTOR-XOR/NOT_UPPER") (pin "9") (pinfunction "3Y_9") (pintype "output"))
      (node (ref "OR_GATE4_") (pin "9") (pinfunction "I0_9") (pintype "input"))
    )
    (net (code "245") (name "Net-(LOGIC_SELECTOR-XOR/NOT_UPPERA-4A)") (class "Default")
      (node (ref "LOGIC_SELECTOR-XOR/NOT_UPPER") (pin "14") (pinfunction "4A_14") (pintype "input"))
      (node (ref "NOT_GATE3_") (pin "8") (pinfunction "O_8") (pintype "output"))
    )
    (net (code "246") (name "Net-(LOGIC_SELECTOR-XOR/NOT_UPPERA-4B)") (class "Default")
      (node (ref "LOGIC_SELECTOR-XOR/NOT_UPPER") (pin "13") (pinfunction "4B_13") (pintype "input"))
      (node (ref "XOR_LOGIC_UPPER") (pin "11") (pinfunction "O_11") (pintype "output"))
    )
    (net (code "247") (name "Net-(LOGIC_SELECTOR-XOR/NOT_UPPERA-4Y)") (class "Default")
      (node (ref "LOGIC_SELECTOR-XOR/NOT_UPPER") (pin "12") (pinfunction "4Y_12") (pintype "output"))
      (node (ref "OR_GATE4_") (pin "12") (pinfunction "I0_12") (pintype "input"))
    )
    (net (code "248") (name "Net-(MICRO_COUNTER_LOWER-Pad15)") (class "Default")
      (node (ref "MICRO_COUNTER_LOWER") (pin "15") (pinfunction "15_15") (pintype "passive"))
      (node (ref "MICRO_COUNTER_UPPER") (pin "10") (pinfunction "10_10") (pintype "passive"))
    )
    (net (code "249") (name "Net-(NOT_GATE1D-O)") (class "Default")
      (node (ref "NOT_GATE1") (pin "8") (pinfunction "O_8") (pintype "output"))
      (node (ref "OUTPUT_BUFFER_MEMORY") (pin "19") (pinfunction "G_19") (pintype "input"))
    )
    (net (code "250") (name "Net-(NOT_GATE1E-O)") (class "Default")
      (node (ref "INVERTED_CLK_LED") (pin "A") (pinfunction "A_A") (pintype "passive"))
      (node (ref "MICRO_COUNTER_LOWER") (pin "2") (pinfunction "2_2") (pintype "passive"))
      (node (ref "MICRO_COUNTER_UPPER") (pin "2") (pinfunction "2_2") (pintype "passive"))
      (node (ref "NOT_GATE1") (pin "10") (pinfunction "O_10") (pintype "output"))
    )
    (net (code "251") (name "Net-(NOT_GATE1F-I)") (class "Default")
      (node (ref "INSTRUCTION_MEMORY_1") (pin "16") (pinfunction "16_16") (pintype "passive"))
      (node (ref "NOT_GATE1") (pin "13") (pinfunction "I_13") (pintype "input"))
    )
    (net (code "252") (name "Net-(NOT_GATE2_A-I)") (class "Default")
      (node (ref "INSTRUCTION_MEMORY_2") (pin "17") (pinfunction "17_17") (pintype "passive"))
      (node (ref "NOT_GATE2_") (pin "1") (pinfunction "I_1") (pintype "input"))
    )
    (net (code "253") (name "Net-(NOT_GATE2_A-O)") (class "Default")
      (node (ref "NOT_GATE2_") (pin "2") (pinfunction "O_2") (pintype "output"))
      (node (ref "OUTPUT_BUFFER_PARAM_REG") (pin "19") (pinfunction "G_19") (pintype "input"))
    )
    (net (code "254") (name "Net-(NOT_GATE2_B-I)") (class "Default")
      (node (ref "INSTRUCTION_MEMORY_2") (pin "16") (pinfunction "16_16") (pintype "passive"))
      (node (ref "NOT_GATE2_") (pin "3") (pinfunction "I_3") (pintype "input"))
    )
    (net (code "255") (name "Net-(NOT_GATE2_E-I)") (class "Default")
      (node (ref "NOT_GATE2_") (pin "11") (pinfunction "I_11") (pintype "input"))
      (node (ref "SELECTOR_LOGIC_") (pin "9") (pinfunction "Y3_9") (pintype "output"))
    )
    (net (code "256") (name "Net-(NOT_GATE2_E-O)") (class "Default")
      (node (ref "NOT_GATE2_") (pin "10") (pinfunction "O_10") (pintype "output"))
      (node (ref "PROGRAM_COUNTER_LOWER") (pin "10") (pinfunction "10_10") (pintype "passive"))
    )
    (net (code "257") (name "Net-(NOT_GATE2_F-O)") (class "Default")
      (node (ref "NOT_GATE2_") (pin "12") (pinfunction "O_12") (pintype "output"))
      (node (ref "OUTPUT_BUFFER_RAM") (pin "1") (pinfunction "DIR_1") (pintype "input"))
      (node (ref "RAM") (pin "27") (pinfunction "27_27") (pintype "passive"))
    )
    (net (code "258") (name "Net-(NOT_GATE3_B-I)") (class "Default")
      (node (ref "INSTRUCTION_MEMORY_1") (pin "13") (pinfunction "13_13") (pintype "passive"))
      (node (ref "NOT_GATE3_") (pin "3") (pinfunction "I_3") (pintype "input"))
    )
    (net (code "259") (name "Net-(NOT_GATE3_B-O)") (class "Default")
      (node (ref "NOT_GATE3_") (pin "4") (pinfunction "O_4") (pintype "output"))
      (node (ref "OUTPUT_BUFFER_ALU") (pin "19") (pinfunction "G_19") (pintype "input"))
    )
    (net (code "260") (name "Net-(NOT_GATE4_B-O)") (class "Default")
      (node (ref "NOT_GATE4_") (pin "4") (pinfunction "O_4") (pintype "output"))
      (node (ref "RAM_ADDR_LOWER") (pin "10") (pinfunction "G2_10") (pintype "input"))
      (node (ref "RAM_ADDR_LOWER") (pin "9") (pinfunction "G1_9") (pintype "input"))
      (node (ref "RAM_ADDR_UPPER") (pin "10") (pinfunction "G2_10") (pintype "input"))
      (node (ref "RAM_ADDR_UPPER") (pin "9") (pinfunction "G1_9") (pintype "input"))
    )
    (net (code "261") (name "Net-(NOT_GATE4_C-O)") (class "Default")
      (node (ref "NOT_GATE4_") (pin "6") (pinfunction "O_6") (pintype "output"))
      (node (ref "PROGRAM_COUNTER_LOWER") (pin "9") (pinfunction "9_9") (pintype "passive"))
      (node (ref "PROGRAM_COUNTER_UPPER") (pin "9") (pinfunction "9_9") (pintype "passive"))
    )
    (net (code "262") (name "Net-(NOT_GATE4_D-O)") (class "Default")
      (node (ref "MICRO_COUNTER_LOWER") (pin "9") (pinfunction "9_9") (pintype "passive"))
      (node (ref "MICRO_COUNTER_UPPER") (pin "9") (pinfunction "9_9") (pintype "passive"))
      (node (ref "NOT_GATE4_") (pin "8") (pinfunction "O_8") (pintype "output"))
    )
    (net (code "263") (name "Net-(NOT_GATE4_E-I)") (class "Default")
      (node (ref "INSTRUCTION_MEMORY_1") (pin "17") (pinfunction "17_17") (pintype "passive"))
      (node (ref "NOT_GATE4_") (pin "11") (pinfunction "I_11") (pintype "input"))
    )
    (net (code "264") (name "Net-(NOT_GATE4_E-O)") (class "Default")
      (node (ref "NOT_GATE4_") (pin "10") (pinfunction "O_10") (pintype "output"))
      (node (ref "OUTPUT_BUFFER_RAM") (pin "19") (pinfunction "G_19") (pintype "input"))
    )
    (net (code "265") (name "Net-(NOT_GATE_A-I)") (class "Default")
      (node (ref "INSTRUCTION_MEMORY_2") (pin "11") (pinfunction "11_11") (pintype "passive"))
      (node (ref "NOT_GATE_") (pin "1") (pinfunction "I_1") (pintype "input"))
    )
    (net (code "266") (name "Net-(NOT_GATE_A-O)") (class "Default")
      (node (ref "NOT_GATE_") (pin "2") (pinfunction "O_2") (pintype "output"))
      (node (ref "OUTPUT_BUFFER_FLAGS") (pin "19") (pinfunction "G_19") (pintype "input"))
    )
    (net (code "267") (name "Net-(NOT_GATE_B-I)") (class "Default")
      (node (ref "INSTRUCTION_MEMORY_2") (pin "15") (pinfunction "15_15") (pintype "passive"))
      (node (ref "NOT_GATE_") (pin "3") (pinfunction "I_3") (pintype "input"))
    )
    (net (code "268") (name "Net-(NOT_GATE_B-O)") (class "Default")
      (node (ref "NOT_GATE_") (pin "4") (pinfunction "O_4") (pintype "output"))
      (node (ref "OUTPUT_BUFFER_LOGIC") (pin "19") (pinfunction "G_19") (pintype "input"))
    )
    (net (code "269") (name "Net-(NOT_GATE_E-I)") (class "Default")
      (node (ref "NOT_GATE_") (pin "11") (pinfunction "I_11") (pintype "input"))
      (node (ref "SELECTOR_LOGIC_") (pin "11") (pinfunction "Y1_11") (pintype "output"))
    )
    (net (code "270") (name "Net-(OR_GATE3_A-O)") (class "Default")
      (node (ref "LOGIC_LED_8") (pin "A") (pinfunction "A_A") (pintype "passive"))
      (node (ref "OR_GATE3_") (pin "3") (pinfunction "O_3") (pintype "output"))
      (node (ref "OUTPUT_BUFFER_LOGIC") (pin "9") (pinfunction "A8_9") (pintype "bidirectional"))
    )
    (net (code "271") (name "Net-(OR_GATE3_B-O)") (class "Default")
      (node (ref "LOGIC_LED_7") (pin "A") (pinfunction "A_A") (pintype "passive"))
      (node (ref "OR_GATE3_") (pin "6") (pinfunction "O_6") (pintype "output"))
      (node (ref "OUTPUT_BUFFER_LOGIC") (pin "8") (pinfunction "A7_8") (pintype "bidirectional"))
    )
    (net (code "272") (name "Net-(OR_GATE3_C-O)") (class "Default")
      (node (ref "LOGIC_LED_6") (pin "A") (pinfunction "A_A") (pintype "passive"))
      (node (ref "OR_GATE3_") (pin "8") (pinfunction "O_8") (pintype "output"))
      (node (ref "OUTPUT_BUFFER_LOGIC") (pin "7") (pinfunction "A6_7") (pintype "bidirectional"))
    )
    (net (code "273") (name "Net-(OR_GATE3_D-O)") (class "Default")
      (node (ref "LOGIC_LED_5") (pin "A") (pinfunction "A_A") (pintype "passive"))
      (node (ref "OR_GATE3_") (pin "11") (pinfunction "O_11") (pintype "output"))
      (node (ref "OUTPUT_BUFFER_LOGIC") (pin "6") (pinfunction "A5_6") (pintype "bidirectional"))
    )
    (net (code "274") (name "Net-(OR_GATE4_A-O)") (class "Default")
      (node (ref "LOGIC_LED_4") (pin "A") (pinfunction "A_A") (pintype "passive"))
      (node (ref "OR_GATE4_") (pin "3") (pinfunction "O_3") (pintype "output"))
      (node (ref "OUTPUT_BUFFER_LOGIC") (pin "5") (pinfunction "A4_5") (pintype "bidirectional"))
    )
    (net (code "275") (name "Net-(OR_GATE4_B-O)") (class "Default")
      (node (ref "LOGIC_LED_3") (pin "A") (pinfunction "A_A") (pintype "passive"))
      (node (ref "OR_GATE4_") (pin "6") (pinfunction "O_6") (pintype "output"))
      (node (ref "OUTPUT_BUFFER_LOGIC") (pin "4") (pinfunction "A3_4") (pintype "bidirectional"))
    )
    (net (code "276") (name "Net-(OR_GATE4_C-O)") (class "Default")
      (node (ref "LOGIC_LED_2") (pin "A") (pinfunction "A_A") (pintype "passive"))
      (node (ref "OR_GATE4_") (pin "8") (pinfunction "O_8") (pintype "output"))
      (node (ref "OUTPUT_BUFFER_LOGIC") (pin "3") (pinfunction "A2_3") (pintype "bidirectional"))
    )
    (net (code "277") (name "Net-(OR_GATE4_D-O)") (class "Default")
      (node (ref "LOGIC_LED_1") (pin "A") (pinfunction "A_A") (pintype "passive"))
      (node (ref "OR_GATE4_") (pin "11") (pinfunction "O_11") (pintype "output"))
      (node (ref "OUTPUT_BUFFER_LOGIC") (pin "2") (pinfunction "A1_2") (pintype "bidirectional"))
    )
    (net (code "278") (name "Net-(OUTPUT_BUFFER_CALC_REGA-G)") (class "Default")
      (node (ref "OUTPUT_BUFFER_CALC_REG") (pin "19") (pinfunction "G_19") (pintype "input"))
      (node (ref "SELECTOR_LOGIC2_") (pin "11") (pinfunction "Y1_11") (pintype "output"))
    )
    (net (code "279") (name "Net-(OUTPUT_BUFFER_MEMORYA-A1)") (class "Default")
      (node (ref "MEMORY") (pin "19") (pinfunction "19_19") (pintype "passive"))
      (node (ref "OUTPUT_BUFFER_MEMORY") (pin "2") (pinfunction "A1_2") (pintype "bidirectional"))
    )
    (net (code "280") (name "Net-(OUTPUT_BUFFER_MEMORYA-A2)") (class "Default")
      (node (ref "MEMORY") (pin "18") (pinfunction "18_18") (pintype "passive"))
      (node (ref "OUTPUT_BUFFER_MEMORY") (pin "3") (pinfunction "A2_3") (pintype "bidirectional"))
    )
    (net (code "281") (name "Net-(OUTPUT_BUFFER_MEMORYA-A3)") (class "Default")
      (node (ref "MEMORY") (pin "17") (pinfunction "17_17") (pintype "passive"))
      (node (ref "OUTPUT_BUFFER_MEMORY") (pin "4") (pinfunction "A3_4") (pintype "bidirectional"))
    )
    (net (code "282") (name "Net-(OUTPUT_BUFFER_MEMORYA-A4)") (class "Default")
      (node (ref "MEMORY") (pin "16") (pinfunction "16_16") (pintype "passive"))
      (node (ref "OUTPUT_BUFFER_MEMORY") (pin "5") (pinfunction "A4_5") (pintype "bidirectional"))
    )
    (net (code "283") (name "Net-(OUTPUT_BUFFER_MEMORYA-A5)") (class "Default")
      (node (ref "MEMORY") (pin "15") (pinfunction "15_15") (pintype "passive"))
      (node (ref "OUTPUT_BUFFER_MEMORY") (pin "6") (pinfunction "A5_6") (pintype "bidirectional"))
    )
    (net (code "284") (name "Net-(OUTPUT_BUFFER_MEMORYA-A6)") (class "Default")
      (node (ref "MEMORY") (pin "13") (pinfunction "13_13") (pintype "passive"))
      (node (ref "OUTPUT_BUFFER_MEMORY") (pin "7") (pinfunction "A6_7") (pintype "bidirectional"))
    )
    (net (code "285") (name "Net-(OUTPUT_BUFFER_MEMORYA-A7)") (class "Default")
      (node (ref "MEMORY") (pin "12") (pinfunction "12_12") (pintype "passive"))
      (node (ref "OUTPUT_BUFFER_MEMORY") (pin "8") (pinfunction "A7_8") (pintype "bidirectional"))
    )
    (net (code "286") (name "Net-(OUTPUT_BUFFER_MEMORYA-A8)") (class "Default")
      (node (ref "MEMORY") (pin "11") (pinfunction "11_11") (pintype "passive"))
      (node (ref "OUTPUT_BUFFER_MEMORY") (pin "9") (pinfunction "A8_9") (pintype "bidirectional"))
    )
    (net (code "287") (name "Net-(OUTPUT_BUFFER_PCA-A1)") (class "Default")
      (node (ref "OUTPUT_BUFFER_PC") (pin "2") (pinfunction "A1_2") (pintype "bidirectional"))
      (node (ref "PC_8") (pin "A") (pinfunction "A_A") (pintype "passive"))
      (node (ref "PROGRAM_COUNTER_UPPER") (pin "11") (pinfunction "11_11") (pintype "passive"))
    )
    (net (code "288") (name "Net-(OUTPUT_BUFFER_PCA-A2)") (class "Default")
      (node (ref "OUTPUT_BUFFER_PC") (pin "3") (pinfunction "A2_3") (pintype "bidirectional"))
      (node (ref "PC_7") (pin "A") (pinfunction "A_A") (pintype "passive"))
      (node (ref "PROGRAM_COUNTER_UPPER") (pin "12") (pinfunction "12_12") (pintype "passive"))
    )
    (net (code "289") (name "Net-(OUTPUT_BUFFER_PCA-A3)") (class "Default")
      (node (ref "OUTPUT_BUFFER_PC") (pin "4") (pinfunction "A3_4") (pintype "bidirectional"))
      (node (ref "PC_6") (pin "A") (pinfunction "A_A") (pintype "passive"))
      (node (ref "PROGRAM_COUNTER_UPPER") (pin "13") (pinfunction "13_13") (pintype "passive"))
    )
    (net (code "290") (name "Net-(OUTPUT_BUFFER_PCA-A4)") (class "Default")
      (node (ref "OUTPUT_BUFFER_PC") (pin "5") (pinfunction "A4_5") (pintype "bidirectional"))
      (node (ref "PC_5") (pin "A") (pinfunction "A_A") (pintype "passive"))
      (node (ref "PROGRAM_COUNTER_UPPER") (pin "14") (pinfunction "14_14") (pintype "passive"))
    )
    (net (code "291") (name "Net-(OUTPUT_BUFFER_PCA-A5)") (class "Default")
      (node (ref "OUTPUT_BUFFER_PC") (pin "6") (pinfunction "A5_6") (pintype "bidirectional"))
      (node (ref "PC_4") (pin "A") (pinfunction "A_A") (pintype "passive"))
      (node (ref "PROGRAM_COUNTER_LOWER") (pin "11") (pinfunction "11_11") (pintype "passive"))
    )
    (net (code "292") (name "Net-(OUTPUT_BUFFER_PCA-A6)") (class "Default")
      (node (ref "OUTPUT_BUFFER_PC") (pin "7") (pinfunction "A6_7") (pintype "bidirectional"))
      (node (ref "PC_3") (pin "A") (pinfunction "A_A") (pintype "passive"))
      (node (ref "PROGRAM_COUNTER_LOWER") (pin "12") (pinfunction "12_12") (pintype "passive"))
    )
    (net (code "293") (name "Net-(OUTPUT_BUFFER_PCA-A7)") (class "Default")
      (node (ref "OUTPUT_BUFFER_PC") (pin "8") (pinfunction "A7_8") (pintype "bidirectional"))
      (node (ref "PC_2") (pin "A") (pinfunction "A_A") (pintype "passive"))
      (node (ref "PROGRAM_COUNTER_LOWER") (pin "13") (pinfunction "13_13") (pintype "passive"))
    )
    (net (code "294") (name "Net-(OUTPUT_BUFFER_PCA-A8)") (class "Default")
      (node (ref "OUTPUT_BUFFER_PC") (pin "9") (pinfunction "A8_9") (pintype "bidirectional"))
      (node (ref "PC_1") (pin "A") (pinfunction "A_A") (pintype "passive"))
      (node (ref "PROGRAM_COUNTER_LOWER") (pin "14") (pinfunction "14_14") (pintype "passive"))
    )
    (net (code "295") (name "Net-(OUTPUT_BUFFER_PCA-G)") (class "Default")
      (node (ref "OUTPUT_BUFFER_PC") (pin "19") (pinfunction "G_19") (pintype "input"))
      (node (ref "SELECTOR_LOGIC_") (pin "10") (pinfunction "Y2_10") (pintype "output"))
    )
    (net (code "296") (name "Net-(OUTPUT_BUFFER_RAMA-A1)") (class "Default")
      (node (ref "OUTPUT_BUFFER_RAM") (pin "2") (pinfunction "A1_2") (pintype "bidirectional"))
      (node (ref "RAM") (pin "11") (pinfunction "11_11") (pintype "passive"))
      (node (ref "RAM_LED_1") (pin "A") (pinfunction "A_A") (pintype "passive"))
    )
    (net (code "297") (name "Net-(OUTPUT_BUFFER_RAMA-A2)") (class "Default")
      (node (ref "OUTPUT_BUFFER_RAM") (pin "3") (pinfunction "A2_3") (pintype "bidirectional"))
      (node (ref "RAM") (pin "12") (pinfunction "12_12") (pintype "passive"))
      (node (ref "RAM_LED_2") (pin "A") (pinfunction "A_A") (pintype "passive"))
    )
    (net (code "298") (name "Net-(OUTPUT_BUFFER_RAMA-A3)") (class "Default")
      (node (ref "OUTPUT_BUFFER_RAM") (pin "4") (pinfunction "A3_4") (pintype "bidirectional"))
      (node (ref "RAM") (pin "13") (pinfunction "13_13") (pintype "passive"))
      (node (ref "RAM_LED_3") (pin "A") (pinfunction "A_A") (pintype "passive"))
    )
    (net (code "299") (name "Net-(OUTPUT_BUFFER_RAMA-A4)") (class "Default")
      (node (ref "OUTPUT_BUFFER_RAM") (pin "5") (pinfunction "A4_5") (pintype "bidirectional"))
      (node (ref "RAM") (pin "15") (pinfunction "15_15") (pintype "passive"))
      (node (ref "RAM_LED_4") (pin "A") (pinfunction "A_A") (pintype "passive"))
    )
    (net (code "300") (name "Net-(OUTPUT_BUFFER_RAMA-A5)") (class "Default")
      (node (ref "OUTPUT_BUFFER_RAM") (pin "6") (pinfunction "A5_6") (pintype "bidirectional"))
      (node (ref "RAM") (pin "16") (pinfunction "16_16") (pintype "passive"))
      (node (ref "RAM_LED_5") (pin "A") (pinfunction "A_A") (pintype "passive"))
    )
    (net (code "301") (name "Net-(OUTPUT_BUFFER_RAMA-A6)") (class "Default")
      (node (ref "OUTPUT_BUFFER_RAM") (pin "7") (pinfunction "A6_7") (pintype "bidirectional"))
      (node (ref "RAM") (pin "17") (pinfunction "17_17") (pintype "passive"))
      (node (ref "RAM_LED_6") (pin "A") (pinfunction "A_A") (pintype "passive"))
    )
    (net (code "302") (name "Net-(OUTPUT_BUFFER_RAMA-A7)") (class "Default")
      (node (ref "OUTPUT_BUFFER_RAM") (pin "8") (pinfunction "A7_8") (pintype "bidirectional"))
      (node (ref "RAM") (pin "18") (pinfunction "18_18") (pintype "passive"))
      (node (ref "RAM_LED_7") (pin "A") (pinfunction "A_A") (pintype "passive"))
    )
    (net (code "303") (name "Net-(OUTPUT_BUFFER_RAMA-A8)") (class "Default")
      (node (ref "OUTPUT_BUFFER_RAM") (pin "9") (pinfunction "A8_9") (pintype "bidirectional"))
      (node (ref "RAM") (pin "19") (pinfunction "19_19") (pintype "passive"))
      (node (ref "RAM_LED_8") (pin "A") (pinfunction "A_A") (pintype "passive"))
    )
    (net (code "304") (name "Net-(OVERFLOW_FLAG-C)") (class "Default")
      (node (ref "OVERFLOW_FLAG") (pin "K") (pinfunction "C_K") (pintype "passive"))
      (node (ref "R13") (pin "2") (pinfunction "2_2") (pintype "passive"))
    )
    (net (code "305") (name "Net-(PARAM_LED_1-C)") (class "Default")
      (node (ref "PARAM_LED_1") (pin "K") (pinfunction "C_K") (pintype "passive"))
      (node (ref "R71") (pin "1") (pinfunction "1_1") (pintype "passive"))
    )
    (net (code "306") (name "Net-(PARAM_LED_2-C)") (class "Default")
      (node (ref "PARAM_LED_2") (pin "K") (pinfunction "C_K") (pintype "passive"))
      (node (ref "R70") (pin "1") (pinfunction "1_1") (pintype "passive"))
    )
    (net (code "307") (name "Net-(PARAM_LED_3-C)") (class "Default")
      (node (ref "PARAM_LED_3") (pin "K") (pinfunction "C_K") (pintype "passive"))
      (node (ref "R69") (pin "1") (pinfunction "1_1") (pintype "passive"))
    )
    (net (code "308") (name "Net-(PARAM_LED_4-C)") (class "Default")
      (node (ref "PARAM_LED_4") (pin "K") (pinfunction "C_K") (pintype "passive"))
      (node (ref "R76") (pin "1") (pinfunction "1_1") (pintype "passive"))
    )
    (net (code "309") (name "Net-(PARAM_LED_5-C)") (class "Default")
      (node (ref "PARAM_LED_5") (pin "K") (pinfunction "C_K") (pintype "passive"))
      (node (ref "R72") (pin "1") (pinfunction "1_1") (pintype "passive"))
    )
    (net (code "310") (name "Net-(PARAM_LED_6-C)") (class "Default")
      (node (ref "PARAM_LED_6") (pin "K") (pinfunction "C_K") (pintype "passive"))
      (node (ref "R73") (pin "1") (pinfunction "1_1") (pintype "passive"))
    )
    (net (code "311") (name "Net-(PARAM_LED_7-C)") (class "Default")
      (node (ref "PARAM_LED_7") (pin "K") (pinfunction "C_K") (pintype "passive"))
      (node (ref "R74") (pin "1") (pinfunction "1_1") (pintype "passive"))
    )
    (net (code "312") (name "Net-(PARAM_LED_8-C)") (class "Default")
      (node (ref "PARAM_LED_8") (pin "K") (pinfunction "C_K") (pintype "passive"))
      (node (ref "R75") (pin "1") (pinfunction "1_1") (pintype "passive"))
    )
    (net (code "313") (name "Net-(PC_1-C)") (class "Default")
      (node (ref "PC_1") (pin "K") (pinfunction "C_K") (pintype "passive"))
      (node (ref "R16") (pin "1") (pinfunction "1_1") (pintype "passive"))
    )
    (net (code "314") (name "Net-(PC_2-C)") (class "Default")
      (node (ref "PC_2") (pin "K") (pinfunction "C_K") (pintype "passive"))
      (node (ref "R17") (pin "1") (pinfunction "1_1") (pintype "passive"))
    )
    (net (code "315") (name "Net-(PC_3-C)") (class "Default")
      (node (ref "PC_3") (pin "K") (pinfunction "C_K") (pintype "passive"))
      (node (ref "R18") (pin "1") (pinfunction "1_1") (pintype "passive"))
    )
    (net (code "316") (name "Net-(PC_4-C)") (class "Default")
      (node (ref "PC_4") (pin "K") (pinfunction "C_K") (pintype "passive"))
      (node (ref "R19") (pin "1") (pinfunction "1_1") (pintype "passive"))
    )
    (net (code "317") (name "Net-(PC_5-C)") (class "Default")
      (node (ref "PC_5") (pin "K") (pinfunction "C_K") (pintype "passive"))
      (node (ref "R20") (pin "1") (pinfunction "1_1") (pintype "passive"))
    )
    (net (code "318") (name "Net-(PC_6-C)") (class "Default")
      (node (ref "PC_6") (pin "K") (pinfunction "C_K") (pintype "passive"))
      (node (ref "R21") (pin "1") (pinfunction "1_1") (pintype "passive"))
    )
    (net (code "319") (name "Net-(PC_7-C)") (class "Default")
      (node (ref "PC_7") (pin "K") (pinfunction "C_K") (pintype "passive"))
      (node (ref "R22") (pin "1") (pinfunction "1_1") (pintype "passive"))
    )
    (net (code "320") (name "Net-(PC_8-C)") (class "Default")
      (node (ref "PC_8") (pin "K") (pinfunction "C_K") (pintype "passive"))
      (node (ref "R23") (pin "1") (pinfunction "1_1") (pintype "passive"))
    )
    (net (code "321") (name "Net-(POSITIVE_FLAG-C)") (class "Default")
      (node (ref "POSITIVE_FLAG") (pin "K") (pinfunction "C_K") (pintype "passive"))
      (node (ref "R12") (pin "2") (pinfunction "2_2") (pintype "passive"))
    )
    (net (code "322") (name "Net-(PROGRAM_COUNTER_LOWER-Pad15)") (class "Default")
      (node (ref "PROGRAM_COUNTER_LOWER") (pin "15") (pinfunction "15_15") (pintype "passive"))
      (node (ref "PROGRAM_COUNTER_UPPER") (pin "10") (pinfunction "10_10") (pintype "passive"))
    )
    (net (code "323") (name "Net-(RAM_ADDR_LOWERA-Q1)") (class "Default")
      (node (ref "RAM") (pin "10") (pinfunction "10_10") (pintype "passive"))
      (node (ref "RAM_ADDR_LOWER") (pin "3") (pinfunction "Q1_3") (pintype "tri_state"))
    )
    (net (code "324") (name "Net-(RAM_ADDR_LOWERA-Q2)") (class "Default")
      (node (ref "RAM") (pin "9") (pinfunction "9_9") (pintype "passive"))
      (node (ref "RAM_ADDR_LOWER") (pin "4") (pinfunction "Q2_4") (pintype "tri_state"))
    )
    (net (code "325") (name "Net-(RAM_ADDR_LOWERA-Q3)") (class "Default")
      (node (ref "RAM") (pin "8") (pinfunction "8_8") (pintype "passive"))
      (node (ref "RAM_ADDR_LOWER") (pin "5") (pinfunction "Q3_5") (pintype "tri_state"))
    )
    (net (code "326") (name "Net-(RAM_ADDR_LOWERA-Q4)") (class "Default")
      (node (ref "RAM") (pin "7") (pinfunction "7_7") (pintype "passive"))
      (node (ref "RAM_ADDR_LOWER") (pin "6") (pinfunction "Q4_6") (pintype "tri_state"))
    )
    (net (code "327") (name "Net-(RAM_ADDR_UPPERA-Q1)") (class "Default")
      (node (ref "RAM") (pin "6") (pinfunction "6_6") (pintype "passive"))
      (node (ref "RAM_ADDR_UPPER") (pin "3") (pinfunction "Q1_3") (pintype "tri_state"))
    )
    (net (code "328") (name "Net-(RAM_ADDR_UPPERA-Q2)") (class "Default")
      (node (ref "RAM") (pin "5") (pinfunction "5_5") (pintype "passive"))
      (node (ref "RAM_ADDR_UPPER") (pin "4") (pinfunction "Q2_4") (pintype "tri_state"))
    )
    (net (code "329") (name "Net-(RAM_ADDR_UPPERA-Q3)") (class "Default")
      (node (ref "RAM") (pin "4") (pinfunction "4_4") (pintype "passive"))
      (node (ref "RAM_ADDR_UPPER") (pin "5") (pinfunction "Q3_5") (pintype "tri_state"))
    )
    (net (code "330") (name "Net-(RAM_ADDR_UPPERA-Q4)") (class "Default")
      (node (ref "RAM") (pin "3") (pinfunction "3_3") (pintype "passive"))
      (node (ref "RAM_ADDR_UPPER") (pin "6") (pinfunction "Q4_6") (pintype "tri_state"))
    )
    (net (code "331") (name "Net-(RAM_LED_1-C)") (class "Default")
      (node (ref "R32") (pin "1") (pinfunction "1_1") (pintype "passive"))
      (node (ref "RAM_LED_1") (pin "K") (pinfunction "C_K") (pintype "passive"))
    )
    (net (code "332") (name "Net-(RAM_LED_2-C)") (class "Default")
      (node (ref "R33") (pin "1") (pinfunction "1_1") (pintype "passive"))
      (node (ref "RAM_LED_2") (pin "K") (pinfunction "C_K") (pintype "passive"))
    )
    (net (code "333") (name "Net-(RAM_LED_3-C)") (class "Default")
      (node (ref "R34") (pin "1") (pinfunction "1_1") (pintype "passive"))
      (node (ref "RAM_LED_3") (pin "K") (pinfunction "C_K") (pintype "passive"))
    )
    (net (code "334") (name "Net-(RAM_LED_4-C)") (class "Default")
      (node (ref "R35") (pin "1") (pinfunction "1_1") (pintype "passive"))
      (node (ref "RAM_LED_4") (pin "K") (pinfunction "C_K") (pintype "passive"))
    )
    (net (code "335") (name "Net-(RAM_LED_5-C)") (class "Default")
      (node (ref "R36") (pin "1") (pinfunction "1_1") (pintype "passive"))
      (node (ref "RAM_LED_5") (pin "K") (pinfunction "C_K") (pintype "passive"))
    )
    (net (code "336") (name "Net-(RAM_LED_6-C)") (class "Default")
      (node (ref "R37") (pin "1") (pinfunction "1_1") (pintype "passive"))
      (node (ref "RAM_LED_6") (pin "K") (pinfunction "C_K") (pintype "passive"))
    )
    (net (code "337") (name "Net-(RAM_LED_7-C)") (class "Default")
      (node (ref "R38") (pin "1") (pinfunction "1_1") (pintype "passive"))
      (node (ref "RAM_LED_7") (pin "K") (pinfunction "C_K") (pintype "passive"))
    )
    (net (code "338") (name "Net-(RAM_LED_8-C)") (class "Default")
      (node (ref "R39") (pin "1") (pinfunction "1_1") (pintype "passive"))
      (node (ref "RAM_LED_8") (pin "K") (pinfunction "C_K") (pintype "passive"))
    )
    (net (code "339") (name "Net-(SELECTOR_LOGIC2_A-A)") (class "Default")
      (node (ref "INSTRUCTION_MEMORY_1") (pin "18") (pinfunction "18_18") (pintype "passive"))
      (node (ref "SELECTOR_LOGIC2_") (pin "2") (pinfunction "A_2") (pintype "input"))
    )
    (net (code "340") (name "Net-(SELECTOR_LOGIC2_A-B)") (class "Default")
      (node (ref "INSTRUCTION_MEMORY_1") (pin "19") (pinfunction "19_19") (pintype "passive"))
      (node (ref "SELECTOR_LOGIC2_") (pin "3") (pinfunction "B_3") (pintype "input"))
    )
    (net (code "341") (name "Net-(SELECTOR_LOGIC2_B-A)") (class "Default")
      (node (ref "INSTRUCTION_MEMORY_1") (pin "12") (pinfunction "12_12") (pintype "passive"))
      (node (ref "SELECTOR_LOGIC2_") (pin "14") (pinfunction "A_14") (pintype "input"))
    )
    (net (code "342") (name "Net-(SELECTOR_LOGIC2_B-B)") (class "Default")
      (node (ref "INSTRUCTION_MEMORY_1") (pin "11") (pinfunction "11_11") (pintype "passive"))
      (node (ref "SELECTOR_LOGIC2_") (pin "13") (pinfunction "B_13") (pintype "input"))
    )
    (net (code "343") (name "Net-(SELECTOR_LOGIC_A-B)") (class "Default")
      (node (ref "INSTRUCTION_MEMORY_2") (pin "13") (pinfunction "13_13") (pintype "passive"))
      (node (ref "SELECTOR_LOGIC_") (pin "3") (pinfunction "B_3") (pintype "input"))
    )
    (net (code "344") (name "Net-(STEPPER_CLOCK-DIS)") (class "Default")
      (node (ref "C2") (pin "+") (pinfunction "+_+") (pintype "passive"))
      (node (ref "R3") (pin "1") (pinfunction "1_1") (pintype "passive"))
      (node (ref "STEPPER_CLOCK") (pin "6") (pinfunction "THR_6") (pintype "input"))
      (node (ref "STEPPER_CLOCK") (pin "7") (pinfunction "DIS_7") (pintype "input"))
    )
    (net (code "345") (name "Net-(USTEP_1-C)") (class "Default")
      (node (ref "R40") (pin "2") (pinfunction "2_2") (pintype "passive"))
      (node (ref "USTEP_1") (pin "K") (pinfunction "C_K") (pintype "passive"))
    )
    (net (code "346") (name "Net-(USTEP_2-C)") (class "Default")
      (node (ref "R41") (pin "2") (pinfunction "2_2") (pintype "passive"))
      (node (ref "USTEP_2") (pin "K") (pinfunction "C_K") (pintype "passive"))
    )
    (net (code "347") (name "Net-(USTEP_3-C)") (class "Default")
      (node (ref "R42") (pin "2") (pinfunction "2_2") (pintype "passive"))
      (node (ref "USTEP_3") (pin "K") (pinfunction "C_K") (pintype "passive"))
    )
    (net (code "348") (name "Net-(USTEP_4-C)") (class "Default")
      (node (ref "R43") (pin "2") (pinfunction "2_2") (pintype "passive"))
      (node (ref "USTEP_4") (pin "K") (pinfunction "C_K") (pintype "passive"))
    )
    (net (code "349") (name "Net-(USTEP_5-C)") (class "Default")
      (node (ref "R44") (pin "2") (pinfunction "2_2") (pintype "passive"))
      (node (ref "USTEP_5") (pin "K") (pinfunction "C_K") (pintype "passive"))
    )
    (net (code "350") (name "Net-(ZERO_FLAG-C)") (class "Default")
      (node (ref "R14") (pin "2") (pinfunction "2_2") (pintype "passive"))
      (node (ref "ZERO_FLAG") (pin "K") (pinfunction "C_K") (pintype "passive"))
    )
    (net (code "351") (name "VCC") (class "Default")
      (node (ref "4_INP_OR_GATE") (pin "14") (pinfunction "VDD_14") (pintype "power_in"))
      (node (ref "AUTO_CLOCK") (pin "4") (pinfunction "R_4") (pintype "input"))
      (node (ref "AUTO_CLOCK") (pin "8") (pinfunction "V+_8") (pintype "power_in"))
      (node (ref "C3") (pin "+") (pinfunction "+_+") (pintype "passive"))
      (node (ref "CLK_MODE") (pin "2") (pinfunction "2_2") (pintype "passive"))
      (node (ref "EXTENSION") (pin "10") (pinfunction "1_10") (pintype "passive"))
      (node (ref "INSTRUCTIONS_EXTENSION") (pin "14") (pinfunction "1_14") (pintype "passive"))
      (node (ref "INSTRUCTION_MEMORY_0") (pin "27") (pinfunction "27_27") (pintype "passive"))
      (node (ref "INSTRUCTION_MEMORY_0") (pin "28") (pinfunction "28_28") (pintype "passive"))
      (node (ref "INSTRUCTION_MEMORY_1") (pin "27") (pinfunction "27_27") (pintype "passive"))
      (node (ref "INSTRUCTION_MEMORY_1") (pin "28") (pinfunction "28_28") (pintype "passive"))
      (node (ref "INSTRUCTION_MEMORY_2") (pin "27") (pinfunction "27_27") (pintype "passive"))
      (node (ref "INSTRUCTION_MEMORY_2") (pin "28") (pinfunction "28_28") (pintype "passive"))
      (node (ref "MEMORY") (pin "27") (pinfunction "27_27") (pintype "passive"))
      (node (ref "MEMORY") (pin "28") (pinfunction "28_28") (pintype "passive"))
      (node (ref "MICRO_COUNTER_LOWER") (pin "10") (pinfunction "10_10") (pintype "passive"))
      (node (ref "MICRO_COUNTER_LOWER") (pin "16") (pinfunction "16_16") (pintype "passive"))
      (node (ref "MICRO_COUNTER_LOWER") (pin "7") (pinfunction "7_7") (pintype "passive"))
      (node (ref "MICRO_COUNTER_UPPER") (pin "16") (pinfunction "16_16") (pintype "passive"))
      (node (ref "MICRO_COUNTER_UPPER") (pin "7") (pinfunction "7_7") (pintype "passive"))
      (node (ref "OUTPUT_BUFFER_CALC_REG") (pin "1") (pinfunction "DIR_1") (pintype "input"))
      (node (ref "OUTPUT_BUFFER_INSTRUCTION") (pin "1") (pinfunction "DIR_1") (pintype "input"))
      (node (ref "OUTPUT_BUFFER_LOGIC") (pin "1") (pinfunction "DIR_1") (pintype "input"))
      (node (ref "OUTPUT_BUFFER_MEMORY") (pin "1") (pinfunction "DIR_1") (pintype "input"))
      (node (ref "OUTPUT_BUFFER_PARAM_REG") (pin "1") (pinfunction "DIR_1") (pintype "input"))
      (node (ref "OUTPUT_BUFFER_PC") (pin "1") (pinfunction "DIR_1") (pintype "input"))
      (node (ref "OUTPUT_BUFFER_REG_A") (pin "1") (pinfunction "DIR_1") (pintype "input"))
      (node (ref "PROGRAM_COUNTER_LOWER") (pin "16") (pinfunction "16_16") (pintype "passive"))
      (node (ref "PROGRAM_COUNTER_LOWER") (pin "7") (pinfunction "7_7") (pintype "passive"))
      (node (ref "PROGRAM_COUNTER_UPPER") (pin "16") (pinfunction "16_16") (pintype "passive"))
      (node (ref "PROGRAM_COUNTER_UPPER") (pin "7") (pinfunction "7_7") (pintype "passive"))
      (node (ref "R1") (pin "1") (pinfunction "1_1") (pintype "passive"))
      (node (ref "R2") (pin "1") (pinfunction "1_1") (pintype "passive"))
      (node (ref "R3") (pin "2") (pinfunction "2_2") (pintype "passive"))
      (node (ref "R80") (pin "2") (pinfunction "2_2") (pintype "passive"))
      (node (ref "RAM") (pin "28") (pinfunction "28_28") (pintype "passive"))
      (node (ref "RESET_REGS") (pin "1") (pinfunction "S_1") (pintype "passive"))
      (node (ref "STEPPER_CLOCK") (pin "8") (pinfunction "V+_8") (pintype "power_in"))
      (node (ref "X1") (pin "2") (pinfunction "1_2") (pintype "passive"))
      (node (ref "ZERO_POS_FLAG_IDENTIFIER") (pin "14") (pinfunction "+UB_14") (pintype "power_in"))
    )
    (net (code "352") (name "unconnected-(AUTO_CLOCK-CV-Pad5)") (class "Default")
      (node (ref "AUTO_CLOCK") (pin "5") (pinfunction "CV_5") (pintype "input"))
    )
    (net (code "353") (name "unconnected-(BRANCH_SELECTORB-Y0-Pad12)") (class "Default")
      (node (ref "BRANCH_SELECTOR") (pin "12") (pinfunction "Y0_12") (pintype "output"))
    )
    (net (code "354") (name "unconnected-(CLK_TRIGGER-P1-Pad4)") (class "Default")
      (node (ref "CLK_TRIGGER") (pin "4") (pinfunction "P1_4") (pintype "passive"))
    )
    (net (code "355") (name "unconnected-(CLK_TRIGGER-S-Pad1)") (class "Default")
      (node (ref "CLK_TRIGGER") (pin "1") (pinfunction "S_1") (pintype "passive"))
    )
    (net (code "356") (name "unconnected-(FREQUENCY-PadA)") (class "Default")
      (node (ref "FREQUENCY") (pin "A") (pinfunction "A_A") (pintype "passive"))
    )
    (net (code "357") (name "unconnected-(INSTRUCTION_MEMORY_0-Pad1)") (class "Default")
      (node (ref "INSTRUCTION_MEMORY_0") (pin "1") (pinfunction "1_1") (pintype "passive"))
    )
    (net (code "358") (name "unconnected-(INSTRUCTION_MEMORY_0-Pad26)") (class "Default")
      (node (ref "INSTRUCTION_MEMORY_0") (pin "26") (pinfunction "26_26") (pintype "passive"))
    )
    (net (code "359") (name "unconnected-(INSTRUCTION_MEMORY_1-Pad1)") (class "Default")
      (node (ref "INSTRUCTION_MEMORY_1") (pin "1") (pinfunction "1_1") (pintype "passive"))
    )
    (net (code "360") (name "unconnected-(INSTRUCTION_MEMORY_1-Pad26)") (class "Default")
      (node (ref "INSTRUCTION_MEMORY_1") (pin "26") (pinfunction "26_26") (pintype "passive"))
    )
    (net (code "361") (name "unconnected-(INSTRUCTION_MEMORY_2-Pad1)") (class "Default")
      (node (ref "INSTRUCTION_MEMORY_2") (pin "1") (pinfunction "1_1") (pintype "passive"))
    )
    (net (code "362") (name "unconnected-(INSTRUCTION_MEMORY_2-Pad26)") (class "Default")
      (node (ref "INSTRUCTION_MEMORY_2") (pin "26") (pinfunction "26_26") (pintype "passive"))
    )
    (net (code "363") (name "unconnected-(MEMORY-Pad1)") (class "Default")
      (node (ref "MEMORY") (pin "1") (pinfunction "1_1") (pintype "passive"))
    )
    (net (code "364") (name "unconnected-(MEMORY-Pad26)") (class "Default")
      (node (ref "MEMORY") (pin "26") (pinfunction "26_26") (pintype "passive"))
    )
    (net (code "365") (name "unconnected-(MICRO_COUNTER_UPPER-Pad4)") (class "Default")
      (node (ref "MICRO_COUNTER_UPPER") (pin "4") (pinfunction "4_4") (pintype "passive"))
    )
    (net (code "366") (name "unconnected-(MICRO_COUNTER_UPPER-Pad5)") (class "Default")
      (node (ref "MICRO_COUNTER_UPPER") (pin "5") (pinfunction "5_5") (pintype "passive"))
    )
    (net (code "367") (name "unconnected-(MICRO_COUNTER_UPPER-Pad6)") (class "Default")
      (node (ref "MICRO_COUNTER_UPPER") (pin "6") (pinfunction "6_6") (pintype "passive"))
    )
    (net (code "368") (name "unconnected-(MICRO_COUNTER_UPPER-Pad11)") (class "Default")
      (node (ref "MICRO_COUNTER_UPPER") (pin "11") (pinfunction "11_11") (pintype "passive"))
    )
    (net (code "369") (name "unconnected-(MICRO_COUNTER_UPPER-Pad12)") (class "Default")
      (node (ref "MICRO_COUNTER_UPPER") (pin "12") (pinfunction "12_12") (pintype "passive"))
    )
    (net (code "370") (name "unconnected-(MICRO_COUNTER_UPPER-Pad13)") (class "Default")
      (node (ref "MICRO_COUNTER_UPPER") (pin "13") (pinfunction "13_13") (pintype "passive"))
    )
    (net (code "371") (name "unconnected-(MICRO_COUNTER_UPPER-Pad15)") (class "Default")
      (node (ref "MICRO_COUNTER_UPPER") (pin "15") (pinfunction "15_15") (pintype "passive"))
    )
    (net (code "372") (name "unconnected-(PROGRAM_COUNTER_UPPER-Pad15)") (class "Default")
      (node (ref "PROGRAM_COUNTER_UPPER") (pin "15") (pinfunction "15_15") (pintype "passive"))
    )
    (net (code "373") (name "unconnected-(RESET_PC-P-Pad3)") (class "Default")
      (node (ref "RESET_PC") (pin "3") (pinfunction "P_3") (pintype "passive"))
    )
    (net (code "374") (name "unconnected-(RESET_PC-S1-Pad2)") (class "Default")
      (node (ref "RESET_PC") (pin "2") (pinfunction "S1_2") (pintype "passive"))
    )
    (net (code "375") (name "unconnected-(RESET_REGS-P-Pad3)") (class "Default")
      (node (ref "RESET_REGS") (pin "3") (pinfunction "P_3") (pintype "passive"))
    )
    (net (code "376") (name "unconnected-(RESET_REGS-S1-Pad2)") (class "Default")
      (node (ref "RESET_REGS") (pin "2") (pinfunction "S1_2") (pintype "passive"))
    )
    (net (code "377") (name "unconnected-(SELECTOR_LOGIC2_A-Y0-Pad4)") (class "Default")
      (node (ref "SELECTOR_LOGIC2_") (pin "4") (pinfunction "Y0_4") (pintype "output"))
    )
    (net (code "378") (name "unconnected-(SELECTOR_LOGIC2_B-Y0-Pad12)") (class "Default")
      (node (ref "SELECTOR_LOGIC2_") (pin "12") (pinfunction "Y0_12") (pintype "output"))
    )
    (net (code "379") (name "unconnected-(SELECTOR_LOGIC_B-Y0-Pad12)") (class "Default")
      (node (ref "SELECTOR_LOGIC_") (pin "12") (pinfunction "Y0_12") (pintype "output"))
    )
    (net (code "380") (name "unconnected-(STEPPER_CLOCK-CV-Pad5)") (class "Default")
      (node (ref "STEPPER_CLOCK") (pin "5") (pinfunction "CV_5") (pintype "input"))
    )
    (net (code "381") (name "unconnected-(STEPPER_CLOCK-R-Pad4)") (class "Default")
      (node (ref "STEPPER_CLOCK") (pin "4") (pinfunction "R_4") (pintype "input"))
    )
    (net (code "382") (name "unconnected-(X1C-1-Pad3)") (class "Default")
      (node (ref "X1") (pin "3") (pinfunction "1_3") (pintype "passive"))
    )
  )
)
